# pandashield12-lga.net
KiCad netlist of a schematic drawn in EAGLE
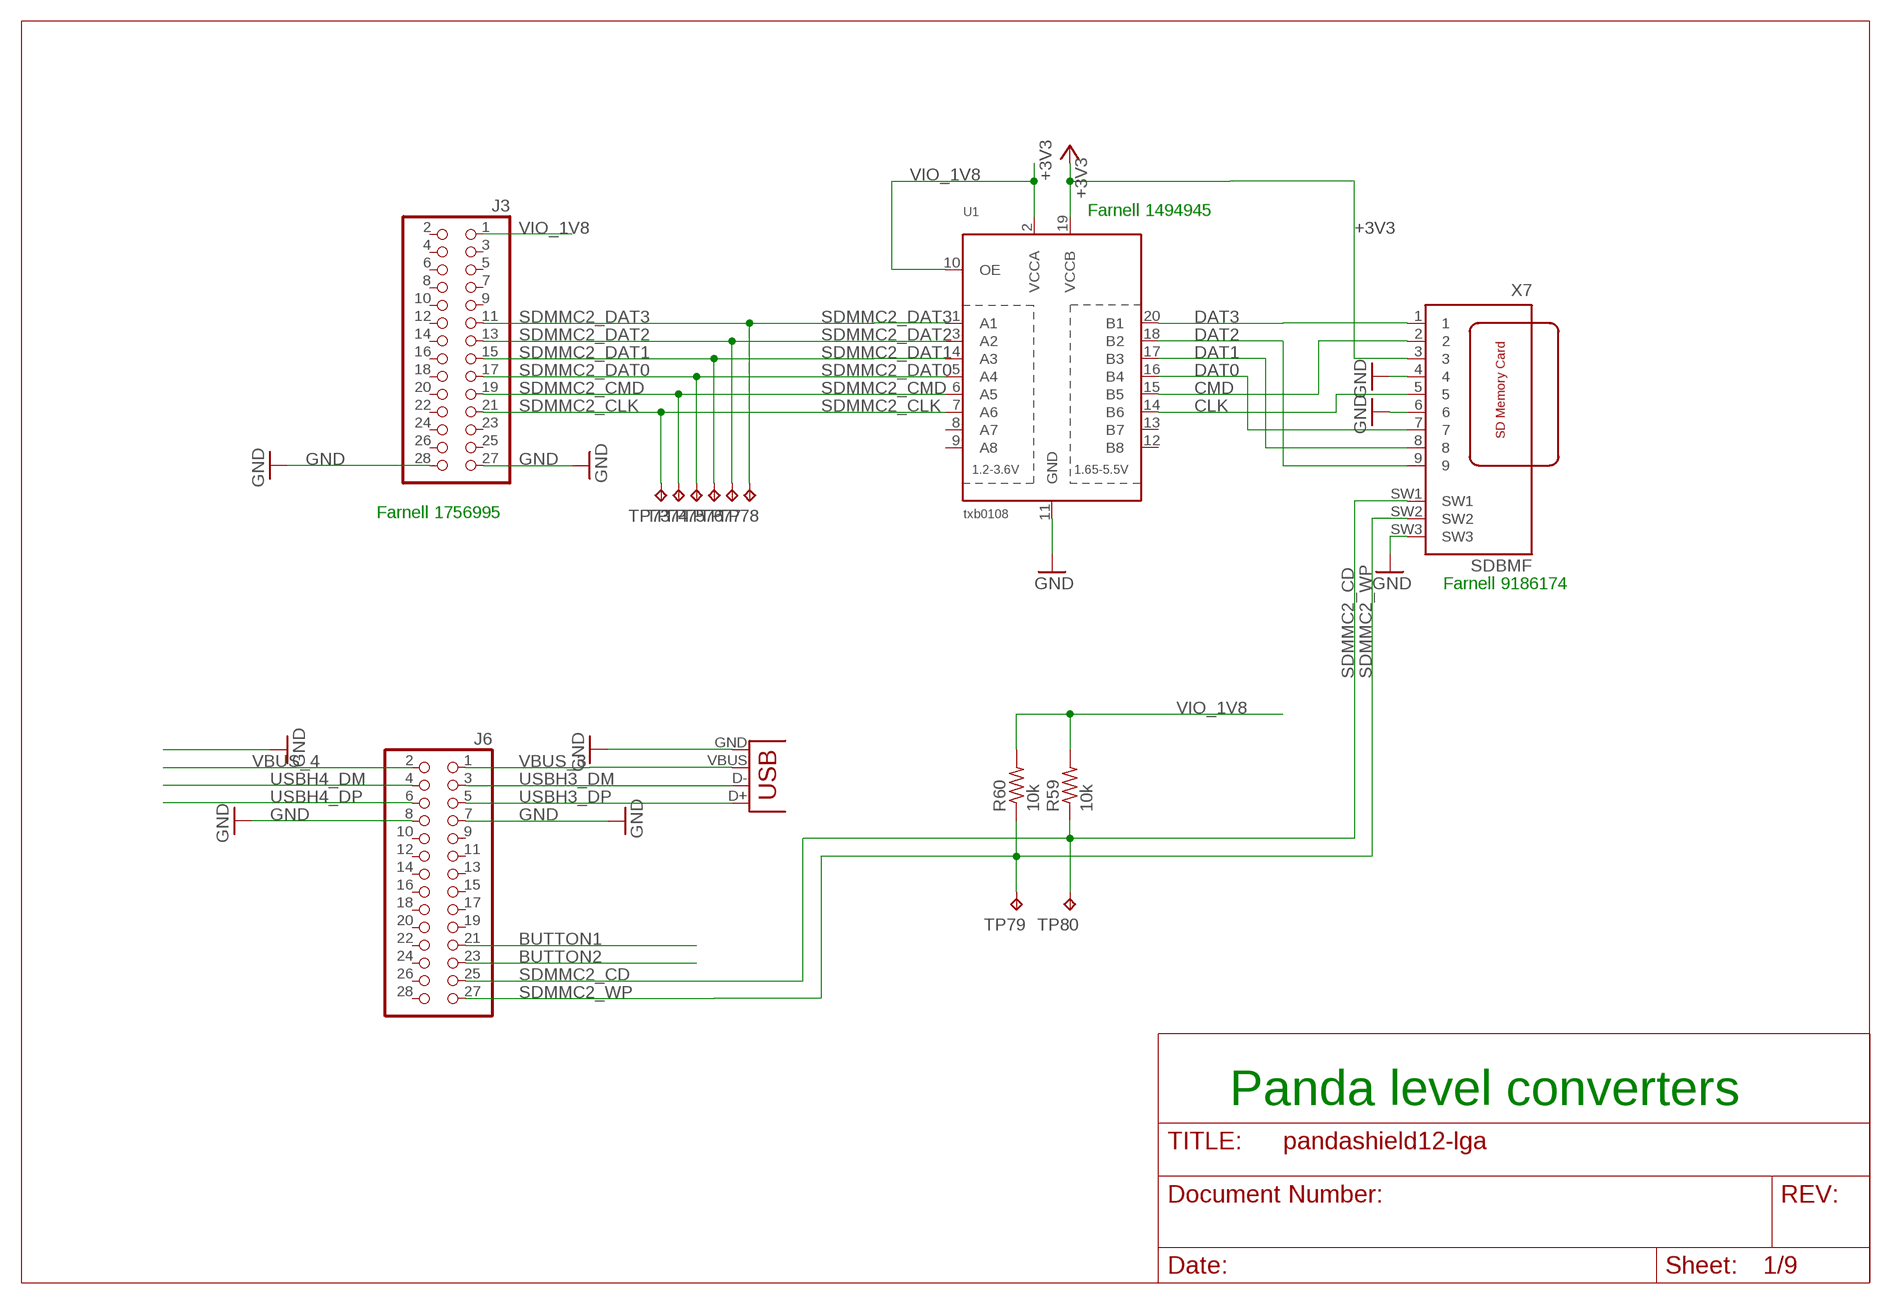
[diagram p0: schematic, sheet 1]
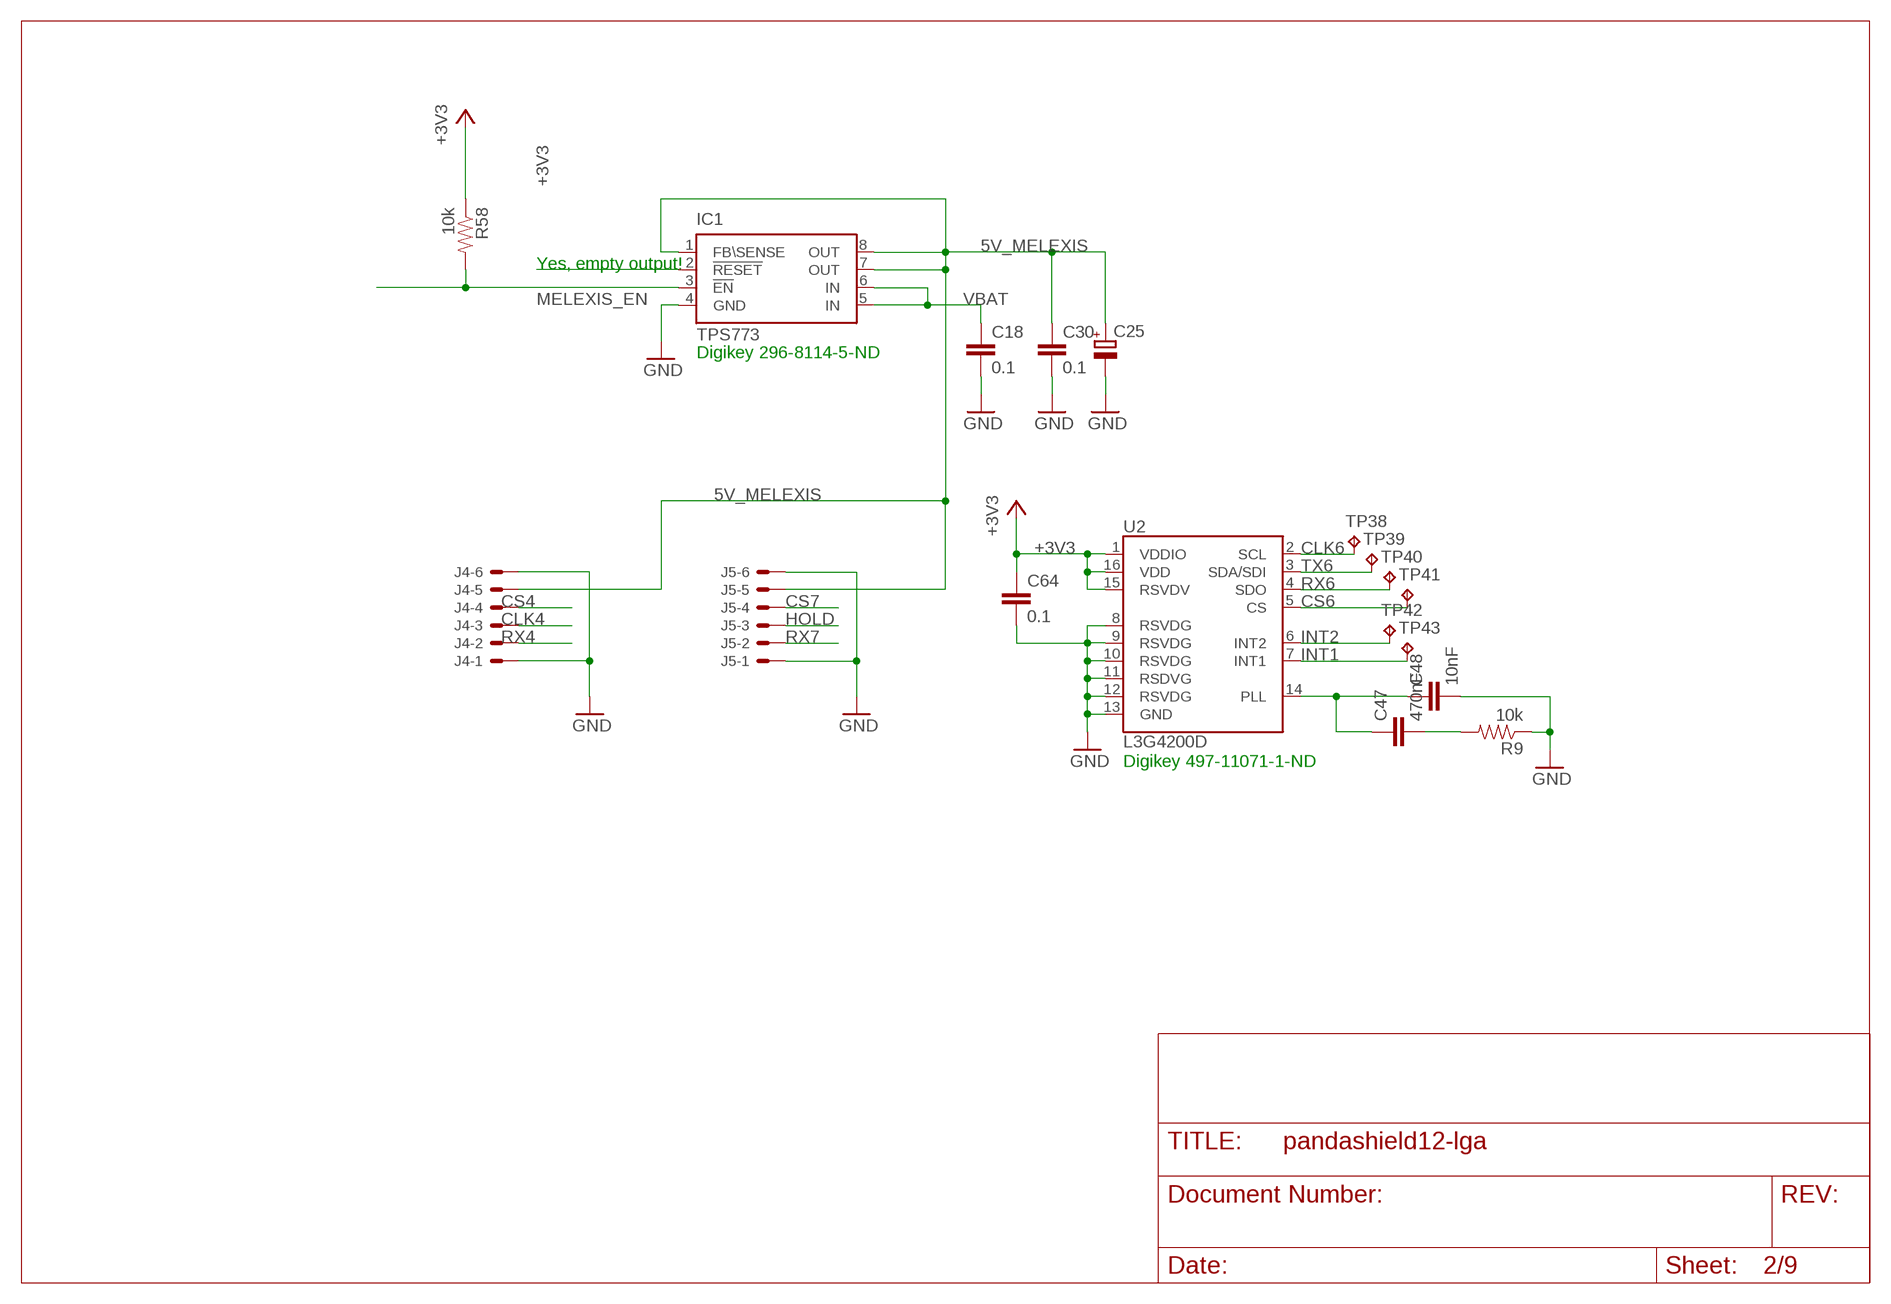
[diagram p1: schematic, sheet 2]
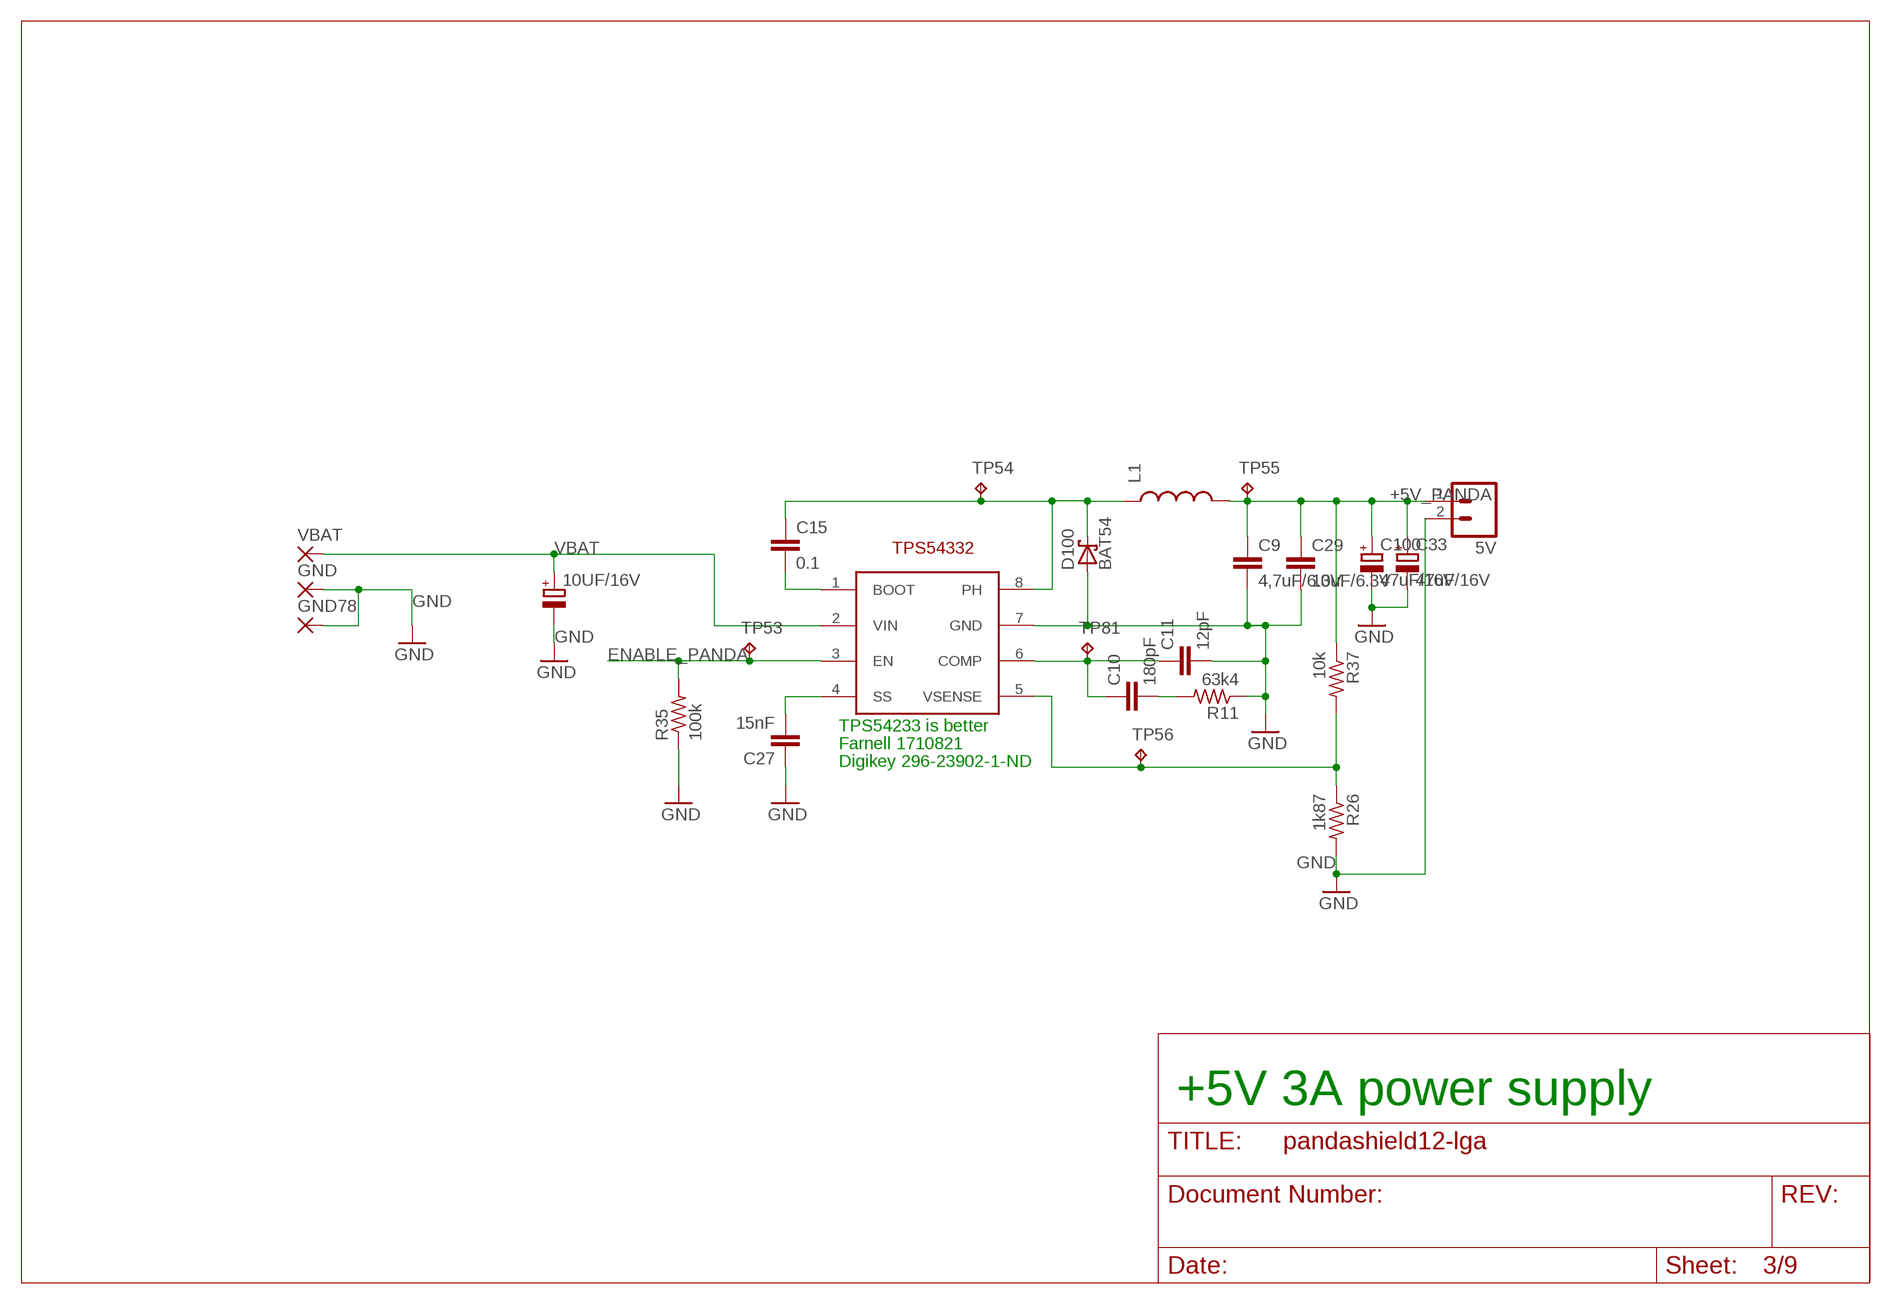
[diagram p2: schematic, sheet 3]
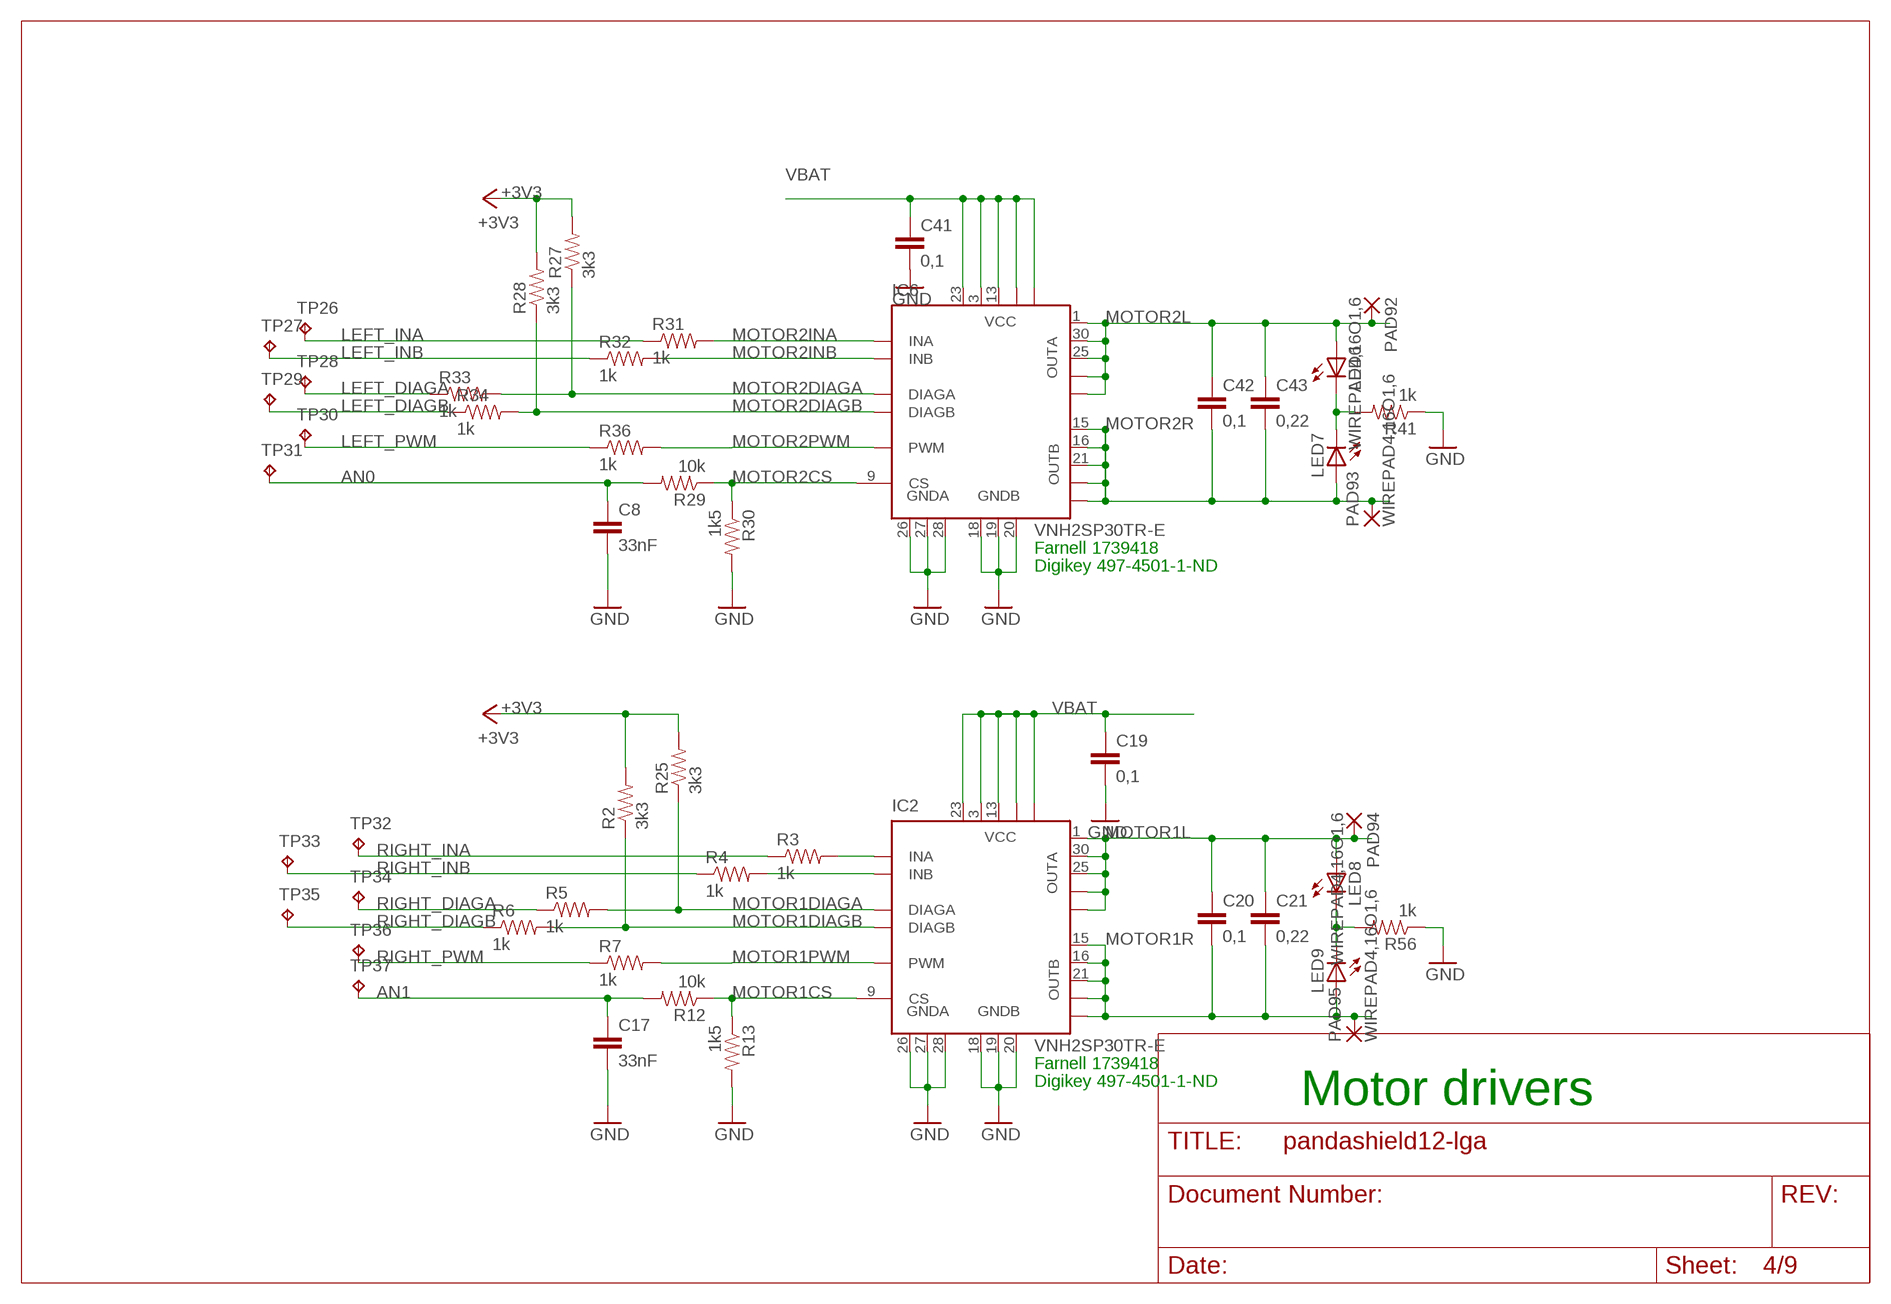
[diagram p3: schematic, sheet 4]
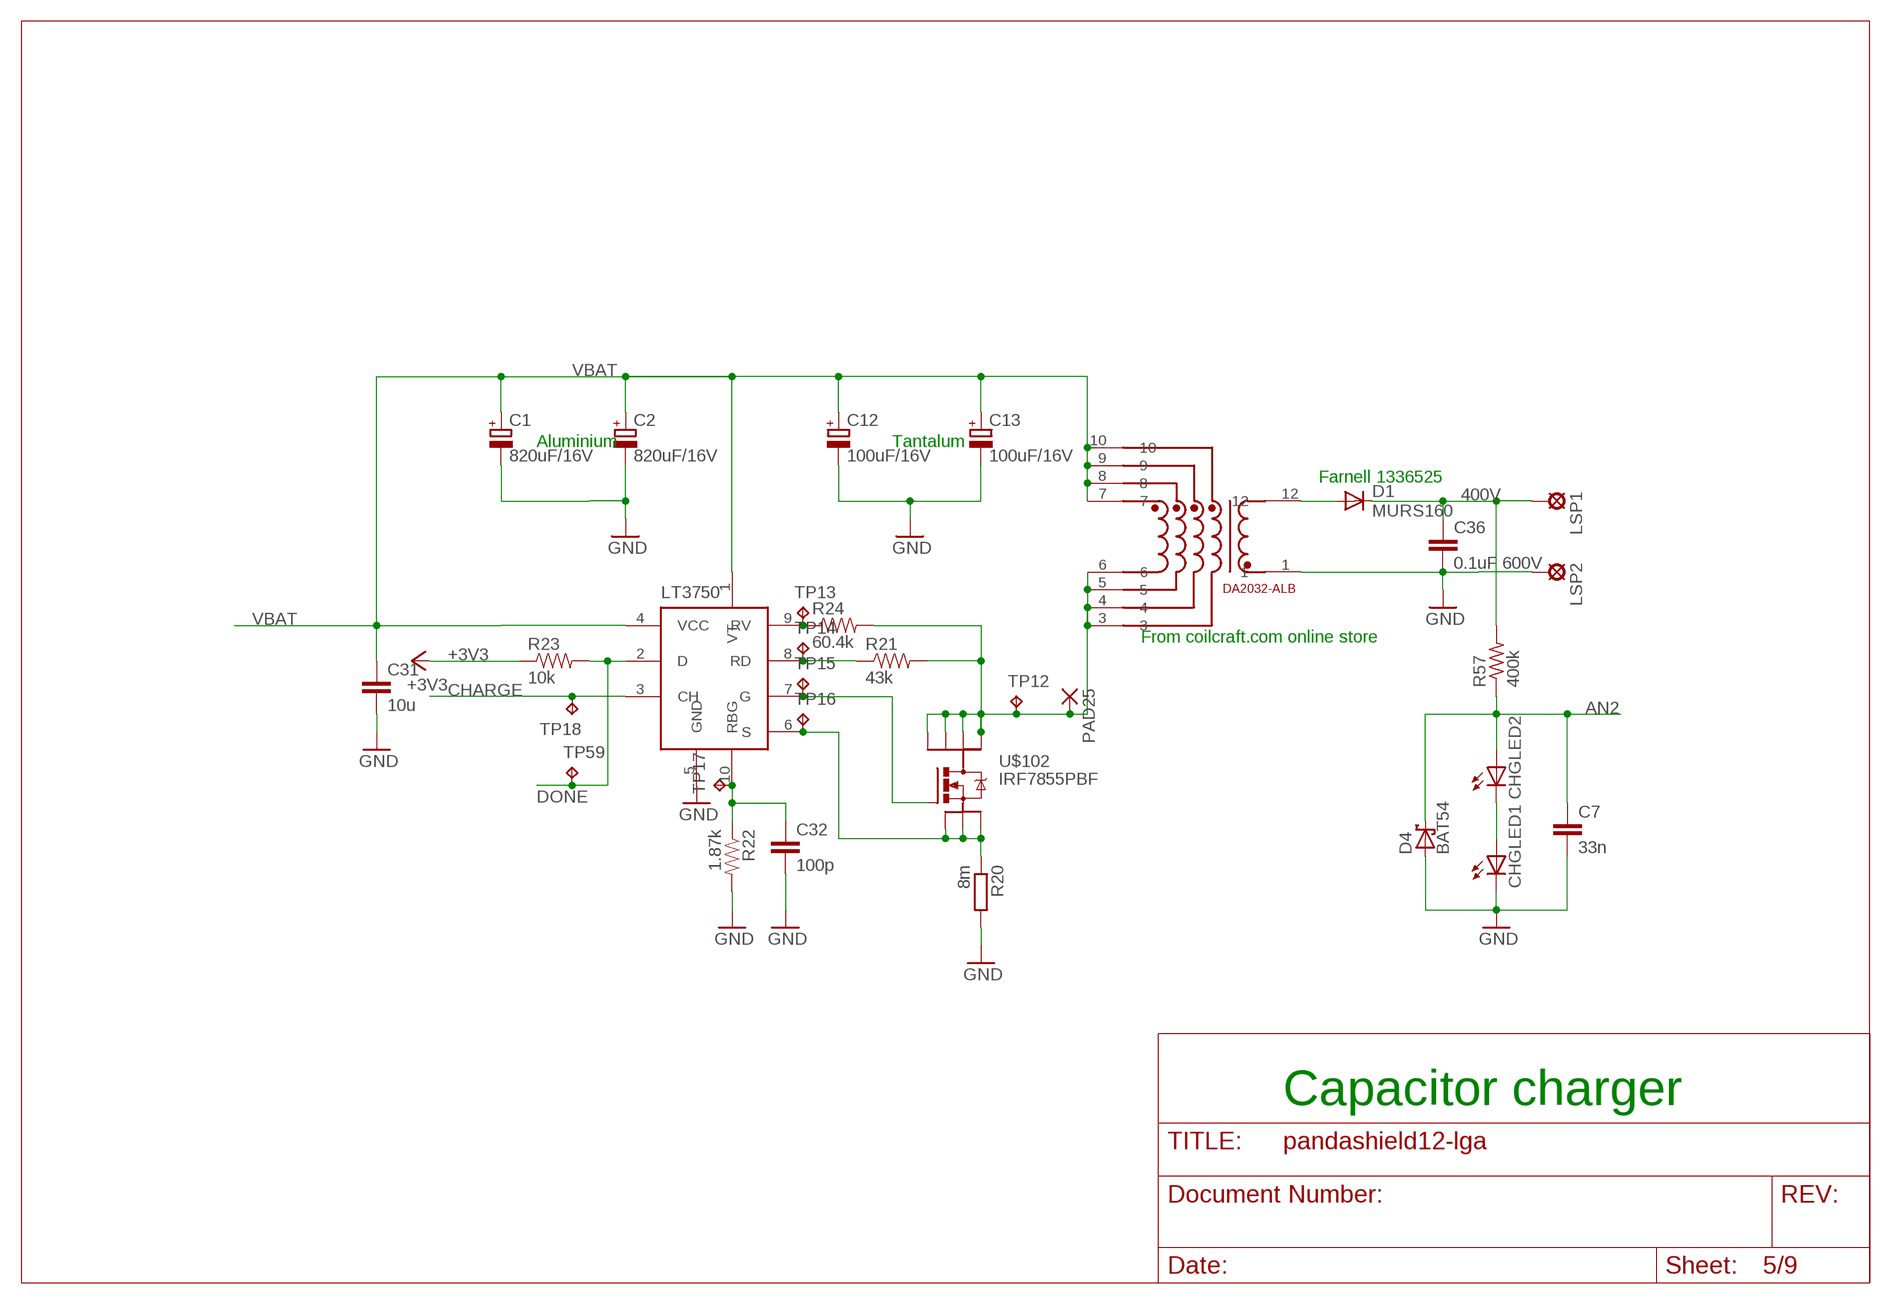
[diagram p4: schematic, sheet 5]
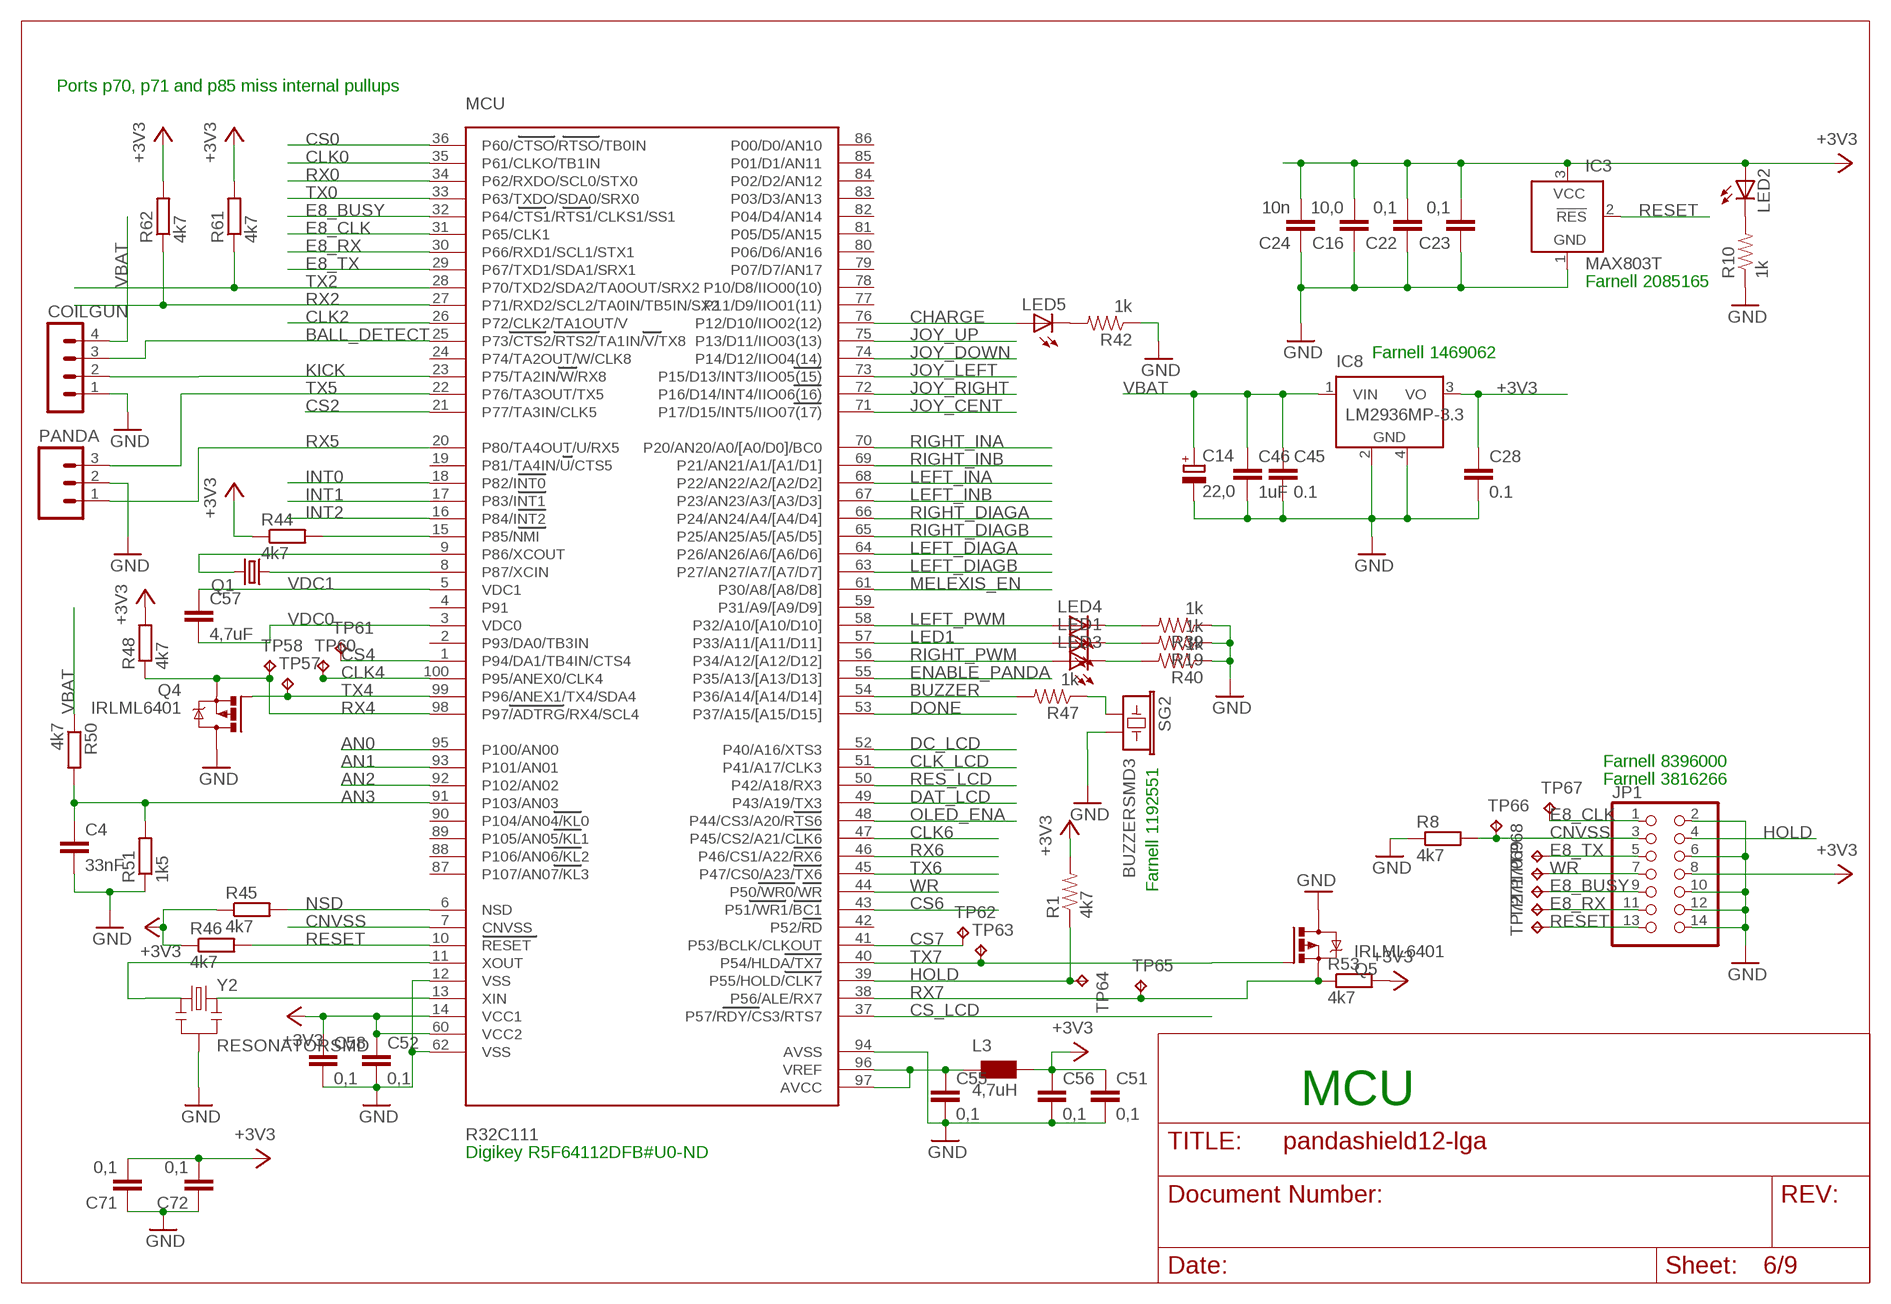
[diagram p5: schematic, sheet 6]
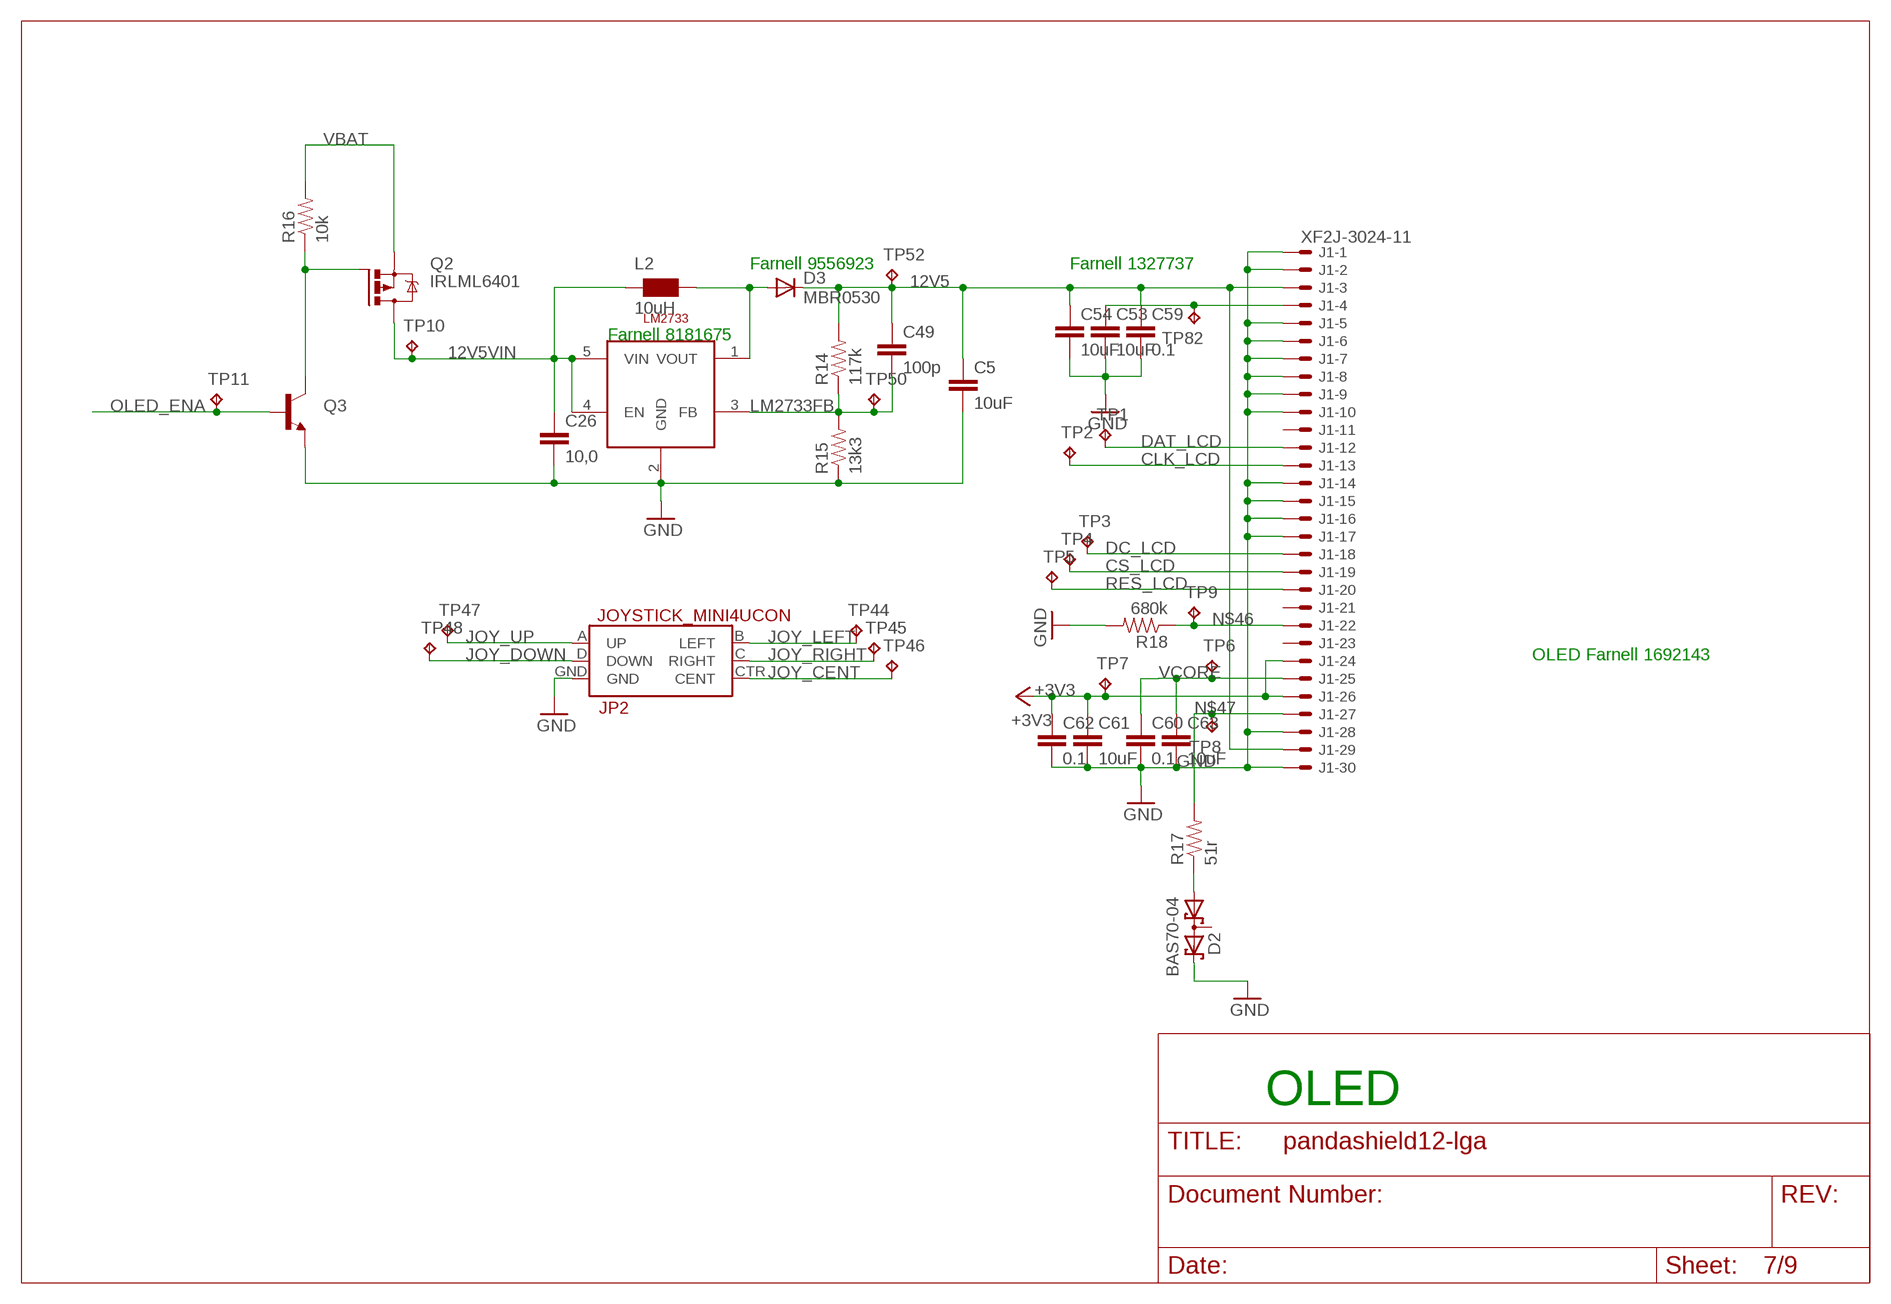
[diagram p6: schematic, sheet 7]
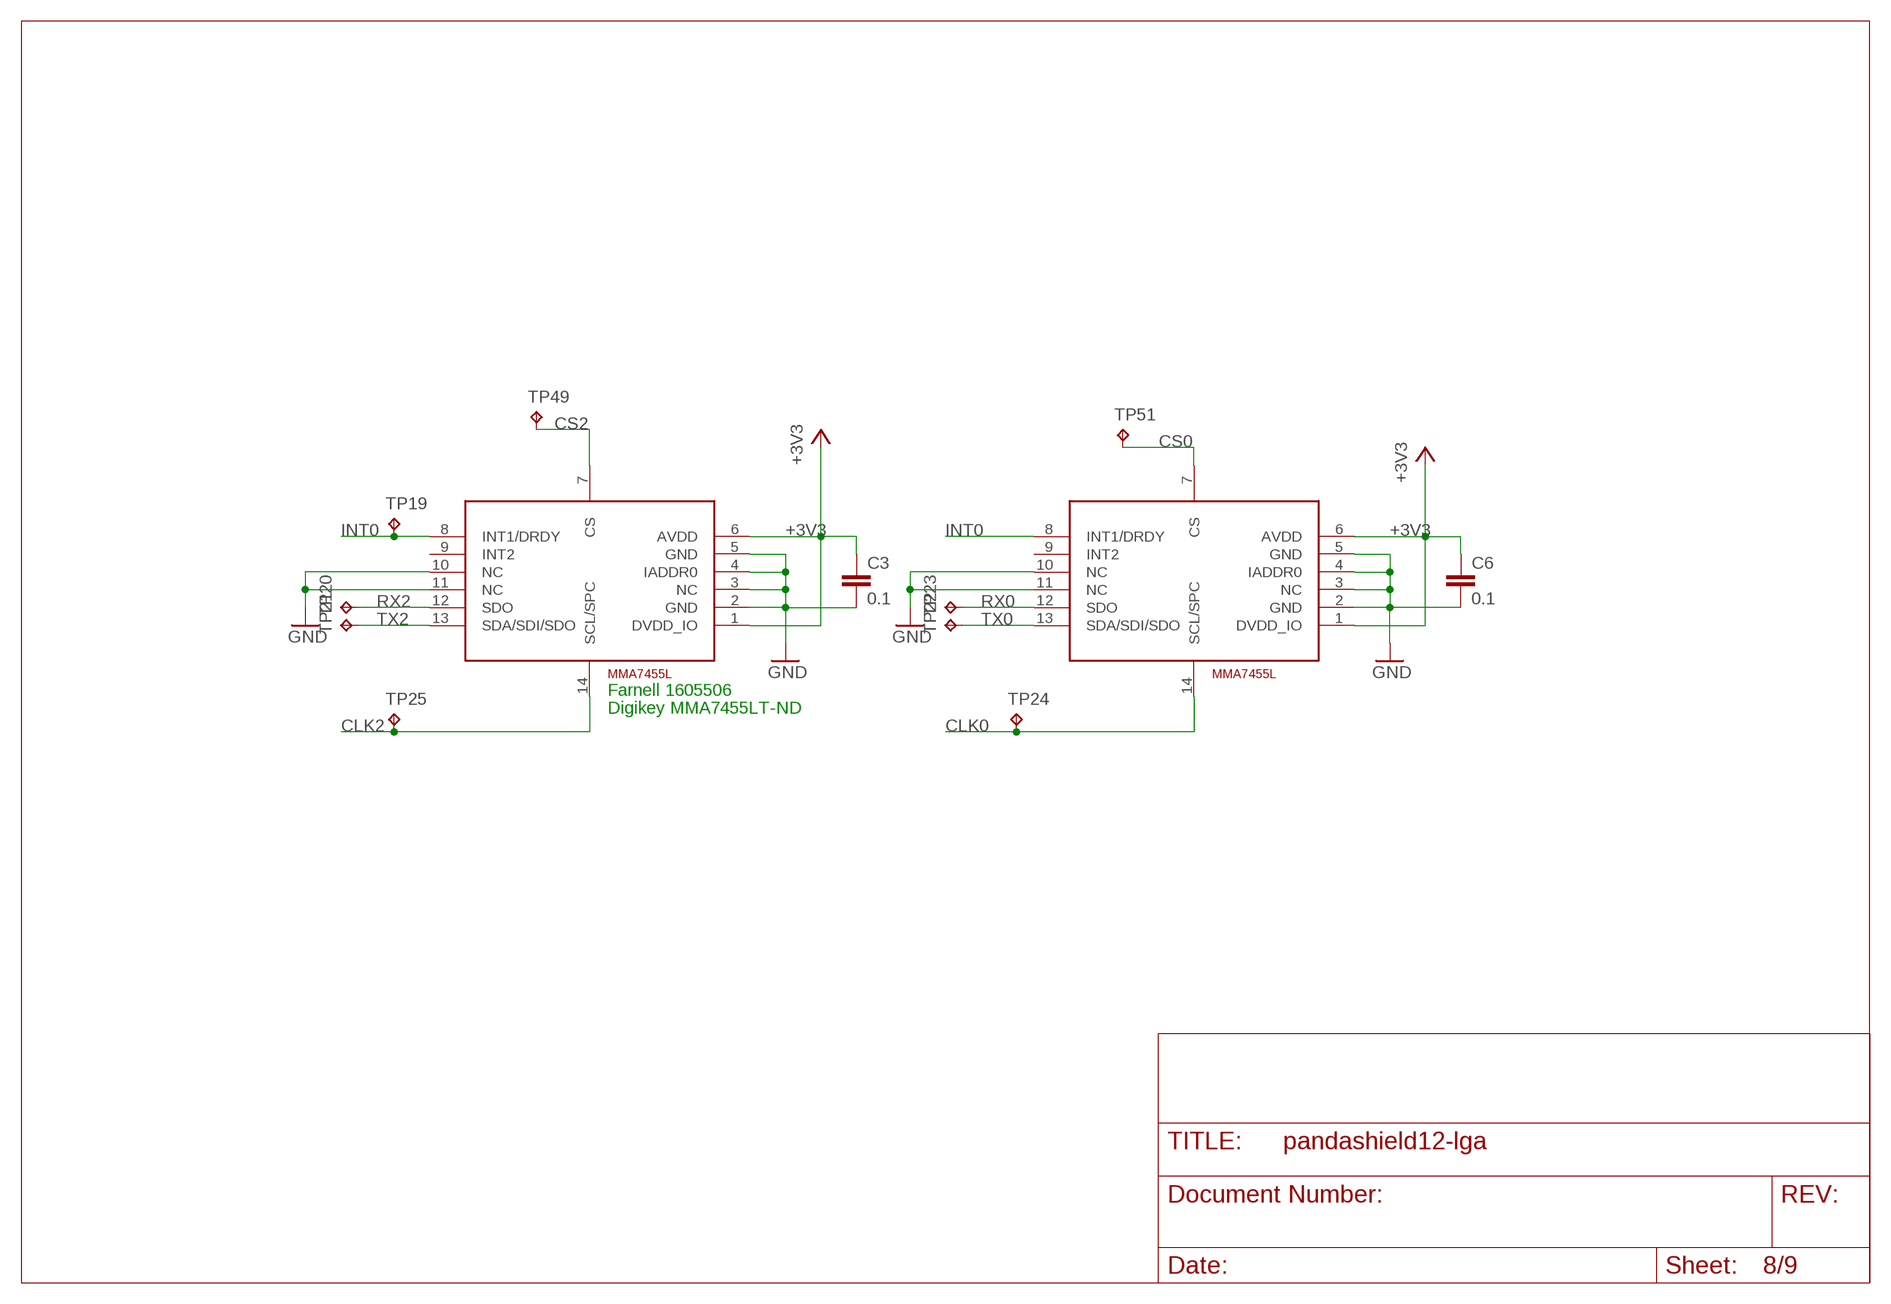
[diagram p7: schematic, sheet 8]
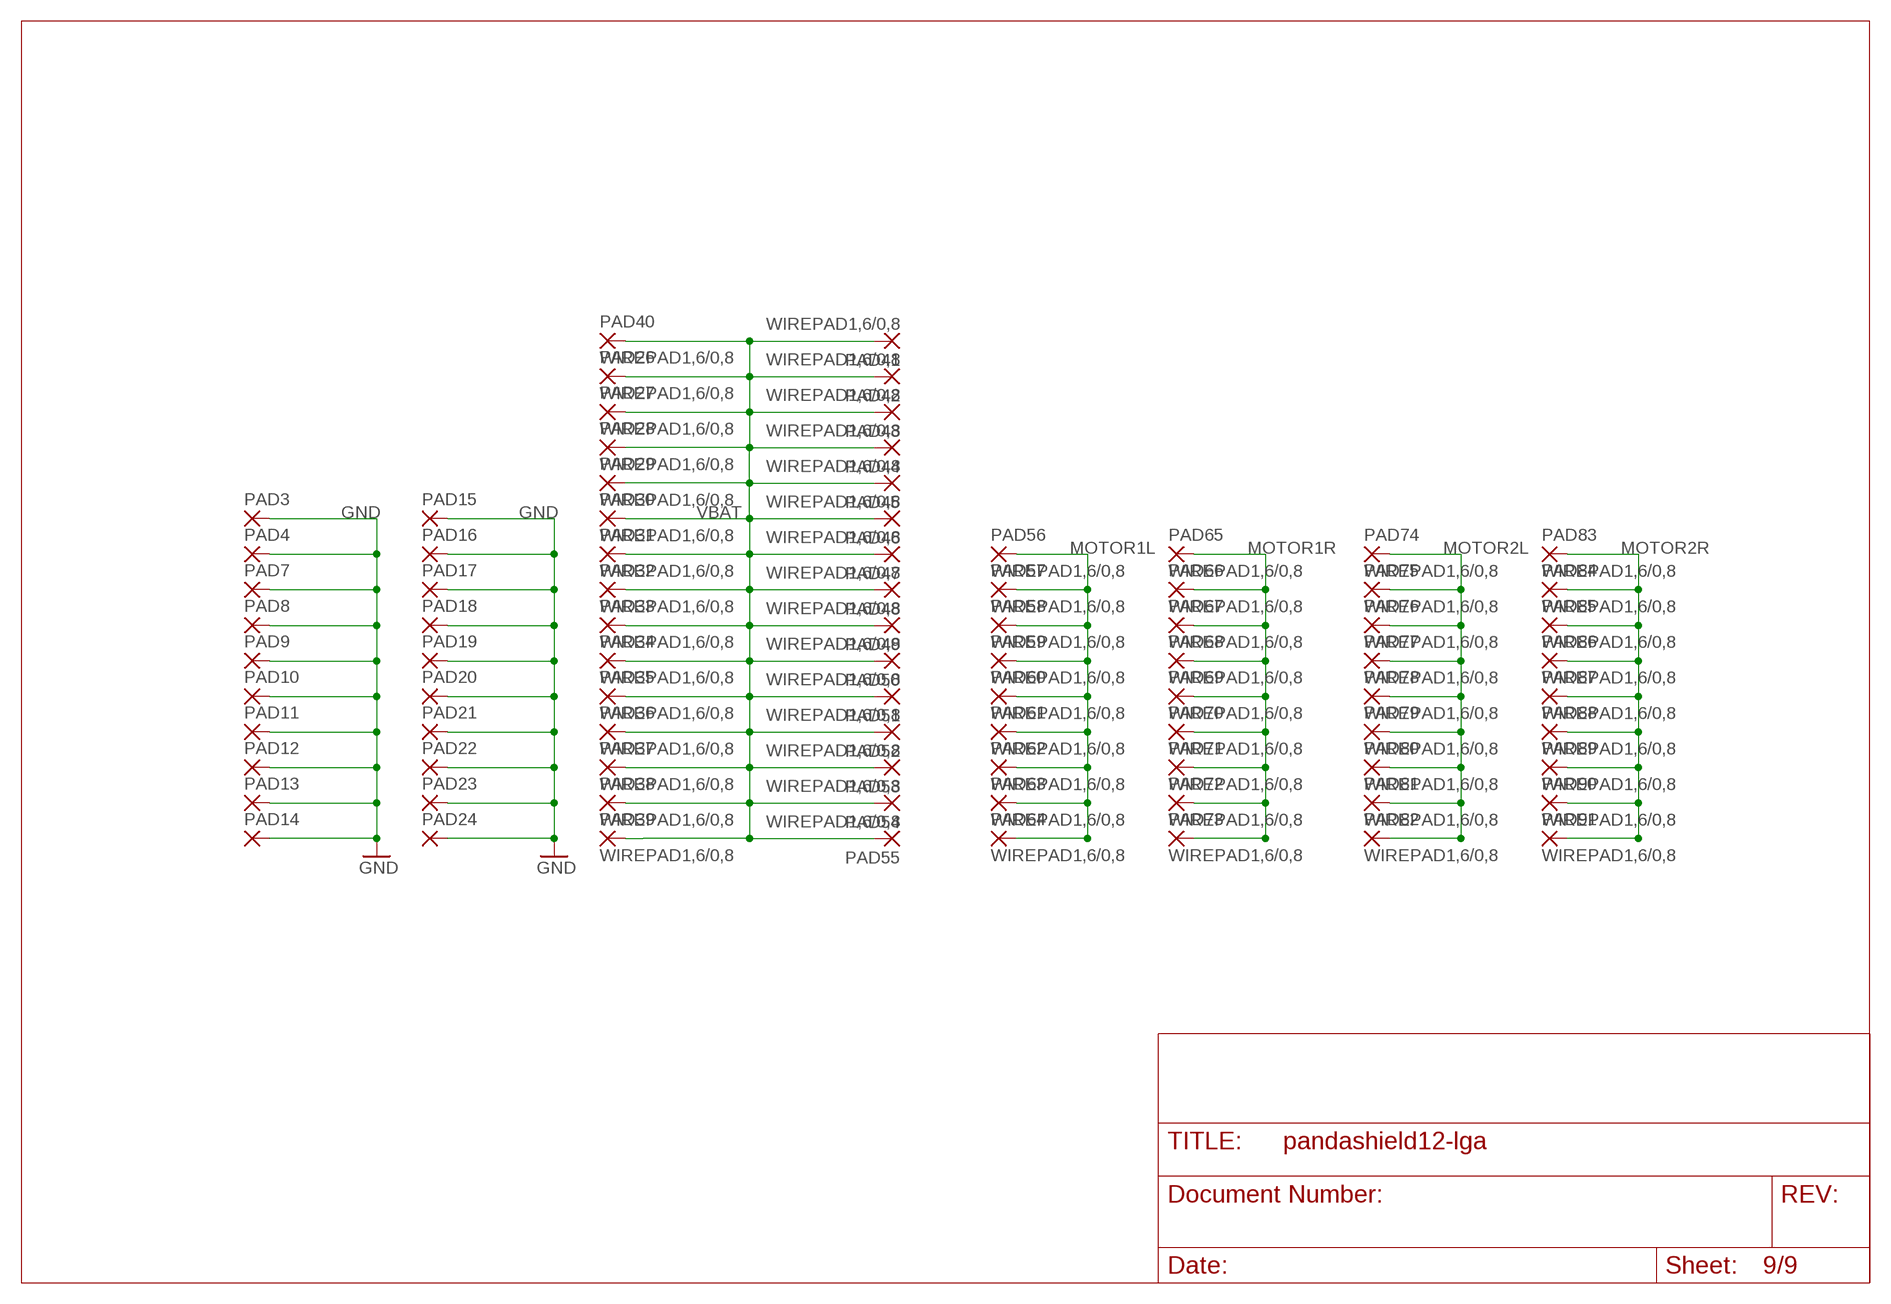
[diagram p8: schematic, sheet 9]

(export (version "E")
  (design (tool "Eeschema 10.0.6"))
  (components
    (comp (ref "C4")
      (value "33nF")
      (footprint "eagle-import:C0603")
      (libsource (lib "eagle-import") (part "C-EUC0603"))
    )
    (comp (ref "C14")
      (value "22,0")
      (footprint "eagle-import:CT3528")
      (libsource (lib "eagle-import") (part "CPOL-EUCT3528"))
    )
    (comp (ref "C16")
      (value "10,0")
      (footprint "eagle-import:C1210")
      (libsource (lib "eagle-import") (part "C-EUC1210"))
    )
    (comp (ref "C22")
      (value "0,1")
      (footprint "eagle-import:C0603")
      (libsource (lib "eagle-import") (part "C-EUC0603"))
    )
    (comp (ref "C23")
      (value "0,1")
      (footprint "eagle-import:C0603")
      (libsource (lib "eagle-import") (part "C-EUC0603"))
    )
    (comp (ref "C24")
      (value "10n")
      (footprint "eagle-import:C0603")
      (libsource (lib "eagle-import") (part "C-EUC0603"))
    )
    (comp (ref "C28")
      (value "0.1")
      (footprint "eagle-import:0603-CAP")
      (libsource (lib "eagle-import") (part "CAP0603-CAP"))
    )
    (comp (ref "C45")
      (value "0.1")
      (footprint "eagle-import:0603-CAP")
      (libsource (lib "eagle-import") (part "CAP0603-CAP"))
    )
    (comp (ref "C46")
      (value "1uF")
      (footprint "eagle-import:0603-CAP")
      (libsource (lib "eagle-import") (part "CAP0603-CAP"))
    )
    (comp (ref "C51")
      (value "0,1")
      (footprint "eagle-import:C0603")
      (libsource (lib "eagle-import") (part "C-EUC0603"))
    )
    (comp (ref "C52")
      (value "0,1")
      (footprint "eagle-import:C0603")
      (libsource (lib "eagle-import") (part "C-EUC0603"))
    )
    (comp (ref "C55")
      (value "0,1")
      (footprint "eagle-import:C0603")
      (libsource (lib "eagle-import") (part "C-EUC0603"))
    )
    (comp (ref "C56")
      (value "0,1")
      (footprint "eagle-import:C0603")
      (libsource (lib "eagle-import") (part "C-EUC0603"))
    )
    (comp (ref "C57")
      (value "4,7uF")
      (footprint "eagle-import:C0805K")
      (libsource (lib "eagle-import") (part "C-EUC0805K"))
    )
    (comp (ref "C58")
      (value "0,1")
      (footprint "eagle-import:C0603")
      (libsource (lib "eagle-import") (part "C-EUC0603"))
    )
    (comp (ref "C71")
      (value "0,1")
      (footprint "eagle-import:C0603")
      (libsource (lib "eagle-import") (part "C-EUC0603"))
    )
    (comp (ref "C72")
      (value "0,1")
      (footprint "eagle-import:C0603")
      (libsource (lib "eagle-import") (part "C-EUC0603"))
    )
    (comp (ref "COILGUN")
      (value "MA04-1")
      (footprint "eagle-import:MA04-1")
      (libsource (lib "eagle-import") (part "MA04-1"))
    )
    (comp (ref "IC3")
      (value "MAX803T")
      (footprint "eagle-import:SOT23B-3")
      (fields (field (name "MF") "MICROCHIP") (field (name "MPN") "TCM809MENB713"))
      (libsource (lib "eagle-import") (part "TCM809"))
    )
    (comp (ref "IC8")
      (value "LM2936MP-3.3")
      (footprint "eagle-import:SOT223")
      (fields (field (name "MF") "NATIONAL SEMICONDUCTOR") (field (name "MPN") "LM2936MP-3.0/NOPB"))
      (libsource (lib "eagle-import") (part "LM2936MP?-3.0"))
    )
    (comp (ref "JP1")
      (value "PINHD-2X7")
      (footprint "eagle-import:2X07")
      (libsource (lib "eagle-import") (part "PINHD-2X7"))
    )
    (comp (ref "L3")
      (value "4,7uH")
      (footprint "eagle-import:WE-KI_0805_B")
      (libsource (lib "eagle-import") (part "WE-KIHQ_0805"))
    )
    (comp (ref "LED1")
      (value "LEDCHIP-LED0603")
      (footprint "eagle-import:CHIP-LED0603")
      (libsource (lib "eagle-import") (part "LEDCHIP-LED0603"))
    )
    (comp (ref "LED2")
      (value "LEDCHIP-LED0603")
      (footprint "eagle-import:CHIP-LED0603")
      (libsource (lib "eagle-import") (part "LEDCHIP-LED0603"))
    )
    (comp (ref "LED3")
      (value "LEDCHIP-LED0603")
      (footprint "eagle-import:CHIP-LED0603")
      (libsource (lib "eagle-import") (part "LEDCHIP-LED0603"))
    )
    (comp (ref "LED4")
      (value "LEDCHIP-LED0603")
      (footprint "eagle-import:CHIP-LED0603")
      (libsource (lib "eagle-import") (part "LEDCHIP-LED0603"))
    )
    (comp (ref "LED5")
      (value "LEDCHIP-LED0603")
      (footprint "eagle-import:CHIP-LED0603")
      (libsource (lib "eagle-import") (part "LEDCHIP-LED0603"))
    )
    (comp (ref "MCU")
      (value "R32C111")
      (footprint "eagle-import:100P6Q-A")
      (libsource (lib "eagle-import") (part "R32C111"))
    )
    (comp (ref "PANDA")
      (value "MA03")
      (footprint "eagle-import:03P")
      (libsource (lib "eagle-import") (part "MA03"))
    )
    (comp (ref "Q1")
      (value "CRYSTALMM20SS")
      (footprint "eagle-import:MM20SS")
      (libsource (lib "eagle-import") (part "CRYSTALMM20SS"))
    )
    (comp (ref "Q4")
      (value "IRLML6401")
      (footprint "eagle-import:MICRO3")
      (libsource (lib "eagle-import") (part "IRLML5203"))
    )
    (comp (ref "Q5")
      (value "IRLML6401")
      (footprint "eagle-import:MICRO3")
      (libsource (lib "eagle-import") (part "IRLML5203"))
    )
    (comp (ref "R1")
      (value "4k7")
      (footprint "eagle-import:0603-RES")
      (libsource (lib "eagle-import") (part "RESISTOR0603-RES"))
    )
    (comp (ref "R8")
      (value "4k7")
      (footprint "eagle-import:R0603")
      (libsource (lib "eagle-import") (part "R-EU_R0603"))
    )
    (comp (ref "R10")
      (value "1k")
      (footprint "eagle-import:0603-RES")
      (libsource (lib "eagle-import") (part "RESISTOR0603-RES"))
    )
    (comp (ref "R19")
      (value "1k")
      (footprint "eagle-import:0603-RES")
      (libsource (lib "eagle-import") (part "RESISTOR0603-RES"))
    )
    (comp (ref "R39")
      (value "1k")
      (footprint "eagle-import:0603-RES")
      (libsource (lib "eagle-import") (part "RESISTOR0603-RES"))
    )
    (comp (ref "R40")
      (value "1k")
      (footprint "eagle-import:0603-RES")
      (libsource (lib "eagle-import") (part "RESISTOR0603-RES"))
    )
    (comp (ref "R42")
      (value "1k")
      (footprint "eagle-import:0603-RES")
      (libsource (lib "eagle-import") (part "RESISTOR0603-RES"))
    )
    (comp (ref "R44")
      (value "4k7")
      (footprint "eagle-import:R0603")
      (libsource (lib "eagle-import") (part "R-EU_R0603"))
    )
    (comp (ref "R45")
      (value "4k7")
      (footprint "eagle-import:R0603")
      (libsource (lib "eagle-import") (part "R-EU_R0603"))
    )
    (comp (ref "R46")
      (value "4k7")
      (footprint "eagle-import:R0603")
      (libsource (lib "eagle-import") (part "R-EU_R0603"))
    )
    (comp (ref "R47")
      (value "1k")
      (footprint "eagle-import:0603-RES")
      (libsource (lib "eagle-import") (part "RESISTOR0603-RES"))
    )
    (comp (ref "R48")
      (value "4k7")
      (footprint "eagle-import:R0603")
      (libsource (lib "eagle-import") (part "R-EU_R0603"))
    )
    (comp (ref "R50")
      (value "4k7")
      (footprint "eagle-import:R0603")
      (libsource (lib "eagle-import") (part "R-EU_R0603"))
    )
    (comp (ref "R51")
      (value "1k5")
      (footprint "eagle-import:R0603")
      (libsource (lib "eagle-import") (part "R-EU_R0603"))
    )
    (comp (ref "R53")
      (value "4k7")
      (footprint "eagle-import:R0603")
      (libsource (lib "eagle-import") (part "R-EU_R0603"))
    )
    (comp (ref "R61")
      (value "4k7")
      (footprint "eagle-import:R0603")
      (libsource (lib "eagle-import") (part "R-EU_R0603"))
    )
    (comp (ref "R62")
      (value "4k7")
      (footprint "eagle-import:R0603")
      (libsource (lib "eagle-import") (part "R-EU_R0603"))
    )
    (comp (ref "SG2")
      (value "BUZZERSMD3")
      (footprint "eagle-import:BUZZER-CMT1102")
      (libsource (lib "eagle-import") (part "BUZZERSMD3"))
    )
    (comp (ref "TP57")
      (value "TPB1,27")
      (footprint "eagle-import:B1,27")
      (libsource (lib "eagle-import") (part "TPB1,27"))
    )
    (comp (ref "TP58")
      (value "TPB1,27")
      (footprint "eagle-import:B1,27")
      (libsource (lib "eagle-import") (part "TPB1,27"))
    )
    (comp (ref "TP60")
      (value "TPB1,27")
      (footprint "eagle-import:B1,27")
      (libsource (lib "eagle-import") (part "TPB1,27"))
    )
    (comp (ref "TP61")
      (value "TPB1,27")
      (footprint "eagle-import:B1,27")
      (libsource (lib "eagle-import") (part "TPB1,27"))
    )
    (comp (ref "TP62")
      (value "TPB1,27")
      (footprint "eagle-import:B1,27")
      (libsource (lib "eagle-import") (part "TPB1,27"))
    )
    (comp (ref "TP63")
      (value "TPB1,27")
      (footprint "eagle-import:B1,27")
      (libsource (lib "eagle-import") (part "TPB1,27"))
    )
    (comp (ref "TP64")
      (value "TPB1,27")
      (footprint "eagle-import:B1,27")
      (libsource (lib "eagle-import") (part "TPB1,27"))
    )
    (comp (ref "TP65")
      (value "TPB1,27")
      (footprint "eagle-import:B1,27")
      (libsource (lib "eagle-import") (part "TPB1,27"))
    )
    (comp (ref "TP66")
      (value "TPB1,27")
      (footprint "eagle-import:B1,27")
      (libsource (lib "eagle-import") (part "TPB1,27"))
    )
    (comp (ref "TP67")
      (value "TPB1,27")
      (footprint "eagle-import:B1,27")
      (libsource (lib "eagle-import") (part "TPB1,27"))
    )
    (comp (ref "TP68")
      (value "TPB1,27")
      (footprint "eagle-import:B1,27")
      (libsource (lib "eagle-import") (part "TPB1,27"))
    )
    (comp (ref "TP69")
      (value "TPB1,27")
      (footprint "eagle-import:B1,27")
      (libsource (lib "eagle-import") (part "TPB1,27"))
    )
    (comp (ref "TP70")
      (value "TPB1,27")
      (footprint "eagle-import:B1,27")
      (libsource (lib "eagle-import") (part "TPB1,27"))
    )
    (comp (ref "TP71")
      (value "TPB1,27")
      (footprint "eagle-import:B1,27")
      (libsource (lib "eagle-import") (part "TPB1,27"))
    )
    (comp (ref "TP72")
      (value "TPB1,27")
      (footprint "eagle-import:B1,27")
      (libsource (lib "eagle-import") (part "TPB1,27"))
    )
    (comp (ref "Y2")
      (value "RESONATORSMD")
      (footprint "eagle-import:RESONATOR-SMD")
      (libsource (lib "eagle-import") (part "RESONATORSMD"))
    )
    (comp (ref "C5")
      (value "10uF")
      (footprint "eagle-import:1210")
      (libsource (lib "eagle-import") (part "CAP1210"))
    )
    (comp (ref "C26")
      (value "10,0")
      (footprint "eagle-import:1210")
      (libsource (lib "eagle-import") (part "CAP1210"))
    )
    (comp (ref "C49")
      (value "100p")
      (footprint "eagle-import:0603-CAP")
      (libsource (lib "eagle-import") (part "CAP0603-CAP"))
    )
    (comp (ref "C53")
      (value "10uF")
      (footprint "eagle-import:1210")
      (libsource (lib "eagle-import") (part "CAP1210"))
    )
    (comp (ref "C54")
      (value "10uF")
      (footprint "eagle-import:1210")
      (libsource (lib "eagle-import") (part "CAP1210"))
    )
    (comp (ref "C59")
      (value "0.1")
      (footprint "eagle-import:0603-CAP")
      (libsource (lib "eagle-import") (part "CAP0603-CAP"))
    )
    (comp (ref "C60")
      (value "0.1")
      (footprint "eagle-import:0603-CAP")
      (libsource (lib "eagle-import") (part "CAP0603-CAP"))
    )
    (comp (ref "C61")
      (value "10uF")
      (footprint "eagle-import:1210")
      (libsource (lib "eagle-import") (part "CAP1210"))
    )
    (comp (ref "C62")
      (value "0.1")
      (footprint "eagle-import:0603-CAP")
      (libsource (lib "eagle-import") (part "CAP0603-CAP"))
    )
    (comp (ref "C63")
      (value "10uF")
      (footprint "eagle-import:1210")
      (libsource (lib "eagle-import") (part "CAP1210"))
    )
    (comp (ref "D2")
      (value "BAS70-04")
      (footprint "eagle-import:SOT23")
      (libsource (lib "eagle-import") (part "BAS70-04"))
    )
    (comp (ref "D3")
      (value "MBR0530")
      (footprint "eagle-import:SOD123")
      (libsource (lib "eagle-import") (part "MBR0520LT"))
    )
    (comp (ref "J1")
      (value "XF2J-3024-11")
      (footprint "eagle-import:XF2J-3024-11")
      (libsource (lib "eagle-import") (part "XF2-30?24-11J"))
    )
    (comp (ref "JP2")
      (value "JOYSTICK_MINI4UCON")
      (footprint "eagle-import:JOYSTICK_MINI")
      (libsource (lib "eagle-import") (part "JOYSTICK_MINI4UCON"))
    )
    (comp (ref "L2")
      (value "10uH")
      (footprint "eagle-import:WE-KI_0805_B")
      (libsource (lib "eagle-import") (part "WE-KIHQ_0805"))
    )
    (comp (ref "Q2")
      (value "IRLML6401")
      (footprint "eagle-import:MICRO3")
      (libsource (lib "eagle-import") (part "IRLML5203"))
    )
    (comp (ref "Q3")
      (value "TRANSISTOR_NPNSOT23-3")
      (footprint "eagle-import:SOT23-3")
      (libsource (lib "eagle-import") (part "TRANSISTOR_NPNSOT23-3"))
    )
    (comp (ref "R14")
      (value "117k")
      (footprint "eagle-import:0603-RES")
      (libsource (lib "eagle-import") (part "RESISTOR0603-RES"))
    )
    (comp (ref "R15")
      (value "13k3")
      (footprint "eagle-import:0603-RES")
      (libsource (lib "eagle-import") (part "RESISTOR0603-RES"))
    )
    (comp (ref "R16")
      (value "10k")
      (footprint "eagle-import:0603-RES")
      (libsource (lib "eagle-import") (part "RESISTOR0603-RES"))
    )
    (comp (ref "R17")
      (value "51r")
      (footprint "eagle-import:0603-RES")
      (libsource (lib "eagle-import") (part "RESISTOR0603-RES"))
    )
    (comp (ref "R18")
      (value "680k")
      (footprint "eagle-import:0603-RES")
      (libsource (lib "eagle-import") (part "RESISTOR0603-RES"))
    )
    (comp (ref "TP1")
      (value "TPB1,27")
      (footprint "eagle-import:B1,27")
      (libsource (lib "eagle-import") (part "TPB1,27"))
    )
    (comp (ref "TP2")
      (value "TPB1,27")
      (footprint "eagle-import:B1,27")
      (libsource (lib "eagle-import") (part "TPB1,27"))
    )
    (comp (ref "TP3")
      (value "TPB1,27")
      (footprint "eagle-import:B1,27")
      (libsource (lib "eagle-import") (part "TPB1,27"))
    )
    (comp (ref "TP4")
      (value "TPB1,27")
      (footprint "eagle-import:B1,27")
      (libsource (lib "eagle-import") (part "TPB1,27"))
    )
    (comp (ref "TP5")
      (value "TPB1,27")
      (footprint "eagle-import:B1,27")
      (libsource (lib "eagle-import") (part "TPB1,27"))
    )
    (comp (ref "TP6")
      (value "TPB1,27")
      (footprint "eagle-import:B1,27")
      (libsource (lib "eagle-import") (part "TPB1,27"))
    )
    (comp (ref "TP7")
      (value "TPB1,27")
      (footprint "eagle-import:B1,27")
      (libsource (lib "eagle-import") (part "TPB1,27"))
    )
    (comp (ref "TP8")
      (value "TPB1,27")
      (footprint "eagle-import:B1,27")
      (libsource (lib "eagle-import") (part "TPB1,27"))
    )
    (comp (ref "TP9")
      (value "TPB1,27")
      (footprint "eagle-import:B1,27")
      (libsource (lib "eagle-import") (part "TPB1,27"))
    )
    (comp (ref "TP10")
      (value "TPB1,27")
      (footprint "eagle-import:B1,27")
      (libsource (lib "eagle-import") (part "TPB1,27"))
    )
    (comp (ref "TP11")
      (value "TPB1,27")
      (footprint "eagle-import:B1,27")
      (libsource (lib "eagle-import") (part "TPB1,27"))
    )
    (comp (ref "TP44")
      (value "TPB1,27")
      (footprint "eagle-import:B1,27")
      (libsource (lib "eagle-import") (part "TPB1,27"))
    )
    (comp (ref "TP45")
      (value "TPB1,27")
      (footprint "eagle-import:B1,27")
      (libsource (lib "eagle-import") (part "TPB1,27"))
    )
    (comp (ref "TP46")
      (value "TPB1,27")
      (footprint "eagle-import:B1,27")
      (libsource (lib "eagle-import") (part "TPB1,27"))
    )
    (comp (ref "TP47")
      (value "TPB1,27")
      (footprint "eagle-import:B1,27")
      (libsource (lib "eagle-import") (part "TPB1,27"))
    )
    (comp (ref "TP48")
      (value "TPB1,27")
      (footprint "eagle-import:B1,27")
      (libsource (lib "eagle-import") (part "TPB1,27"))
    )
    (comp (ref "TP50")
      (value "TPB1,27")
      (footprint "eagle-import:B1,27")
      (libsource (lib "eagle-import") (part "TPB1,27"))
    )
    (comp (ref "TP52")
      (value "TPB1,27")
      (footprint "eagle-import:B1,27")
      (libsource (lib "eagle-import") (part "TPB1,27"))
    )
    (comp (ref "TP82")
      (value "TPB1,27")
      (footprint "eagle-import:B1,27")
      (libsource (lib "eagle-import") (part "TPB1,27"))
    )
    (comp (ref "U$2")
      (value "LM2733")
      (footprint "eagle-import:SOT23-DBV")
      (libsource (lib "eagle-import") (part "LM2733"))
    )
    (comp (ref "5V")
      (value "M02")
      (footprint "eagle-import:02P")
      (libsource (lib "eagle-import") (part "M02"))
    )
    (comp (ref "10UF/16V")
      (value "CPOL-EUC/6032-28R")
      (footprint "eagle-import:C_6032-28R")
      (libsource (lib "eagle-import") (part "CPOL-EUC/6032-28R"))
    )
    (comp (ref "C9")
      (value "4,7uF/6.3V")
      (footprint "eagle-import:C0805")
      (libsource (lib "eagle-import") (part "C-EUC0805"))
    )
    (comp (ref "C10")
      (value "180pF")
      (footprint "eagle-import:C0603")
      (libsource (lib "eagle-import") (part "C-EUC0603"))
    )
    (comp (ref "C11")
      (value "12pF")
      (footprint "eagle-import:C0603")
      (libsource (lib "eagle-import") (part "C-EUC0603"))
    )
    (comp (ref "C15")
      (value "0.1")
      (footprint "eagle-import:C0603")
      (libsource (lib "eagle-import") (part "C-EUC0603"))
    )
    (comp (ref "C27")
      (value "15nF")
      (footprint "eagle-import:C0603")
      (libsource (lib "eagle-import") (part "C-EUC0603"))
    )
    (comp (ref "C29")
      (value "10uF/6.3V")
      (footprint "eagle-import:1210")
      (libsource (lib "eagle-import") (part "CAP1210"))
    )
    (comp (ref "C33")
      (value "47uF/16V")
      (footprint "eagle-import:C_6032-28R")
      (libsource (lib "eagle-import") (part "CPOL-EUC/6032-28R"))
    )
    (comp (ref "C100")
      (value "47uF/16V")
      (footprint "eagle-import:C_6032-28R")
      (libsource (lib "eagle-import") (part "CPOL-EUC/6032-28R"))
    )
    (comp (ref "D100")
      (value "BAT54")
      (footprint "eagle-import:SOT23")
      (libsource (lib "eagle-import") (part "BAT54"))
    )
    (comp (ref "GND")
      (value "3,81/1,4")
      (footprint "eagle-import:3,81_1,4")
      (libsource (lib "eagle-import") (part "3,81/1,4"))
    )
    (comp (ref "GND78")
      (value "3,81/1,4")
      (footprint "eagle-import:3,81_1,4")
      (libsource (lib "eagle-import") (part "3,81/1,4"))
    )
    (comp (ref "L1")
      (value "INDUCTORCR75")
      (footprint "eagle-import:CR75")
      (libsource (lib "eagle-import") (part "INDUCTORCR75"))
    )
    (comp (ref "R11")
      (value "63k4")
      (footprint "eagle-import:R0603")
      (libsource (lib "eagle-import") (part "R-US_R0603"))
    )
    (comp (ref "R26")
      (value "1k87")
      (footprint "eagle-import:R0603")
      (libsource (lib "eagle-import") (part "R-US_R0603"))
    )
    (comp (ref "R35")
      (value "100k")
      (footprint "eagle-import:R0603")
      (libsource (lib "eagle-import") (part "R-US_R0603"))
    )
    (comp (ref "R37")
      (value "10k")
      (footprint "eagle-import:R0603")
      (libsource (lib "eagle-import") (part "R-US_R0603"))
    )
    (comp (ref "TP53")
      (value "TPB1,27")
      (footprint "eagle-import:B1,27")
      (libsource (lib "eagle-import") (part "TPB1,27"))
    )
    (comp (ref "TP54")
      (value "TPB1,27")
      (footprint "eagle-import:B1,27")
      (libsource (lib "eagle-import") (part "TPB1,27"))
    )
    (comp (ref "TP55")
      (value "TPB1,27")
      (footprint "eagle-import:B1,27")
      (libsource (lib "eagle-import") (part "TPB1,27"))
    )
    (comp (ref "TP56")
      (value "TPB1,27")
      (footprint "eagle-import:B1,27")
      (libsource (lib "eagle-import") (part "TPB1,27"))
    )
    (comp (ref "TP81")
      (value "TPB1,27")
      (footprint "eagle-import:B1,27")
      (libsource (lib "eagle-import") (part "TPB1,27"))
    )
    (comp (ref "U$3")
      (value "TPS54233")
      (footprint "eagle-import:SO8")
      (libsource (lib "eagle-import") (part "TPS54332"))
    )
    (comp (ref "VBAT")
      (value "3,81/1,4")
      (footprint "eagle-import:3,81_1,4")
      (libsource (lib "eagle-import") (part "3,81/1,4"))
    )
    (comp (ref "C8")
      (value "33nF")
      (footprint "eagle-import:0603-CAP")
      (libsource (lib "eagle-import") (part "CAP0603-CAP"))
    )
    (comp (ref "C17")
      (value "33nF")
      (footprint "eagle-import:0603-CAP")
      (libsource (lib "eagle-import") (part "CAP0603-CAP"))
    )
    (comp (ref "C19")
      (value "0,1")
      (footprint "eagle-import:0603-CAP")
      (libsource (lib "eagle-import") (part "CAP0603-CAP"))
    )
    (comp (ref "C20")
      (value "0,1")
      (footprint "eagle-import:0603-CAP")
      (libsource (lib "eagle-import") (part "CAP0603-CAP"))
    )
    (comp (ref "C21")
      (value "0,22")
      (footprint "eagle-import:0603-CAP")
      (libsource (lib "eagle-import") (part "CAP0603-CAP"))
    )
    (comp (ref "C41")
      (value "0,1")
      (footprint "eagle-import:0603-CAP")
      (libsource (lib "eagle-import") (part "CAP0603-CAP"))
    )
    (comp (ref "C42")
      (value "0,1")
      (footprint "eagle-import:0603-CAP")
      (libsource (lib "eagle-import") (part "CAP0603-CAP"))
    )
    (comp (ref "C43")
      (value "0,22")
      (footprint "eagle-import:0603-CAP")
      (libsource (lib "eagle-import") (part "CAP0603-CAP"))
    )
    (comp (ref "IC2")
      (value "VNH2SP30TR-E")
      (footprint "eagle-import:MULTIPOWERSO-30")
      (libsource (lib "eagle-import") (part "VNH3ASP30-E"))
    )
    (comp (ref "IC6")
      (value "VNH2SP30TR-E")
      (footprint "eagle-import:MULTIPOWERSO-30")
      (libsource (lib "eagle-import") (part "VNH3ASP30-E"))
    )
    (comp (ref "LED6")
      (value "LEDCHIP-LED0603")
      (footprint "eagle-import:CHIP-LED0603")
      (libsource (lib "eagle-import") (part "LEDCHIP-LED0603"))
    )
    (comp (ref "LED7")
      (value "LEDCHIP-LED0603")
      (footprint "eagle-import:CHIP-LED0603")
      (libsource (lib "eagle-import") (part "LEDCHIP-LED0603"))
    )
    (comp (ref "LED8")
      (value "LEDCHIP-LED0603")
      (footprint "eagle-import:CHIP-LED0603")
      (libsource (lib "eagle-import") (part "LEDCHIP-LED0603"))
    )
    (comp (ref "LED9")
      (value "LEDCHIP-LED0603")
      (footprint "eagle-import:CHIP-LED0603")
      (libsource (lib "eagle-import") (part "LEDCHIP-LED0603"))
    )
    (comp (ref "PAD92")
      (value "WIREPAD4,16O1,6")
      (footprint "eagle-import:4,16O1,6")
      (libsource (lib "eagle-import") (part "WIREPAD4,16O1,6"))
    )
    (comp (ref "PAD93")
      (value "WIREPAD4,16O1,6")
      (footprint "eagle-import:4,16O1,6")
      (libsource (lib "eagle-import") (part "WIREPAD4,16O1,6"))
    )
    (comp (ref "PAD94")
      (value "WIREPAD4,16O1,6")
      (footprint "eagle-import:4,16O1,6")
      (libsource (lib "eagle-import") (part "WIREPAD4,16O1,6"))
    )
    (comp (ref "PAD95")
      (value "WIREPAD4,16O1,6")
      (footprint "eagle-import:4,16O1,6")
      (libsource (lib "eagle-import") (part "WIREPAD4,16O1,6"))
    )
    (comp (ref "R2")
      (value "3k3")
      (footprint "eagle-import:0603-RES")
      (libsource (lib "eagle-import") (part "RESISTOR0603-RES"))
    )
    (comp (ref "R3")
      (value "1k")
      (footprint "eagle-import:0603-RES")
      (libsource (lib "eagle-import") (part "RESISTOR0603-RES"))
    )
    (comp (ref "R4")
      (value "1k")
      (footprint "eagle-import:0603-RES")
      (libsource (lib "eagle-import") (part "RESISTOR0603-RES"))
    )
    (comp (ref "R5")
      (value "1k")
      (footprint "eagle-import:0603-RES")
      (libsource (lib "eagle-import") (part "RESISTOR0603-RES"))
    )
    (comp (ref "R6")
      (value "1k")
      (footprint "eagle-import:0603-RES")
      (libsource (lib "eagle-import") (part "RESISTOR0603-RES"))
    )
    (comp (ref "R7")
      (value "1k")
      (footprint "eagle-import:0603-RES")
      (libsource (lib "eagle-import") (part "RESISTOR0603-RES"))
    )
    (comp (ref "R12")
      (value "10k")
      (footprint "eagle-import:0603-RES")
      (libsource (lib "eagle-import") (part "RESISTOR0603-RES"))
    )
    (comp (ref "R13")
      (value "1k5")
      (footprint "eagle-import:0603-RES")
      (libsource (lib "eagle-import") (part "RESISTOR0603-RES"))
    )
    (comp (ref "R25")
      (value "3k3")
      (footprint "eagle-import:0603-RES")
      (libsource (lib "eagle-import") (part "RESISTOR0603-RES"))
    )
    (comp (ref "R27")
      (value "3k3")
      (footprint "eagle-import:0603-RES")
      (libsource (lib "eagle-import") (part "RESISTOR0603-RES"))
    )
    (comp (ref "R28")
      (value "3k3")
      (footprint "eagle-import:0603-RES")
      (libsource (lib "eagle-import") (part "RESISTOR0603-RES"))
    )
    (comp (ref "R29")
      (value "10k")
      (footprint "eagle-import:0603-RES")
      (libsource (lib "eagle-import") (part "RESISTOR0603-RES"))
    )
    (comp (ref "R30")
      (value "1k5")
      (footprint "eagle-import:0603-RES")
      (libsource (lib "eagle-import") (part "RESISTOR0603-RES"))
    )
    (comp (ref "R31")
      (value "1k")
      (footprint "eagle-import:0603-RES")
      (libsource (lib "eagle-import") (part "RESISTOR0603-RES"))
    )
    (comp (ref "R32")
      (value "1k")
      (footprint "eagle-import:0603-RES")
      (libsource (lib "eagle-import") (part "RESISTOR0603-RES"))
    )
    (comp (ref "R33")
      (value "1k")
      (footprint "eagle-import:0603-RES")
      (libsource (lib "eagle-import") (part "RESISTOR0603-RES"))
    )
    (comp (ref "R34")
      (value "1k")
      (footprint "eagle-import:0603-RES")
      (libsource (lib "eagle-import") (part "RESISTOR0603-RES"))
    )
    (comp (ref "R36")
      (value "1k")
      (footprint "eagle-import:0603-RES")
      (libsource (lib "eagle-import") (part "RESISTOR0603-RES"))
    )
    (comp (ref "R41")
      (value "1k")
      (footprint "eagle-import:0603-RES")
      (libsource (lib "eagle-import") (part "RESISTOR0603-RES"))
    )
    (comp (ref "R56")
      (value "1k")
      (footprint "eagle-import:0603-RES")
      (libsource (lib "eagle-import") (part "RESISTOR0603-RES"))
    )
    (comp (ref "TP26")
      (value "TPB1,27")
      (footprint "eagle-import:B1,27")
      (libsource (lib "eagle-import") (part "TPB1,27"))
    )
    (comp (ref "TP27")
      (value "TPB1,27")
      (footprint "eagle-import:B1,27")
      (libsource (lib "eagle-import") (part "TPB1,27"))
    )
    (comp (ref "TP28")
      (value "TPB1,27")
      (footprint "eagle-import:B1,27")
      (libsource (lib "eagle-import") (part "TPB1,27"))
    )
    (comp (ref "TP29")
      (value "TPB1,27")
      (footprint "eagle-import:B1,27")
      (libsource (lib "eagle-import") (part "TPB1,27"))
    )
    (comp (ref "TP30")
      (value "TPB1,27")
      (footprint "eagle-import:B1,27")
      (libsource (lib "eagle-import") (part "TPB1,27"))
    )
    (comp (ref "TP31")
      (value "TPB1,27")
      (footprint "eagle-import:B1,27")
      (libsource (lib "eagle-import") (part "TPB1,27"))
    )
    (comp (ref "TP32")
      (value "TPB1,27")
      (footprint "eagle-import:B1,27")
      (libsource (lib "eagle-import") (part "TPB1,27"))
    )
    (comp (ref "TP33")
      (value "TPB1,27")
      (footprint "eagle-import:B1,27")
      (libsource (lib "eagle-import") (part "TPB1,27"))
    )
    (comp (ref "TP34")
      (value "TPB1,27")
      (footprint "eagle-import:B1,27")
      (libsource (lib "eagle-import") (part "TPB1,27"))
    )
    (comp (ref "TP35")
      (value "TPB1,27")
      (footprint "eagle-import:B1,27")
      (libsource (lib "eagle-import") (part "TPB1,27"))
    )
    (comp (ref "TP36")
      (value "TPB1,27")
      (footprint "eagle-import:B1,27")
      (libsource (lib "eagle-import") (part "TPB1,27"))
    )
    (comp (ref "TP37")
      (value "TPB1,27")
      (footprint "eagle-import:B1,27")
      (libsource (lib "eagle-import") (part "TPB1,27"))
    )
    (comp (ref "C3")
      (value "0.1")
      (footprint "eagle-import:0603-CAP")
      (libsource (lib "eagle-import") (part "CAP0603-CAP"))
    )
    (comp (ref "C6")
      (value "0.1")
      (footprint "eagle-import:0603-CAP")
      (libsource (lib "eagle-import") (part "CAP0603-CAP"))
    )
    (comp (ref "TP19")
      (value "TPB1,27")
      (footprint "eagle-import:B1,27")
      (libsource (lib "eagle-import") (part "TPB1,27"))
    )
    (comp (ref "TP20")
      (value "TPB1,27")
      (footprint "eagle-import:B1,27")
      (libsource (lib "eagle-import") (part "TPB1,27"))
    )
    (comp (ref "TP21")
      (value "TPB1,27")
      (footprint "eagle-import:B1,27")
      (libsource (lib "eagle-import") (part "TPB1,27"))
    )
    (comp (ref "TP22")
      (value "TPB1,27")
      (footprint "eagle-import:B1,27")
      (libsource (lib "eagle-import") (part "TPB1,27"))
    )
    (comp (ref "TP23")
      (value "TPB1,27")
      (footprint "eagle-import:B1,27")
      (libsource (lib "eagle-import") (part "TPB1,27"))
    )
    (comp (ref "TP24")
      (value "TPB1,27")
      (footprint "eagle-import:B1,27")
      (libsource (lib "eagle-import") (part "TPB1,27"))
    )
    (comp (ref "TP25")
      (value "TPB1,27")
      (footprint "eagle-import:B1,27")
      (libsource (lib "eagle-import") (part "TPB1,27"))
    )
    (comp (ref "TP49")
      (value "TPB1,27")
      (footprint "eagle-import:B1,27")
      (libsource (lib "eagle-import") (part "TPB1,27"))
    )
    (comp (ref "TP51")
      (value "TPB1,27")
      (footprint "eagle-import:B1,27")
      (libsource (lib "eagle-import") (part "TPB1,27"))
    )
    (comp (ref "U$5")
      (value "MMA7455L")
      (footprint "eagle-import:LGA14")
      (libsource (lib "eagle-import") (part "MMA7455L"))
    )
    (comp (ref "U$6")
      (value "MMA7455L")
      (footprint "eagle-import:LGA14")
      (libsource (lib "eagle-import") (part "MMA7455L"))
    )
    (comp (ref "C1")
      (value "820uF/16V")
      (footprint "eagle-import:153CLV-1014")
      (libsource (lib "eagle-import") (part "CPOL-EU153CLV-1014"))
    )
    (comp (ref "C2")
      (value "820uF/16V")
      (footprint "eagle-import:153CLV-1014")
      (libsource (lib "eagle-import") (part "CPOL-EU153CLV-1014"))
    )
    (comp (ref "C7")
      (value "33n")
      (footprint "eagle-import:0603-CAP")
      (libsource (lib "eagle-import") (part "CAP0603-CAP"))
    )
    (comp (ref "C12")
      (value "100uF/16V")
      (footprint "eagle-import:C_6032-28R")
      (libsource (lib "eagle-import") (part "CPOL-EUC/6032-28R"))
    )
    (comp (ref "C13")
      (value "100uF/16V")
      (footprint "eagle-import:C_6032-28R")
      (libsource (lib "eagle-import") (part "CPOL-EUC/6032-28R"))
    )
    (comp (ref "C31")
      (value "10u")
      (footprint "eagle-import:C1210")
      (libsource (lib "eagle-import") (part "C-EUC1210"))
    )
    (comp (ref "C32")
      (value "100p")
      (footprint "eagle-import:0603-CAP")
      (libsource (lib "eagle-import") (part "CAP0603-CAP"))
    )
    (comp (ref "C36")
      (value "0.1uF 600V")
      (footprint "eagle-import:C1812")
      (libsource (lib "eagle-import") (part "C-EUC1812"))
    )
    (comp (ref "CHGLED1")
      (value "LEDCHIPLED_0603")
      (footprint "eagle-import:CHIPLED_0603")
      (libsource (lib "eagle-import") (part "LEDCHIPLED_0603"))
    )
    (comp (ref "CHGLED2")
      (value "LEDCHIPLED_0603")
      (footprint "eagle-import:CHIPLED_0603")
      (libsource (lib "eagle-import") (part "LEDCHIPLED_0603"))
    )
    (comp (ref "D1")
      (value "MURS160")
      (footprint "eagle-import:SMB")
      (libsource (lib "eagle-import") (part "ES2D"))
    )
    (comp (ref "D4")
      (value "BAT54")
      (footprint "eagle-import:SOT23")
      (libsource (lib "eagle-import") (part "BAT54"))
    )
    (comp (ref "LSP1")
      (value "LSP11")
      (footprint "eagle-import:LSP11")
      (libsource (lib "eagle-import") (part "LSP11"))
    )
    (comp (ref "LSP2")
      (value "LSP11")
      (footprint "eagle-import:LSP11")
      (libsource (lib "eagle-import") (part "LSP11"))
    )
    (comp (ref "LT3750")
      (value "LT3750")
      (footprint "eagle-import:MSOP")
      (libsource (lib "eagle-import") (part "LT3750"))
    )
    (comp (ref "PAD25")
      (value "1,6/0,9")
      (footprint "eagle-import:1,6_0,9")
      (libsource (lib "eagle-import") (part "1,6/0,9"))
    )
    (comp (ref "R20")
      (value "8m")
      (footprint "eagle-import:R1210")
      (libsource (lib "eagle-import") (part "R-EU_R1210"))
    )
    (comp (ref "R21")
      (value "43k")
      (footprint "eagle-import:0603-RES")
      (libsource (lib "eagle-import") (part "RESISTOR0603-RES"))
    )
    (comp (ref "R22")
      (value "1.87k")
      (footprint "eagle-import:0603-RES")
      (libsource (lib "eagle-import") (part "RESISTOR0603-RES"))
    )
    (comp (ref "R23")
      (value "10k")
      (footprint "eagle-import:0603-RES")
      (libsource (lib "eagle-import") (part "RESISTOR0603-RES"))
    )
    (comp (ref "R24")
      (value "60.4k")
      (footprint "eagle-import:0603-RES")
      (libsource (lib "eagle-import") (part "RESISTOR0603-RES"))
    )
    (comp (ref "R57")
      (value "400k")
      (footprint "eagle-import:R1210")
      (libsource (lib "eagle-import") (part "R-US_R1210"))
    )
    (comp (ref "TP12")
      (value "TPB1,27")
      (footprint "eagle-import:B1,27")
      (libsource (lib "eagle-import") (part "TPB1,27"))
    )
    (comp (ref "TP13")
      (value "TPB1,27")
      (footprint "eagle-import:B1,27")
      (libsource (lib "eagle-import") (part "TPB1,27"))
    )
    (comp (ref "TP14")
      (value "TPB1,27")
      (footprint "eagle-import:B1,27")
      (libsource (lib "eagle-import") (part "TPB1,27"))
    )
    (comp (ref "TP15")
      (value "TPB1,27")
      (footprint "eagle-import:B1,27")
      (libsource (lib "eagle-import") (part "TPB1,27"))
    )
    (comp (ref "TP16")
      (value "TPB1,27")
      (footprint "eagle-import:B1,27")
      (libsource (lib "eagle-import") (part "TPB1,27"))
    )
    (comp (ref "TP17")
      (value "TPB1,27")
      (footprint "eagle-import:B1,27")
      (libsource (lib "eagle-import") (part "TPB1,27"))
    )
    (comp (ref "TP18")
      (value "TPB1,27")
      (footprint "eagle-import:B1,27")
      (libsource (lib "eagle-import") (part "TPB1,27"))
    )
    (comp (ref "TP59")
      (value "TPB1,27")
      (footprint "eagle-import:B1,27")
      (libsource (lib "eagle-import") (part "TPB1,27"))
    )
    (comp (ref "U$1")
      (value "DA2032-ALBDA2032-ALB")
      (footprint "eagle-import:DA2032-ALB")
      (libsource (lib "eagle-import") (part "DA2032-ALBDA2032-ALB"))
    )
    (comp (ref "U$102")
      (value "IRF7855PBF")
      (footprint "eagle-import:SO8")
      (libsource (lib "eagle-import") (part "IRF8252"))
    )
    (comp (ref "C18")
      (value "0.1")
      (footprint "eagle-import:C0603")
      (libsource (lib "eagle-import") (part "C-EUC0603"))
    )
    (comp (ref "C25")
      (value "CPOL-EUD/7343-31R")
      (footprint "eagle-import:D_7343-31R")
      (libsource (lib "eagle-import") (part "CPOL-EUD/7343-31R"))
    )
    (comp (ref "C30")
      (value "0.1")
      (footprint "eagle-import:C0603")
      (libsource (lib "eagle-import") (part "C-EUC0603"))
    )
    (comp (ref "C47")
      (value "470nF")
      (footprint "eagle-import:0603-CAP")
      (libsource (lib "eagle-import") (part "CAP0603-CAP"))
    )
    (comp (ref "C48")
      (value "10nF")
      (footprint "eagle-import:0603-CAP")
      (libsource (lib "eagle-import") (part "CAP0603-CAP"))
    )
    (comp (ref "C64")
      (value "0.1")
      (footprint "eagle-import:0603-CAP")
      (libsource (lib "eagle-import") (part "CAP0603-CAP"))
    )
    (comp (ref "IC1")
      (value "TPS773")
      (footprint "eagle-import:MSOP8")
      (libsource (lib "eagle-import") (part "TPS773"))
    )
    (comp (ref "J4")
      (value "XF2L-0625-1")
      (footprint "eagle-import:XF2L-0625-1")
      (fields (field (name "MF") "OMRON COMPONENTS USA"))
      (libsource (lib "eagle-import") (part "XF2-06?25-1L"))
    )
    (comp (ref "J5")
      (value "XF2L-0625-1")
      (footprint "eagle-import:XF2L-0625-1")
      (fields (field (name "MF") "OMRON COMPONENTS USA"))
      (libsource (lib "eagle-import") (part "XF2-06?25-1L"))
    )
    (comp (ref "R9")
      (value "10k")
      (footprint "eagle-import:0603-RES")
      (libsource (lib "eagle-import") (part "RESISTOR0603-RES"))
    )
    (comp (ref "R58")
      (value "10k")
      (footprint "eagle-import:0603-RES")
      (libsource (lib "eagle-import") (part "RESISTOR0603-RES"))
    )
    (comp (ref "TP38")
      (value "TPB1,27")
      (footprint "eagle-import:B1,27")
      (libsource (lib "eagle-import") (part "TPB1,27"))
    )
    (comp (ref "TP39")
      (value "TPB1,27")
      (footprint "eagle-import:B1,27")
      (libsource (lib "eagle-import") (part "TPB1,27"))
    )
    (comp (ref "TP40")
      (value "TPB1,27")
      (footprint "eagle-import:B1,27")
      (libsource (lib "eagle-import") (part "TPB1,27"))
    )
    (comp (ref "TP41")
      (value "TPB1,27")
      (footprint "eagle-import:B1,27")
      (libsource (lib "eagle-import") (part "TPB1,27"))
    )
    (comp (ref "TP42")
      (value "TPB1,27")
      (footprint "eagle-import:B1,27")
      (libsource (lib "eagle-import") (part "TPB1,27"))
    )
    (comp (ref "TP43")
      (value "TPB1,27")
      (footprint "eagle-import:B1,27")
      (libsource (lib "eagle-import") (part "TPB1,27"))
    )
    (comp (ref "U2")
      (value "L3G4200D")
      (footprint "eagle-import:LGA16-4X4")
      (libsource (lib "eagle-import") (part "L3G4200D"))
    )
    (comp (ref "PAD3")
      (value "1,6/0,9")
      (footprint "eagle-import:1,6_0,9")
      (libsource (lib "eagle-import") (part "1,6/0,9"))
    )
    (comp (ref "PAD4")
      (value "1,6/0,9")
      (footprint "eagle-import:1,6_0,9")
      (libsource (lib "eagle-import") (part "1,6/0,9"))
    )
    (comp (ref "PAD7")
      (value "1,6/0,9")
      (footprint "eagle-import:1,6_0,9")
      (libsource (lib "eagle-import") (part "1,6/0,9"))
    )
    (comp (ref "PAD8")
      (value "1,6/0,9")
      (footprint "eagle-import:1,6_0,9")
      (libsource (lib "eagle-import") (part "1,6/0,9"))
    )
    (comp (ref "PAD9")
      (value "1,6/0,9")
      (footprint "eagle-import:1,6_0,9")
      (libsource (lib "eagle-import") (part "1,6/0,9"))
    )
    (comp (ref "PAD10")
      (value "1,6/0,9")
      (footprint "eagle-import:1,6_0,9")
      (libsource (lib "eagle-import") (part "1,6/0,9"))
    )
    (comp (ref "PAD11")
      (value "1,6/0,9")
      (footprint "eagle-import:1,6_0,9")
      (libsource (lib "eagle-import") (part "1,6/0,9"))
    )
    (comp (ref "PAD12")
      (value "1,6/0,9")
      (footprint "eagle-import:1,6_0,9")
      (libsource (lib "eagle-import") (part "1,6/0,9"))
    )
    (comp (ref "PAD13")
      (value "1,6/0,9")
      (footprint "eagle-import:1,6_0,9")
      (libsource (lib "eagle-import") (part "1,6/0,9"))
    )
    (comp (ref "PAD14")
      (value "1,6/0,9")
      (footprint "eagle-import:1,6_0,9")
      (libsource (lib "eagle-import") (part "1,6/0,9"))
    )
    (comp (ref "PAD15")
      (value "1,6/0,9")
      (footprint "eagle-import:1,6_0,9")
      (libsource (lib "eagle-import") (part "1,6/0,9"))
    )
    (comp (ref "PAD16")
      (value "1,6/0,9")
      (footprint "eagle-import:1,6_0,9")
      (libsource (lib "eagle-import") (part "1,6/0,9"))
    )
    (comp (ref "PAD17")
      (value "1,6/0,9")
      (footprint "eagle-import:1,6_0,9")
      (libsource (lib "eagle-import") (part "1,6/0,9"))
    )
    (comp (ref "PAD18")
      (value "1,6/0,9")
      (footprint "eagle-import:1,6_0,9")
      (libsource (lib "eagle-import") (part "1,6/0,9"))
    )
    (comp (ref "PAD19")
      (value "1,6/0,9")
      (footprint "eagle-import:1,6_0,9")
      (libsource (lib "eagle-import") (part "1,6/0,9"))
    )
    (comp (ref "PAD20")
      (value "1,6/0,9")
      (footprint "eagle-import:1,6_0,9")
      (libsource (lib "eagle-import") (part "1,6/0,9"))
    )
    (comp (ref "PAD21")
      (value "1,6/0,9")
      (footprint "eagle-import:1,6_0,9")
      (libsource (lib "eagle-import") (part "1,6/0,9"))
    )
    (comp (ref "PAD22")
      (value "1,6/0,9")
      (footprint "eagle-import:1,6_0,9")
      (libsource (lib "eagle-import") (part "1,6/0,9"))
    )
    (comp (ref "PAD23")
      (value "1,6/0,9")
      (footprint "eagle-import:1,6_0,9")
      (libsource (lib "eagle-import") (part "1,6/0,9"))
    )
    (comp (ref "PAD24")
      (value "1,6/0,9")
      (footprint "eagle-import:1,6_0,9")
      (libsource (lib "eagle-import") (part "1,6/0,9"))
    )
    (comp (ref "PAD26")
      (value "WIREPAD1,6/0,8")
      (footprint "eagle-import:1,6_0,8")
      (libsource (lib "eagle-import") (part "WIREPAD1,6/0,8"))
    )
    (comp (ref "PAD27")
      (value "WIREPAD1,6/0,8")
      (footprint "eagle-import:1,6_0,8")
      (libsource (lib "eagle-import") (part "WIREPAD1,6/0,8"))
    )
    (comp (ref "PAD28")
      (value "WIREPAD1,6/0,8")
      (footprint "eagle-import:1,6_0,8")
      (libsource (lib "eagle-import") (part "WIREPAD1,6/0,8"))
    )
    (comp (ref "PAD29")
      (value "WIREPAD1,6/0,8")
      (footprint "eagle-import:1,6_0,8")
      (libsource (lib "eagle-import") (part "WIREPAD1,6/0,8"))
    )
    (comp (ref "PAD30")
      (value "WIREPAD1,6/0,8")
      (footprint "eagle-import:1,6_0,8")
      (libsource (lib "eagle-import") (part "WIREPAD1,6/0,8"))
    )
    (comp (ref "PAD31")
      (value "WIREPAD1,6/0,8")
      (footprint "eagle-import:1,6_0,8")
      (libsource (lib "eagle-import") (part "WIREPAD1,6/0,8"))
    )
    (comp (ref "PAD32")
      (value "WIREPAD1,6/0,8")
      (footprint "eagle-import:1,6_0,8")
      (libsource (lib "eagle-import") (part "WIREPAD1,6/0,8"))
    )
    (comp (ref "PAD33")
      (value "WIREPAD1,6/0,8")
      (footprint "eagle-import:1,6_0,8")
      (libsource (lib "eagle-import") (part "WIREPAD1,6/0,8"))
    )
    (comp (ref "PAD34")
      (value "WIREPAD1,6/0,8")
      (footprint "eagle-import:1,6_0,8")
      (libsource (lib "eagle-import") (part "WIREPAD1,6/0,8"))
    )
    (comp (ref "PAD35")
      (value "WIREPAD1,6/0,8")
      (footprint "eagle-import:1,6_0,8")
      (libsource (lib "eagle-import") (part "WIREPAD1,6/0,8"))
    )
    (comp (ref "PAD36")
      (value "WIREPAD1,6/0,8")
      (footprint "eagle-import:1,6_0,8")
      (libsource (lib "eagle-import") (part "WIREPAD1,6/0,8"))
    )
    (comp (ref "PAD37")
      (value "WIREPAD1,6/0,8")
      (footprint "eagle-import:1,6_0,8")
      (libsource (lib "eagle-import") (part "WIREPAD1,6/0,8"))
    )
    (comp (ref "PAD38")
      (value "WIREPAD1,6/0,8")
      (footprint "eagle-import:1,6_0,8")
      (libsource (lib "eagle-import") (part "WIREPAD1,6/0,8"))
    )
    (comp (ref "PAD39")
      (value "WIREPAD1,6/0,8")
      (footprint "eagle-import:1,6_0,8")
      (libsource (lib "eagle-import") (part "WIREPAD1,6/0,8"))
    )
    (comp (ref "PAD40")
      (value "WIREPAD1,6/0,8")
      (footprint "eagle-import:1,6_0,8")
      (libsource (lib "eagle-import") (part "WIREPAD1,6/0,8"))
    )
    (comp (ref "PAD41")
      (value "WIREPAD1,6/0,8")
      (footprint "eagle-import:1,6_0,8")
      (libsource (lib "eagle-import") (part "WIREPAD1,6/0,8"))
    )
    (comp (ref "PAD42")
      (value "WIREPAD1,6/0,8")
      (footprint "eagle-import:1,6_0,8")
      (libsource (lib "eagle-import") (part "WIREPAD1,6/0,8"))
    )
    (comp (ref "PAD43")
      (value "WIREPAD1,6/0,8")
      (footprint "eagle-import:1,6_0,8")
      (libsource (lib "eagle-import") (part "WIREPAD1,6/0,8"))
    )
    (comp (ref "PAD44")
      (value "WIREPAD1,6/0,8")
      (footprint "eagle-import:1,6_0,8")
      (libsource (lib "eagle-import") (part "WIREPAD1,6/0,8"))
    )
    (comp (ref "PAD45")
      (value "WIREPAD1,6/0,8")
      (footprint "eagle-import:1,6_0,8")
      (libsource (lib "eagle-import") (part "WIREPAD1,6/0,8"))
    )
    (comp (ref "PAD46")
      (value "WIREPAD1,6/0,8")
      (footprint "eagle-import:1,6_0,8")
      (libsource (lib "eagle-import") (part "WIREPAD1,6/0,8"))
    )
    (comp (ref "PAD47")
      (value "WIREPAD1,6/0,8")
      (footprint "eagle-import:1,6_0,8")
      (libsource (lib "eagle-import") (part "WIREPAD1,6/0,8"))
    )
    (comp (ref "PAD48")
      (value "WIREPAD1,6/0,8")
      (footprint "eagle-import:1,6_0,8")
      (libsource (lib "eagle-import") (part "WIREPAD1,6/0,8"))
    )
    (comp (ref "PAD49")
      (value "WIREPAD1,6/0,8")
      (footprint "eagle-import:1,6_0,8")
      (libsource (lib "eagle-import") (part "WIREPAD1,6/0,8"))
    )
    (comp (ref "PAD50")
      (value "WIREPAD1,6/0,8")
      (footprint "eagle-import:1,6_0,8")
      (libsource (lib "eagle-import") (part "WIREPAD1,6/0,8"))
    )
    (comp (ref "PAD51")
      (value "WIREPAD1,6/0,8")
      (footprint "eagle-import:1,6_0,8")
      (libsource (lib "eagle-import") (part "WIREPAD1,6/0,8"))
    )
    (comp (ref "PAD52")
      (value "WIREPAD1,6/0,8")
      (footprint "eagle-import:1,6_0,8")
      (libsource (lib "eagle-import") (part "WIREPAD1,6/0,8"))
    )
    (comp (ref "PAD53")
      (value "WIREPAD1,6/0,8")
      (footprint "eagle-import:1,6_0,8")
      (libsource (lib "eagle-import") (part "WIREPAD1,6/0,8"))
    )
    (comp (ref "PAD54")
      (value "WIREPAD1,6/0,8")
      (footprint "eagle-import:1,6_0,8")
      (libsource (lib "eagle-import") (part "WIREPAD1,6/0,8"))
    )
    (comp (ref "PAD55")
      (value "WIREPAD1,6/0,8")
      (footprint "eagle-import:1,6_0,8")
      (libsource (lib "eagle-import") (part "WIREPAD1,6/0,8"))
    )
    (comp (ref "PAD56")
      (value "WIREPAD1,6/0,8")
      (footprint "eagle-import:1,6_0,8")
      (libsource (lib "eagle-import") (part "WIREPAD1,6/0,8"))
    )
    (comp (ref "PAD57")
      (value "WIREPAD1,6/0,8")
      (footprint "eagle-import:1,6_0,8")
      (libsource (lib "eagle-import") (part "WIREPAD1,6/0,8"))
    )
    (comp (ref "PAD58")
      (value "WIREPAD1,6/0,8")
      (footprint "eagle-import:1,6_0,8")
      (libsource (lib "eagle-import") (part "WIREPAD1,6/0,8"))
    )
    (comp (ref "PAD59")
      (value "WIREPAD1,6/0,8")
      (footprint "eagle-import:1,6_0,8")
      (libsource (lib "eagle-import") (part "WIREPAD1,6/0,8"))
    )
    (comp (ref "PAD60")
      (value "WIREPAD1,6/0,8")
      (footprint "eagle-import:1,6_0,8")
      (libsource (lib "eagle-import") (part "WIREPAD1,6/0,8"))
    )
    (comp (ref "PAD61")
      (value "WIREPAD1,6/0,8")
      (footprint "eagle-import:1,6_0,8")
      (libsource (lib "eagle-import") (part "WIREPAD1,6/0,8"))
    )
    (comp (ref "PAD62")
      (value "WIREPAD1,6/0,8")
      (footprint "eagle-import:1,6_0,8")
      (libsource (lib "eagle-import") (part "WIREPAD1,6/0,8"))
    )
    (comp (ref "PAD63")
      (value "WIREPAD1,6/0,8")
      (footprint "eagle-import:1,6_0,8")
      (libsource (lib "eagle-import") (part "WIREPAD1,6/0,8"))
    )
    (comp (ref "PAD64")
      (value "WIREPAD1,6/0,8")
      (footprint "eagle-import:1,6_0,8")
      (libsource (lib "eagle-import") (part "WIREPAD1,6/0,8"))
    )
    (comp (ref "PAD65")
      (value "WIREPAD1,6/0,8")
      (footprint "eagle-import:1,6_0,8")
      (libsource (lib "eagle-import") (part "WIREPAD1,6/0,8"))
    )
    (comp (ref "PAD66")
      (value "WIREPAD1,6/0,8")
      (footprint "eagle-import:1,6_0,8")
      (libsource (lib "eagle-import") (part "WIREPAD1,6/0,8"))
    )
    (comp (ref "PAD67")
      (value "WIREPAD1,6/0,8")
      (footprint "eagle-import:1,6_0,8")
      (libsource (lib "eagle-import") (part "WIREPAD1,6/0,8"))
    )
    (comp (ref "PAD68")
      (value "WIREPAD1,6/0,8")
      (footprint "eagle-import:1,6_0,8")
      (libsource (lib "eagle-import") (part "WIREPAD1,6/0,8"))
    )
    (comp (ref "PAD69")
      (value "WIREPAD1,6/0,8")
      (footprint "eagle-import:1,6_0,8")
      (libsource (lib "eagle-import") (part "WIREPAD1,6/0,8"))
    )
    (comp (ref "PAD70")
      (value "WIREPAD1,6/0,8")
      (footprint "eagle-import:1,6_0,8")
      (libsource (lib "eagle-import") (part "WIREPAD1,6/0,8"))
    )
    (comp (ref "PAD71")
      (value "WIREPAD1,6/0,8")
      (footprint "eagle-import:1,6_0,8")
      (libsource (lib "eagle-import") (part "WIREPAD1,6/0,8"))
    )
    (comp (ref "PAD72")
      (value "WIREPAD1,6/0,8")
      (footprint "eagle-import:1,6_0,8")
      (libsource (lib "eagle-import") (part "WIREPAD1,6/0,8"))
    )
    (comp (ref "PAD73")
      (value "WIREPAD1,6/0,8")
      (footprint "eagle-import:1,6_0,8")
      (libsource (lib "eagle-import") (part "WIREPAD1,6/0,8"))
    )
    (comp (ref "PAD74")
      (value "WIREPAD1,6/0,8")
      (footprint "eagle-import:1,6_0,8")
      (libsource (lib "eagle-import") (part "WIREPAD1,6/0,8"))
    )
    (comp (ref "PAD75")
      (value "WIREPAD1,6/0,8")
      (footprint "eagle-import:1,6_0,8")
      (libsource (lib "eagle-import") (part "WIREPAD1,6/0,8"))
    )
    (comp (ref "PAD76")
      (value "WIREPAD1,6/0,8")
      (footprint "eagle-import:1,6_0,8")
      (libsource (lib "eagle-import") (part "WIREPAD1,6/0,8"))
    )
    (comp (ref "PAD77")
      (value "WIREPAD1,6/0,8")
      (footprint "eagle-import:1,6_0,8")
      (libsource (lib "eagle-import") (part "WIREPAD1,6/0,8"))
    )
    (comp (ref "PAD78")
      (value "WIREPAD1,6/0,8")
      (footprint "eagle-import:1,6_0,8")
      (libsource (lib "eagle-import") (part "WIREPAD1,6/0,8"))
    )
    (comp (ref "PAD79")
      (value "WIREPAD1,6/0,8")
      (footprint "eagle-import:1,6_0,8")
      (libsource (lib "eagle-import") (part "WIREPAD1,6/0,8"))
    )
    (comp (ref "PAD80")
      (value "WIREPAD1,6/0,8")
      (footprint "eagle-import:1,6_0,8")
      (libsource (lib "eagle-import") (part "WIREPAD1,6/0,8"))
    )
    (comp (ref "PAD81")
      (value "WIREPAD1,6/0,8")
      (footprint "eagle-import:1,6_0,8")
      (libsource (lib "eagle-import") (part "WIREPAD1,6/0,8"))
    )
    (comp (ref "PAD82")
      (value "WIREPAD1,6/0,8")
      (footprint "eagle-import:1,6_0,8")
      (libsource (lib "eagle-import") (part "WIREPAD1,6/0,8"))
    )
    (comp (ref "PAD83")
      (value "WIREPAD1,6/0,8")
      (footprint "eagle-import:1,6_0,8")
      (libsource (lib "eagle-import") (part "WIREPAD1,6/0,8"))
    )
    (comp (ref "PAD84")
      (value "WIREPAD1,6/0,8")
      (footprint "eagle-import:1,6_0,8")
      (libsource (lib "eagle-import") (part "WIREPAD1,6/0,8"))
    )
    (comp (ref "PAD85")
      (value "WIREPAD1,6/0,8")
      (footprint "eagle-import:1,6_0,8")
      (libsource (lib "eagle-import") (part "WIREPAD1,6/0,8"))
    )
    (comp (ref "PAD86")
      (value "WIREPAD1,6/0,8")
      (footprint "eagle-import:1,6_0,8")
      (libsource (lib "eagle-import") (part "WIREPAD1,6/0,8"))
    )
    (comp (ref "PAD87")
      (value "WIREPAD1,6/0,8")
      (footprint "eagle-import:1,6_0,8")
      (libsource (lib "eagle-import") (part "WIREPAD1,6/0,8"))
    )
    (comp (ref "PAD88")
      (value "WIREPAD1,6/0,8")
      (footprint "eagle-import:1,6_0,8")
      (libsource (lib "eagle-import") (part "WIREPAD1,6/0,8"))
    )
    (comp (ref "PAD89")
      (value "WIREPAD1,6/0,8")
      (footprint "eagle-import:1,6_0,8")
      (libsource (lib "eagle-import") (part "WIREPAD1,6/0,8"))
    )
    (comp (ref "PAD90")
      (value "WIREPAD1,6/0,8")
      (footprint "eagle-import:1,6_0,8")
      (libsource (lib "eagle-import") (part "WIREPAD1,6/0,8"))
    )
    (comp (ref "PAD91")
      (value "WIREPAD1,6/0,8")
      (footprint "eagle-import:1,6_0,8")
      (libsource (lib "eagle-import") (part "WIREPAD1,6/0,8"))
    )
    (comp (ref "J3")
      (value "PINHD-2X14")
      (footprint "eagle-import:2X14")
      (libsource (lib "eagle-import") (part "PINHD-2X14"))
    )
    (comp (ref "J6")
      (value "PINHD-2X14")
      (footprint "eagle-import:2X14")
      (libsource (lib "eagle-import") (part "PINHD-2X14"))
    )
    (comp (ref "R59")
      (value "10k")
      (footprint "eagle-import:R0603")
      (libsource (lib "eagle-import") (part "R-US_R0603"))
    )
    (comp (ref "R60")
      (value "10k")
      (footprint "eagle-import:R0603")
      (libsource (lib "eagle-import") (part "R-US_R0603"))
    )
    (comp (ref "TP73")
      (value "TPB1,27")
      (footprint "eagle-import:B1,27")
      (libsource (lib "eagle-import") (part "TPB1,27"))
    )
    (comp (ref "TP74")
      (value "TPB1,27")
      (footprint "eagle-import:B1,27")
      (libsource (lib "eagle-import") (part "TPB1,27"))
    )
    (comp (ref "TP75")
      (value "TPB1,27")
      (footprint "eagle-import:B1,27")
      (libsource (lib "eagle-import") (part "TPB1,27"))
    )
    (comp (ref "TP76")
      (value "TPB1,27")
      (footprint "eagle-import:B1,27")
      (libsource (lib "eagle-import") (part "TPB1,27"))
    )
    (comp (ref "TP77")
      (value "TPB1,27")
      (footprint "eagle-import:B1,27")
      (libsource (lib "eagle-import") (part "TPB1,27"))
    )
    (comp (ref "TP78")
      (value "TPB1,27")
      (footprint "eagle-import:B1,27")
      (libsource (lib "eagle-import") (part "TPB1,27"))
    )
    (comp (ref "TP79")
      (value "TPB1,27")
      (footprint "eagle-import:B1,27")
      (libsource (lib "eagle-import") (part "TPB1,27"))
    )
    (comp (ref "TP80")
      (value "TPB1,27")
      (footprint "eagle-import:B1,27")
      (libsource (lib "eagle-import") (part "TPB1,27"))
    )
    (comp (ref "U1")
      (value "txb0108")
      (footprint "eagle-import:TSSOP20")
      (libsource (lib "eagle-import") (part "TXB0108PWR"))
    )
    (comp (ref "X4")
      (value "USB-A-S")
      (footprint "eagle-import:USB-A-S")
      (libsource (lib "eagle-import") (part "USB-A-S"))
    )
    (comp (ref "X7")
      (value "SDBMF")
      (footprint "eagle-import:SDBMF-009XXBXX2")
      (libsource (lib "eagle-import") (part "SDBMF"))
    )
  )
  (nets
    (net (code "1") (name "+3V3") (class "Default")
      (node (ref "C16") (pin "2") (pinfunction "2_2") (pintype "passive"))
      (node (ref "C22") (pin "2") (pinfunction "2_2") (pintype "passive"))
      (node (ref "C23") (pin "2") (pinfunction "2_2") (pintype "passive"))
      (node (ref "C24") (pin "2") (pinfunction "2_2") (pintype "passive"))
      (node (ref "C28") (pin "1") (pinfunction "1_1") (pintype "passive"))
      (node (ref "C3") (pin "1") (pinfunction "1_1") (pintype "passive"))
      (node (ref "C51") (pin "1") (pinfunction "1_1") (pintype "passive"))
      (node (ref "C52") (pin "1") (pinfunction "1_1") (pintype "passive"))
      (node (ref "C56") (pin "1") (pinfunction "1_1") (pintype "passive"))
      (node (ref "C58") (pin "1") (pinfunction "1_1") (pintype "passive"))
      (node (ref "C6") (pin "1") (pinfunction "1_1") (pintype "passive"))
      (node (ref "C61") (pin "1") (pinfunction "1_1") (pintype "passive"))
      (node (ref "C62") (pin "1") (pinfunction "1_1") (pintype "passive"))
      (node (ref "C64") (pin "1") (pinfunction "1_1") (pintype "passive"))
      (node (ref "C71") (pin "2") (pinfunction "2_2") (pintype "passive"))
      (node (ref "C72") (pin "2") (pinfunction "2_2") (pintype "passive"))
      (node (ref "IC3") (pin "3") (pinfunction "VCC_3") (pintype "power_in"))
      (node (ref "IC8") (pin "3") (pinfunction "VO_3") (pintype "passive"))
      (node (ref "J1") (pin "24") (pinfunction "MS_24") (pintype "passive"))
      (node (ref "J1") (pin "26") (pinfunction "MS_26") (pintype "passive"))
      (node (ref "JP1") (pin "8") (pinfunction "8_8") (pintype "passive"))
      (node (ref "L3") (pin "1") (pinfunction "2_1") (pintype "passive"))
      (node (ref "LED2") (pin "A") (pinfunction "A_A") (pintype "passive"))
      (node (ref "MCU") (pin "14") (pinfunction "VCC1_14") (pintype "power_in"))
      (node (ref "MCU") (pin "60") (pinfunction "VCC2_60") (pintype "power_in"))
      (node (ref "R1") (pin "2") (pinfunction "2_2") (pintype "passive"))
      (node (ref "R2") (pin "2") (pinfunction "2_2") (pintype "passive"))
      (node (ref "R23") (pin "1") (pinfunction "1_1") (pintype "passive"))
      (node (ref "R25") (pin "2") (pinfunction "2_2") (pintype "passive"))
      (node (ref "R27") (pin "2") (pinfunction "2_2") (pintype "passive"))
      (node (ref "R28") (pin "2") (pinfunction "2_2") (pintype "passive"))
      (node (ref "R44") (pin "1") (pinfunction "1_1") (pintype "passive"))
      (node (ref "R45") (pin "1") (pinfunction "1_1") (pintype "passive"))
      (node (ref "R46") (pin "1") (pinfunction "1_1") (pintype "passive"))
      (node (ref "R48") (pin "2") (pinfunction "2_2") (pintype "passive"))
      (node (ref "R53") (pin "2") (pinfunction "2_2") (pintype "passive"))
      (node (ref "R58") (pin "1") (pinfunction "1_1") (pintype "passive"))
      (node (ref "R61") (pin "2") (pinfunction "2_2") (pintype "passive"))
      (node (ref "R62") (pin "2") (pinfunction "2_2") (pintype "passive"))
      (node (ref "TP7") (pin "TP") (pinfunction "TP_TP") (pintype "input"))
      (node (ref "U$5") (pin "1") (pinfunction "DVDD_IO_1") (pintype "bidirectional"))
      (node (ref "U$5") (pin "6") (pinfunction "AVDD_6") (pintype "bidirectional"))
      (node (ref "U$6") (pin "1") (pinfunction "DVDD_IO_1") (pintype "bidirectional"))
      (node (ref "U$6") (pin "6") (pinfunction "AVDD_6") (pintype "bidirectional"))
      (node (ref "U1") (pin "19") (pinfunction "VCCB_19") (pintype "bidirectional"))
      (node (ref "U2") (pin "1") (pinfunction "VDDIO_1") (pintype "bidirectional"))
      (node (ref "U2") (pin "15") (pinfunction "RSVDV_15") (pintype "bidirectional"))
      (node (ref "U2") (pin "16") (pinfunction "VDD_16") (pintype "bidirectional"))
      (node (ref "X7") (pin "3") (pinfunction "3_3") (pintype "passive"))
    )
    (net (code "2") (name "+5V_PANDA") (class "Default")
      (node (ref "5V") (pin "1") (pinfunction "1_1") (pintype "passive"))
      (node (ref "C100") (pin "+") (pinfunction "+_+") (pintype "passive"))
      (node (ref "C29") (pin "1") (pinfunction "1_1") (pintype "passive"))
      (node (ref "C33") (pin "+") (pinfunction "+_+") (pintype "passive"))
      (node (ref "C9") (pin "1") (pinfunction "1_1") (pintype "passive"))
      (node (ref "L1") (pin "P$2") (pinfunction "2_P$2") (pintype "passive"))
      (node (ref "R37") (pin "1") (pinfunction "1_1") (pintype "passive"))
      (node (ref "TP55") (pin "TP") (pinfunction "TP_TP") (pintype "input"))
    )
    (net (code "3") (name "5V_MELEXIS") (class "Default")
      (node (ref "C25") (pin "+") (pinfunction "+_+") (pintype "passive"))
      (node (ref "C30") (pin "1") (pinfunction "1_1") (pintype "passive"))
      (node (ref "IC1") (pin "1") (pinfunction "FB\\SENSE_1") (pintype "input"))
      (node (ref "IC1") (pin "7") (pinfunction "OUT_7") (pintype "output"))
      (node (ref "IC1") (pin "8") (pinfunction "OUT_8") (pintype "passive"))
      (node (ref "J4") (pin "5") (pinfunction "MS_5") (pintype "passive"))
      (node (ref "J5") (pin "5") (pinfunction "MS_5") (pintype "passive"))
    )
    (net (code "4") (name "12V5") (class "Default")
      (node (ref "C49") (pin "1") (pinfunction "1_1") (pintype "passive"))
      (node (ref "C5") (pin "1") (pinfunction "1_1") (pintype "passive"))
      (node (ref "C54") (pin "1") (pinfunction "1_1") (pintype "passive"))
      (node (ref "C59") (pin "1") (pinfunction "1_1") (pintype "passive"))
      (node (ref "D3") (pin "C") (pinfunction "C_C") (pintype "passive"))
      (node (ref "J1") (pin "29") (pinfunction "MS_29") (pintype "passive"))
      (node (ref "J1") (pin "3") (pinfunction "MS_3") (pintype "passive"))
      (node (ref "R14") (pin "2") (pinfunction "2_2") (pintype "passive"))
      (node (ref "TP52") (pin "TP") (pinfunction "TP_TP") (pintype "input"))
    )
    (net (code "5") (name "12V5VIN") (class "Default")
      (node (ref "C26") (pin "1") (pinfunction "1_1") (pintype "passive"))
      (node (ref "L2") (pin "2") (pinfunction "1_2") (pintype "passive"))
      (node (ref "Q2") (pin "3") (pinfunction "D_3") (pintype "passive"))
      (node (ref "TP10") (pin "TP") (pinfunction "TP_TP") (pintype "input"))
      (node (ref "U$2") (pin "4") (pinfunction "EN_4") (pintype "input"))
      (node (ref "U$2") (pin "5") (pinfunction "VIN_5") (pintype "power_in"))
    )
    (net (code "6") (name "400V") (class "Default")
      (node (ref "C36") (pin "1") (pinfunction "1_1") (pintype "passive"))
      (node (ref "D1") (pin "C") (pinfunction "C_C") (pintype "passive"))
      (node (ref "LSP1") (pin "MP") (pinfunction "MP_MP") (pintype "passive"))
      (node (ref "R57") (pin "2") (pinfunction "2_2") (pintype "passive"))
    )
    (net (code "7") (name "AN0") (class "Default")
      (node (ref "C8") (pin "1") (pinfunction "1_1") (pintype "passive"))
      (node (ref "MCU") (pin "95") (pinfunction "P100/AN00_95") (pintype "bidirectional"))
      (node (ref "R29") (pin "2") (pinfunction "2_2") (pintype "passive"))
      (node (ref "TP31") (pin "TP") (pinfunction "TP_TP") (pintype "input"))
    )
    (net (code "8") (name "AN1") (class "Default")
      (node (ref "C17") (pin "1") (pinfunction "1_1") (pintype "passive"))
      (node (ref "MCU") (pin "93") (pinfunction "P101/AN01_93") (pintype "bidirectional"))
      (node (ref "R12") (pin "2") (pinfunction "2_2") (pintype "passive"))
      (node (ref "TP37") (pin "TP") (pinfunction "TP_TP") (pintype "input"))
    )
    (net (code "9") (name "AN2") (class "Default")
      (node (ref "C7") (pin "1") (pinfunction "1_1") (pintype "passive"))
      (node (ref "CHGLED2") (pin "A") (pinfunction "A_A") (pintype "passive"))
      (node (ref "D4") (pin "3") (pinfunction "C_3") (pintype "passive"))
      (node (ref "MCU") (pin "92") (pinfunction "P102/AN02_92") (pintype "bidirectional"))
      (node (ref "R57") (pin "1") (pinfunction "1_1") (pintype "passive"))
    )
    (net (code "10") (name "AN3") (class "Default")
      (node (ref "C4") (pin "1") (pinfunction "1_1") (pintype "passive"))
      (node (ref "MCU") (pin "91") (pinfunction "P103/AN03_91") (pintype "bidirectional"))
      (node (ref "R50") (pin "2") (pinfunction "2_2") (pintype "passive"))
      (node (ref "R51") (pin "2") (pinfunction "2_2") (pintype "passive"))
    )
    (net (code "11") (name "BALL_DETECT") (class "Default")
      (node (ref "COILGUN") (pin "3") (pinfunction "3_3") (pintype "passive"))
      (node (ref "MCU") (pin "25") (pinfunction "P73/CTS2/RTS2/TA1IN/V/TX8_25") (pintype "bidirectional"))
    )
    (net (code "12") (name "BUTTON1") (class "Default")
      (node (ref "J6") (pin "21") (pinfunction "21_21") (pintype "passive"))
    )
    (net (code "13") (name "BUTTON2") (class "Default")
      (node (ref "J6") (pin "23") (pinfunction "23_23") (pintype "passive"))
    )
    (net (code "14") (name "BUZZER") (class "Default")
      (node (ref "MCU") (pin "54") (pinfunction "P36/A14/[A14/D14]_54") (pintype "bidirectional"))
      (node (ref "R47") (pin "2") (pinfunction "2_2") (pintype "passive"))
    )
    (net (code "15") (name "CHARGE") (class "Default")
      (node (ref "LED5") (pin "A") (pinfunction "A_A") (pintype "passive"))
      (node (ref "LT3750") (pin "3") (pinfunction "CH_3") (pintype "bidirectional"))
      (node (ref "MCU") (pin "76") (pinfunction "P12/D10/IIO02(12)_76") (pintype "bidirectional"))
      (node (ref "TP18") (pin "TP") (pinfunction "TP_TP") (pintype "input"))
    )
    (net (code "16") (name "CLK") (class "Default")
      (node (ref "U1") (pin "14") (pinfunction "B6_14") (pintype "bidirectional"))
      (node (ref "X7") (pin "5") (pinfunction "5_5") (pintype "passive"))
    )
    (net (code "17") (name "CLK0") (class "Default")
      (node (ref "MCU") (pin "35") (pinfunction "P61/CLKO/TB1IN_35") (pintype "bidirectional"))
      (node (ref "TP24") (pin "TP") (pinfunction "TP_TP") (pintype "input"))
      (node (ref "U$6") (pin "14") (pinfunction "SCL/SPC_14") (pintype "bidirectional"))
    )
    (net (code "18") (name "CLK2") (class "Default")
      (node (ref "MCU") (pin "26") (pinfunction "P72/CLK2/TA1OUT/V_26") (pintype "bidirectional"))
      (node (ref "TP25") (pin "TP") (pinfunction "TP_TP") (pintype "input"))
      (node (ref "U$5") (pin "14") (pinfunction "SCL/SPC_14") (pintype "bidirectional"))
    )
    (net (code "19") (name "CLK4") (class "Default")
      (node (ref "J4") (pin "3") (pinfunction "MS_3") (pintype "passive"))
      (node (ref "MCU") (pin "100") (pinfunction "P95/ANEX0/CLK4_100") (pintype "bidirectional"))
      (node (ref "TP60") (pin "TP") (pinfunction "TP_TP") (pintype "input"))
    )
    (net (code "20") (name "CLK6") (class "Default")
      (node (ref "MCU") (pin "47") (pinfunction "P45/CS2/A21/CLK6_47") (pintype "bidirectional"))
      (node (ref "TP38") (pin "TP") (pinfunction "TP_TP") (pintype "input"))
      (node (ref "U2") (pin "2") (pinfunction "SCL_2") (pintype "bidirectional"))
    )
    (net (code "21") (name "CLK_LCD") (class "Default")
      (node (ref "J1") (pin "13") (pinfunction "MS_13") (pintype "passive"))
      (node (ref "MCU") (pin "51") (pinfunction "P41/A17/CLK3_51") (pintype "bidirectional"))
      (node (ref "TP2") (pin "TP") (pinfunction "TP_TP") (pintype "input"))
    )
    (net (code "22") (name "CMD") (class "Default")
      (node (ref "U1") (pin "15") (pinfunction "B5_15") (pintype "bidirectional"))
      (node (ref "X7") (pin "2") (pinfunction "2_2") (pintype "passive"))
    )
    (net (code "23") (name "CNVSS") (class "Default")
      (node (ref "JP1") (pin "3") (pinfunction "3_3") (pintype "passive"))
      (node (ref "MCU") (pin "7") (pinfunction "CNVSS_7") (pintype "input"))
      (node (ref "R8") (pin "2") (pinfunction "2_2") (pintype "passive"))
      (node (ref "TP66") (pin "TP") (pinfunction "TP_TP") (pintype "input"))
    )
    (net (code "24") (name "CS0") (class "Default")
      (node (ref "MCU") (pin "36") (pinfunction "P60/CTSO/RTSO/TB0IN_36") (pintype "bidirectional"))
      (node (ref "TP51") (pin "TP") (pinfunction "TP_TP") (pintype "input"))
      (node (ref "U$6") (pin "7") (pinfunction "CS_7") (pintype "bidirectional"))
    )
    (net (code "25") (name "CS2") (class "Default")
      (node (ref "MCU") (pin "21") (pinfunction "P77/TA3IN/CLK5_21") (pintype "bidirectional"))
      (node (ref "TP49") (pin "TP") (pinfunction "TP_TP") (pintype "input"))
      (node (ref "U$5") (pin "7") (pinfunction "CS_7") (pintype "bidirectional"))
    )
    (net (code "26") (name "CS4") (class "Default")
      (node (ref "J4") (pin "4") (pinfunction "MS_4") (pintype "passive"))
      (node (ref "MCU") (pin "1") (pinfunction "P94/DA1/TB4IN/CTS4_1") (pintype "bidirectional"))
      (node (ref "TP61") (pin "TP") (pinfunction "TP_TP") (pintype "input"))
    )
    (net (code "27") (name "CS6") (class "Default")
      (node (ref "MCU") (pin "43") (pinfunction "P51/WR1/BC1_43") (pintype "bidirectional"))
      (node (ref "TP41") (pin "TP") (pinfunction "TP_TP") (pintype "input"))
      (node (ref "U2") (pin "5") (pinfunction "CS_5") (pintype "bidirectional"))
    )
    (net (code "28") (name "CS7") (class "Default")
      (node (ref "J5") (pin "4") (pinfunction "MS_4") (pintype "passive"))
      (node (ref "MCU") (pin "41") (pinfunction "P53/BCLK/CLKOUT_41") (pintype "bidirectional"))
      (node (ref "TP62") (pin "TP") (pinfunction "TP_TP") (pintype "input"))
    )
    (net (code "29") (name "CS_LCD") (class "Default")
      (node (ref "J1") (pin "19") (pinfunction "MS_19") (pintype "passive"))
      (node (ref "MCU") (pin "37") (pinfunction "P57/RDY/CS3/RTS7_37") (pintype "bidirectional"))
      (node (ref "TP4") (pin "TP") (pinfunction "TP_TP") (pintype "input"))
    )
    (net (code "30") (name "DAT0") (class "Default")
      (node (ref "U1") (pin "16") (pinfunction "B4_16") (pintype "bidirectional"))
      (node (ref "X7") (pin "7") (pinfunction "7_7") (pintype "passive"))
    )
    (net (code "31") (name "DAT1") (class "Default")
      (node (ref "U1") (pin "17") (pinfunction "B3_17") (pintype "bidirectional"))
      (node (ref "X7") (pin "8") (pinfunction "8_8") (pintype "passive"))
    )
    (net (code "32") (name "DAT2") (class "Default")
      (node (ref "U1") (pin "18") (pinfunction "B2_18") (pintype "bidirectional"))
      (node (ref "X7") (pin "9") (pinfunction "9_9") (pintype "passive"))
    )
    (net (code "33") (name "DAT3") (class "Default")
      (node (ref "U1") (pin "20") (pinfunction "B1_20") (pintype "bidirectional"))
      (node (ref "X7") (pin "1") (pinfunction "1_1") (pintype "passive"))
    )
    (net (code "34") (name "DAT_LCD") (class "Default")
      (node (ref "J1") (pin "12") (pinfunction "MS_12") (pintype "passive"))
      (node (ref "MCU") (pin "49") (pinfunction "P43/A19/TX3_49") (pintype "bidirectional"))
      (node (ref "TP1") (pin "TP") (pinfunction "TP_TP") (pintype "input"))
    )
    (net (code "35") (name "DC_LCD") (class "Default")
      (node (ref "J1") (pin "18") (pinfunction "MS_18") (pintype "passive"))
      (node (ref "MCU") (pin "52") (pinfunction "P40/A16/XTS3_52") (pintype "bidirectional"))
      (node (ref "TP3") (pin "TP") (pinfunction "TP_TP") (pintype "input"))
    )
    (net (code "36") (name "DONE") (class "Default")
      (node (ref "LT3750") (pin "2") (pinfunction "D_2") (pintype "bidirectional"))
      (node (ref "MCU") (pin "53") (pinfunction "P37/A15/[A15/D15]_53") (pintype "bidirectional"))
      (node (ref "R23") (pin "2") (pinfunction "2_2") (pintype "passive"))
      (node (ref "TP59") (pin "TP") (pinfunction "TP_TP") (pintype "input"))
    )
    (net (code "37") (name "E8_BUSY") (class "Default")
      (node (ref "JP1") (pin "9") (pinfunction "9_9") (pintype "passive"))
      (node (ref "MCU") (pin "32") (pinfunction "P64/CTS1/RTS1/CLKS1/SS1_32") (pintype "bidirectional"))
      (node (ref "TP70") (pin "TP") (pinfunction "TP_TP") (pintype "input"))
    )
    (net (code "38") (name "E8_CLK") (class "Default")
      (node (ref "JP1") (pin "1") (pinfunction "1_1") (pintype "passive"))
      (node (ref "MCU") (pin "31") (pinfunction "P65/CLK1_31") (pintype "bidirectional"))
      (node (ref "TP67") (pin "TP") (pinfunction "TP_TP") (pintype "input"))
    )
    (net (code "39") (name "E8_RX") (class "Default")
      (node (ref "JP1") (pin "11") (pinfunction "11_11") (pintype "passive"))
      (node (ref "MCU") (pin "30") (pinfunction "P66/RXD1/SCL1/STX1_30") (pintype "bidirectional"))
      (node (ref "TP71") (pin "TP") (pinfunction "TP_TP") (pintype "input"))
    )
    (net (code "40") (name "E8_TX") (class "Default")
      (node (ref "JP1") (pin "5") (pinfunction "5_5") (pintype "passive"))
      (node (ref "MCU") (pin "29") (pinfunction "P67/TXD1/SDA1/SRX1_29") (pintype "bidirectional"))
      (node (ref "TP68") (pin "TP") (pinfunction "TP_TP") (pintype "input"))
    )
    (net (code "41") (name "ENABLE_PANDA") (class "Default")
      (node (ref "MCU") (pin "55") (pinfunction "P35/A13/[A13/D13]_55") (pintype "bidirectional"))
      (node (ref "R35") (pin "2") (pinfunction "2_2") (pintype "passive"))
      (node (ref "TP53") (pin "TP") (pinfunction "TP_TP") (pintype "input"))
      (node (ref "U$3") (pin "3") (pinfunction "EN_3") (pintype "bidirectional"))
    )
    (net (code "42") (name "GND") (class "Default")
      (node (ref "10UF/16V") (pin "-") (pinfunction "-_-") (pintype "passive"))
      (node (ref "5V") (pin "2") (pinfunction "2_2") (pintype "passive"))
      (node (ref "C1") (pin "-") (pinfunction "-_-") (pintype "passive"))
      (node (ref "C100") (pin "-") (pinfunction "-_-") (pintype "passive"))
      (node (ref "C11") (pin "2") (pinfunction "2_2") (pintype "passive"))
      (node (ref "C12") (pin "-") (pinfunction "-_-") (pintype "passive"))
      (node (ref "C13") (pin "-") (pinfunction "-_-") (pintype "passive"))
      (node (ref "C14") (pin "-") (pinfunction "-_-") (pintype "passive"))
      (node (ref "C16") (pin "1") (pinfunction "1_1") (pintype "passive"))
      (node (ref "C17") (pin "2") (pinfunction "2_2") (pintype "passive"))
      (node (ref "C18") (pin "2") (pinfunction "2_2") (pintype "passive"))
      (node (ref "C19") (pin "2") (pinfunction "2_2") (pintype "passive"))
      (node (ref "C2") (pin "-") (pinfunction "-_-") (pintype "passive"))
      (node (ref "C22") (pin "1") (pinfunction "1_1") (pintype "passive"))
      (node (ref "C23") (pin "1") (pinfunction "1_1") (pintype "passive"))
      (node (ref "C24") (pin "1") (pinfunction "1_1") (pintype "passive"))
      (node (ref "C25") (pin "-") (pinfunction "-_-") (pintype "passive"))
      (node (ref "C26") (pin "2") (pinfunction "2_2") (pintype "passive"))
      (node (ref "C27") (pin "1") (pinfunction "1_1") (pintype "passive"))
      (node (ref "C28") (pin "2") (pinfunction "2_2") (pintype "passive"))
      (node (ref "C29") (pin "2") (pinfunction "2_2") (pintype "passive"))
      (node (ref "C3") (pin "2") (pinfunction "2_2") (pintype "passive"))
      (node (ref "C30") (pin "2") (pinfunction "2_2") (pintype "passive"))
      (node (ref "C31") (pin "2") (pinfunction "2_2") (pintype "passive"))
      (node (ref "C32") (pin "2") (pinfunction "2_2") (pintype "passive"))
      (node (ref "C33") (pin "-") (pinfunction "-_-") (pintype "passive"))
      (node (ref "C36") (pin "2") (pinfunction "2_2") (pintype "passive"))
      (node (ref "C4") (pin "2") (pinfunction "2_2") (pintype "passive"))
      (node (ref "C41") (pin "2") (pinfunction "2_2") (pintype "passive"))
      (node (ref "C45") (pin "2") (pinfunction "2_2") (pintype "passive"))
      (node (ref "C46") (pin "2") (pinfunction "2_2") (pintype "passive"))
      (node (ref "C48") (pin "2") (pinfunction "2_2") (pintype "passive"))
      (node (ref "C5") (pin "2") (pinfunction "2_2") (pintype "passive"))
      (node (ref "C51") (pin "2") (pinfunction "2_2") (pintype "passive"))
      (node (ref "C52") (pin "2") (pinfunction "2_2") (pintype "passive"))
      (node (ref "C53") (pin "2") (pinfunction "2_2") (pintype "passive"))
      (node (ref "C54") (pin "2") (pinfunction "2_2") (pintype "passive"))
      (node (ref "C55") (pin "2") (pinfunction "2_2") (pintype "passive"))
      (node (ref "C56") (pin "2") (pinfunction "2_2") (pintype "passive"))
      (node (ref "C58") (pin "2") (pinfunction "2_2") (pintype "passive"))
      (node (ref "C59") (pin "2") (pinfunction "2_2") (pintype "passive"))
      (node (ref "C6") (pin "2") (pinfunction "2_2") (pintype "passive"))
      (node (ref "C60") (pin "2") (pinfunction "2_2") (pintype "passive"))
      (node (ref "C61") (pin "2") (pinfunction "2_2") (pintype "passive"))
      (node (ref "C62") (pin "2") (pinfunction "2_2") (pintype "passive"))
      (node (ref "C63") (pin "2") (pinfunction "2_2") (pintype "passive"))
      (node (ref "C64") (pin "2") (pinfunction "2_2") (pintype "passive"))
      (node (ref "C7") (pin "2") (pinfunction "2_2") (pintype "passive"))
      (node (ref "C71") (pin "1") (pinfunction "1_1") (pintype "passive"))
      (node (ref "C72") (pin "1") (pinfunction "1_1") (pintype "passive"))
      (node (ref "C8") (pin "2") (pinfunction "2_2") (pintype "passive"))
      (node (ref "C9") (pin "2") (pinfunction "2_2") (pintype "passive"))
      (node (ref "CHGLED1") (pin "C") (pinfunction "C_C") (pintype "passive"))
      (node (ref "COILGUN") (pin "1") (pinfunction "1_1") (pintype "passive"))
      (node (ref "D100") (pin "1") (pinfunction "A_1") (pintype "passive"))
      (node (ref "D2") (pin "2") (pinfunction "C2_2") (pintype "passive"))
      (node (ref "D4") (pin "1") (pinfunction "A_1") (pintype "passive"))
      (node (ref "GND") (pin "1") (pinfunction "P_1") (pintype "passive"))
      (node (ref "GND78") (pin "1") (pinfunction "P_1") (pintype "passive"))
      (node (ref "IC1") (pin "4") (pinfunction "GND_4") (pintype "power_in"))
      (node (ref "IC2") (pin "18") (pinfunction "GNDB_18") (pintype "power_in"))
      (node (ref "IC2") (pin "19") (pinfunction "GNDB_19") (pintype "power_in"))
      (node (ref "IC2") (pin "20") (pinfunction "GNDB_20") (pintype "power_in"))
      (node (ref "IC2") (pin "26") (pinfunction "GNDA_26") (pintype "power_in"))
      (node (ref "IC2") (pin "27") (pinfunction "GNDA_27") (pintype "power_in"))
      (node (ref "IC2") (pin "28") (pinfunction "GNDA_28") (pintype "power_in"))
      (node (ref "IC3") (pin "1") (pinfunction "GND_1") (pintype "power_in"))
      (node (ref "IC6") (pin "18") (pinfunction "GNDB_18") (pintype "power_in"))
      (node (ref "IC6") (pin "19") (pinfunction "GNDB_19") (pintype "power_in"))
      (node (ref "IC6") (pin "20") (pinfunction "GNDB_20") (pintype "power_in"))
      (node (ref "IC6") (pin "26") (pinfunction "GNDA_26") (pintype "power_in"))
      (node (ref "IC6") (pin "27") (pinfunction "GNDA_27") (pintype "power_in"))
      (node (ref "IC6") (pin "28") (pinfunction "GNDA_28") (pintype "power_in"))
      (node (ref "IC8") (pin "2") (pinfunction "GND_2") (pintype "passive"))
      (node (ref "IC8") (pin "4") (pinfunction "GND_4") (pintype "passive"))
      (node (ref "J1") (pin "1") (pinfunction "MSV_1") (pintype "passive"))
      (node (ref "J1") (pin "10") (pinfunction "MS_10") (pintype "passive"))
      (node (ref "J1") (pin "14") (pinfunction "MS_14") (pintype "passive"))
      (node (ref "J1") (pin "15") (pinfunction "MS_15") (pintype "passive"))
      (node (ref "J1") (pin "16") (pinfunction "MS_16") (pintype "passive"))
      (node (ref "J1") (pin "17") (pinfunction "MS_17") (pintype "passive"))
      (node (ref "J1") (pin "2") (pinfunction "MS_2") (pintype "passive"))
      (node (ref "J1") (pin "28") (pinfunction "MS_28") (pintype "passive"))
      (node (ref "J1") (pin "30") (pinfunction "MS_30") (pintype "passive"))
      (node (ref "J1") (pin "5") (pinfunction "MS_5") (pintype "passive"))
      (node (ref "J1") (pin "6") (pinfunction "MS_6") (pintype "passive"))
      (node (ref "J1") (pin "7") (pinfunction "MS_7") (pintype "passive"))
      (node (ref "J1") (pin "8") (pinfunction "MS_8") (pintype "passive"))
      (node (ref "J1") (pin "9") (pinfunction "MS_9") (pintype "passive"))
      (node (ref "J3") (pin "27") (pinfunction "27_27") (pintype "passive"))
      (node (ref "J3") (pin "28") (pinfunction "28_28") (pintype "passive"))
      (node (ref "J4") (pin "1") (pinfunction "MS_1") (pintype "passive"))
      (node (ref "J4") (pin "6") (pinfunction "MS_6") (pintype "passive"))
      (node (ref "J5") (pin "1") (pinfunction "MS_1") (pintype "passive"))
      (node (ref "J5") (pin "6") (pinfunction "MS_6") (pintype "passive"))
      (node (ref "J6") (pin "7") (pinfunction "7_7") (pintype "passive"))
      (node (ref "J6") (pin "8") (pinfunction "8_8") (pintype "passive"))
      (node (ref "JP1") (pin "10") (pinfunction "10_10") (pintype "passive"))
      (node (ref "JP1") (pin "12") (pinfunction "12_12") (pintype "passive"))
      (node (ref "JP1") (pin "14") (pinfunction "14_14") (pintype "passive"))
      (node (ref "JP1") (pin "2") (pinfunction "2_2") (pintype "passive"))
      (node (ref "JP1") (pin "6") (pinfunction "6_6") (pintype "passive"))
      (node (ref "JP2") (pin "GND") (pinfunction "GND_GND") (pintype "bidirectional"))
      (node (ref "LSP2") (pin "MP") (pinfunction "MP_MP") (pintype "passive"))
      (node (ref "LT3750") (pin "5") (pinfunction "GND_5") (pintype "bidirectional"))
      (node (ref "MCU") (pin "12") (pinfunction "VSS_12") (pintype "power_in"))
      (node (ref "MCU") (pin "62") (pinfunction "VSS_62") (pintype "power_in"))
      (node (ref "MCU") (pin "94") (pinfunction "AVSS_94") (pintype "input"))
      (node (ref "PAD10") (pin "1") (pinfunction "P_1") (pintype "passive"))
      (node (ref "PAD11") (pin "1") (pinfunction "P_1") (pintype "passive"))
      (node (ref "PAD12") (pin "1") (pinfunction "P_1") (pintype "passive"))
      (node (ref "PAD13") (pin "1") (pinfunction "P_1") (pintype "passive"))
      (node (ref "PAD14") (pin "1") (pinfunction "P_1") (pintype "passive"))
      (node (ref "PAD15") (pin "1") (pinfunction "P_1") (pintype "passive"))
      (node (ref "PAD16") (pin "1") (pinfunction "P_1") (pintype "passive"))
      (node (ref "PAD17") (pin "1") (pinfunction "P_1") (pintype "passive"))
      (node (ref "PAD18") (pin "1") (pinfunction "P_1") (pintype "passive"))
      (node (ref "PAD19") (pin "1") (pinfunction "P_1") (pintype "passive"))
      (node (ref "PAD20") (pin "1") (pinfunction "P_1") (pintype "passive"))
      (node (ref "PAD21") (pin "1") (pinfunction "P_1") (pintype "passive"))
      (node (ref "PAD22") (pin "1") (pinfunction "P_1") (pintype "passive"))
      (node (ref "PAD23") (pin "1") (pinfunction "P_1") (pintype "passive"))
      (node (ref "PAD24") (pin "1") (pinfunction "P_1") (pintype "passive"))
      (node (ref "PAD3") (pin "1") (pinfunction "P_1") (pintype "passive"))
      (node (ref "PAD4") (pin "1") (pinfunction "P_1") (pintype "passive"))
      (node (ref "PAD7") (pin "1") (pinfunction "P_1") (pintype "passive"))
      (node (ref "PAD8") (pin "1") (pinfunction "P_1") (pintype "passive"))
      (node (ref "PAD9") (pin "1") (pinfunction "P_1") (pintype "passive"))
      (node (ref "PANDA") (pin "2") (pinfunction "2_2") (pintype "passive"))
      (node (ref "Q3") (pin "2") (pinfunction "E_2") (pintype "passive"))
      (node (ref "Q4") (pin "3") (pinfunction "D_3") (pintype "passive"))
      (node (ref "Q5") (pin "3") (pinfunction "D_3") (pintype "passive"))
      (node (ref "R10") (pin "1") (pinfunction "1_1") (pintype "passive"))
      (node (ref "R11") (pin "1") (pinfunction "1_1") (pintype "passive"))
      (node (ref "R13") (pin "2") (pinfunction "2_2") (pintype "passive"))
      (node (ref "R15") (pin "1") (pinfunction "1_1") (pintype "passive"))
      (node (ref "R18") (pin "2") (pinfunction "2_2") (pintype "passive"))
      (node (ref "R19") (pin "1") (pinfunction "1_1") (pintype "passive"))
      (node (ref "R20") (pin "2") (pinfunction "2_2") (pintype "passive"))
      (node (ref "R22") (pin "2") (pinfunction "2_2") (pintype "passive"))
      (node (ref "R26") (pin "2") (pinfunction "2_2") (pintype "passive"))
      (node (ref "R30") (pin "2") (pinfunction "2_2") (pintype "passive"))
      (node (ref "R35") (pin "1") (pinfunction "1_1") (pintype "passive"))
      (node (ref "R39") (pin "1") (pinfunction "1_1") (pintype "passive"))
      (node (ref "R40") (pin "1") (pinfunction "1_1") (pintype "passive"))
      (node (ref "R41") (pin "1") (pinfunction "1_1") (pintype "passive"))
      (node (ref "R42") (pin "1") (pinfunction "1_1") (pintype "passive"))
      (node (ref "R51") (pin "1") (pinfunction "1_1") (pintype "passive"))
      (node (ref "R56") (pin "1") (pinfunction "1_1") (pintype "passive"))
      (node (ref "R8") (pin "1") (pinfunction "1_1") (pintype "passive"))
      (node (ref "R9") (pin "1") (pinfunction "1_1") (pintype "passive"))
      (node (ref "SG2") (pin "2") (pinfunction "2_2") (pintype "passive"))
      (node (ref "U$1") (pin "1") (pinfunction "1_1") (pintype "bidirectional"))
      (node (ref "U$2") (pin "2") (pinfunction "GND_2") (pintype "power_in"))
      (node (ref "U$3") (pin "7") (pinfunction "GND_7") (pintype "bidirectional"))
      (node (ref "U$5") (pin "10") (pinfunction "NC_10") (pintype "bidirectional"))
      (node (ref "U$5") (pin "11") (pinfunction "NC_11") (pintype "bidirectional"))
      (node (ref "U$5") (pin "2") (pinfunction "GND_2") (pintype "bidirectional"))
      (node (ref "U$5") (pin "3") (pinfunction "NC_3") (pintype "bidirectional"))
      (node (ref "U$5") (pin "4") (pinfunction "IADDR0_4") (pintype "bidirectional"))
      (node (ref "U$5") (pin "5") (pinfunction "GND_5") (pintype "bidirectional"))
      (node (ref "U$6") (pin "10") (pinfunction "NC_10") (pintype "bidirectional"))
      (node (ref "U$6") (pin "11") (pinfunction "NC_11") (pintype "bidirectional"))
      (node (ref "U$6") (pin "2") (pinfunction "GND_2") (pintype "bidirectional"))
      (node (ref "U$6") (pin "3") (pinfunction "NC_3") (pintype "bidirectional"))
      (node (ref "U$6") (pin "4") (pinfunction "IADDR0_4") (pintype "bidirectional"))
      (node (ref "U$6") (pin "5") (pinfunction "GND_5") (pintype "bidirectional"))
      (node (ref "U1") (pin "11") (pinfunction "GND_11") (pintype "bidirectional"))
      (node (ref "U2") (pin "10") (pinfunction "RSVDG_10") (pintype "bidirectional"))
      (node (ref "U2") (pin "11") (pinfunction "RSDVG_11") (pintype "bidirectional"))
      (node (ref "U2") (pin "12") (pinfunction "RSVDG_12") (pintype "bidirectional"))
      (node (ref "U2") (pin "13") (pinfunction "GND_13") (pintype "bidirectional"))
      (node (ref "U2") (pin "8") (pinfunction "RSVDG_8") (pintype "bidirectional"))
      (node (ref "U2") (pin "9") (pinfunction "RSVDG_9") (pintype "bidirectional"))
      (node (ref "X4") (pin "GND") (pinfunction "GND_GND") (pintype "bidirectional"))
      (node (ref "X7") (pin "4") (pinfunction "4_4") (pintype "passive"))
      (node (ref "X7") (pin "6") (pinfunction "6_6") (pintype "passive"))
      (node (ref "X7") (pin "SW3") (pinfunction "SW3_SW3") (pintype "passive"))
      (node (ref "Y2") (pin "2") (pinfunction "2_2") (pintype "passive"))
    )
    (net (code "43") (name "HOLD") (class "Default")
      (node (ref "J5") (pin "3") (pinfunction "MS_3") (pintype "passive"))
      (node (ref "JP1") (pin "4") (pinfunction "4_4") (pintype "passive"))
      (node (ref "MCU") (pin "39") (pinfunction "P55/HOLD/CLK7_39") (pintype "bidirectional"))
      (node (ref "R1") (pin "1") (pinfunction "1_1") (pintype "passive"))
      (node (ref "TP64") (pin "TP") (pinfunction "TP_TP") (pintype "input"))
    )
    (net (code "44") (name "INT0") (class "Default")
      (node (ref "MCU") (pin "18") (pinfunction "P82/INT0_18") (pintype "bidirectional"))
      (node (ref "TP19") (pin "TP") (pinfunction "TP_TP") (pintype "input"))
      (node (ref "U$5") (pin "8") (pinfunction "INT1/DRDY_8") (pintype "bidirectional"))
      (node (ref "U$6") (pin "8") (pinfunction "INT1/DRDY_8") (pintype "bidirectional"))
    )
    (net (code "45") (name "INT1") (class "Default")
      (node (ref "MCU") (pin "17") (pinfunction "P83/INT1_17") (pintype "bidirectional"))
      (node (ref "TP43") (pin "TP") (pinfunction "TP_TP") (pintype "input"))
      (node (ref "U2") (pin "7") (pinfunction "INT1_7") (pintype "bidirectional"))
    )
    (net (code "46") (name "INT2") (class "Default")
      (node (ref "MCU") (pin "16") (pinfunction "P84/INT2_16") (pintype "bidirectional"))
      (node (ref "TP42") (pin "TP") (pinfunction "TP_TP") (pintype "input"))
      (node (ref "U2") (pin "6") (pinfunction "INT2_6") (pintype "bidirectional"))
    )
    (net (code "47") (name "JOY_CENT") (class "Default")
      (node (ref "JP2") (pin "CTR") (pinfunction "CENT_CTR") (pintype "bidirectional"))
      (node (ref "MCU") (pin "71") (pinfunction "P17/D15/INT5/IIO07(17)_71") (pintype "bidirectional"))
      (node (ref "TP46") (pin "TP") (pinfunction "TP_TP") (pintype "input"))
    )
    (net (code "48") (name "JOY_DOWN") (class "Default")
      (node (ref "JP2") (pin "D") (pinfunction "DOWN_D") (pintype "bidirectional"))
      (node (ref "MCU") (pin "74") (pinfunction "P14/D12/IIO04(14)_74") (pintype "bidirectional"))
      (node (ref "TP48") (pin "TP") (pinfunction "TP_TP") (pintype "input"))
    )
    (net (code "49") (name "JOY_LEFT") (class "Default")
      (node (ref "JP2") (pin "B") (pinfunction "LEFT_B") (pintype "bidirectional"))
      (node (ref "MCU") (pin "73") (pinfunction "P15/D13/INT3/IIO05(15)_73") (pintype "bidirectional"))
      (node (ref "TP44") (pin "TP") (pinfunction "TP_TP") (pintype "input"))
    )
    (net (code "50") (name "JOY_RIGHT") (class "Default")
      (node (ref "JP2") (pin "C") (pinfunction "RIGHT_C") (pintype "bidirectional"))
      (node (ref "MCU") (pin "72") (pinfunction "P16/D14/INT4/IIO06(16)_72") (pintype "bidirectional"))
      (node (ref "TP45") (pin "TP") (pinfunction "TP_TP") (pintype "input"))
    )
    (net (code "51") (name "JOY_UP") (class "Default")
      (node (ref "JP2") (pin "A") (pinfunction "UP_A") (pintype "bidirectional"))
      (node (ref "MCU") (pin "75") (pinfunction "P13/D11/IIO03(13)_75") (pintype "bidirectional"))
      (node (ref "TP47") (pin "TP") (pinfunction "TP_TP") (pintype "input"))
    )
    (net (code "52") (name "KICK") (class "Default")
      (node (ref "COILGUN") (pin "2") (pinfunction "2_2") (pintype "passive"))
      (node (ref "MCU") (pin "23") (pinfunction "P75/TA2IN/W/RX8_23") (pintype "bidirectional"))
    )
    (net (code "53") (name "LED1") (class "Default")
      (node (ref "LED1") (pin "A") (pinfunction "A_A") (pintype "passive"))
      (node (ref "MCU") (pin "57") (pinfunction "P33/A11/[A11/D11]_57") (pintype "bidirectional"))
    )
    (net (code "54") (name "LEFT_DIAGA") (class "Default")
      (node (ref "MCU") (pin "64") (pinfunction "P26/AN26/A6/[A6/D6]_64") (pintype "bidirectional"))
      (node (ref "R33") (pin "1") (pinfunction "1_1") (pintype "passive"))
      (node (ref "TP28") (pin "TP") (pinfunction "TP_TP") (pintype "input"))
    )
    (net (code "55") (name "LEFT_DIAGB") (class "Default")
      (node (ref "MCU") (pin "63") (pinfunction "P27/AN27/A7/[A7/D7]_63") (pintype "bidirectional"))
      (node (ref "R34") (pin "1") (pinfunction "1_1") (pintype "passive"))
      (node (ref "TP29") (pin "TP") (pinfunction "TP_TP") (pintype "input"))
    )
    (net (code "56") (name "LEFT_INA") (class "Default")
      (node (ref "MCU") (pin "68") (pinfunction "P22/AN22/A2/[A2/D2]_68") (pintype "bidirectional"))
      (node (ref "R31") (pin "1") (pinfunction "1_1") (pintype "passive"))
      (node (ref "TP26") (pin "TP") (pinfunction "TP_TP") (pintype "input"))
    )
    (net (code "57") (name "LEFT_INB") (class "Default")
      (node (ref "MCU") (pin "67") (pinfunction "P23/AN23/A3/[A3/D3]_67") (pintype "bidirectional"))
      (node (ref "R32") (pin "1") (pinfunction "1_1") (pintype "passive"))
      (node (ref "TP27") (pin "TP") (pinfunction "TP_TP") (pintype "input"))
    )
    (net (code "58") (name "LEFT_PWM") (class "Default")
      (node (ref "LED4") (pin "A") (pinfunction "A_A") (pintype "passive"))
      (node (ref "MCU") (pin "58") (pinfunction "P32/A10/[A10/D10]_58") (pintype "bidirectional"))
      (node (ref "R36") (pin "1") (pinfunction "1_1") (pintype "passive"))
      (node (ref "TP30") (pin "TP") (pinfunction "TP_TP") (pintype "input"))
    )
    (net (code "59") (name "LM2733FB") (class "Default")
      (node (ref "C49") (pin "2") (pinfunction "2_2") (pintype "passive"))
      (node (ref "R14") (pin "1") (pinfunction "1_1") (pintype "passive"))
      (node (ref "R15") (pin "2") (pinfunction "2_2") (pintype "passive"))
      (node (ref "TP50") (pin "TP") (pinfunction "TP_TP") (pintype "input"))
      (node (ref "U$2") (pin "3") (pinfunction "FB_3") (pintype "input"))
    )
    (net (code "60") (name "MELEXIS_EN") (class "Default")
      (node (ref "IC1") (pin "3") (pinfunction "~{EN}_3") (pintype "input"))
      (node (ref "MCU") (pin "61") (pinfunction "P30/A8/[A8/D8]_61") (pintype "bidirectional"))
      (node (ref "R58") (pin "2") (pinfunction "2_2") (pintype "passive"))
    )
    (net (code "61") (name "MOTOR1CS") (class "Default")
      (node (ref "IC2") (pin "9") (pinfunction "CS_9") (pintype "bidirectional"))
      (node (ref "R12") (pin "1") (pinfunction "1_1") (pintype "passive"))
      (node (ref "R13") (pin "1") (pinfunction "1_1") (pintype "passive"))
    )
    (net (code "62") (name "MOTOR1DIAGA") (class "Default")
      (node (ref "IC2") (pin "6") (pinfunction "DIAGA_6") (pintype "open_collector"))
      (node (ref "R25") (pin "1") (pinfunction "1_1") (pintype "passive"))
      (node (ref "R5") (pin "2") (pinfunction "2_2") (pintype "passive"))
    )
    (net (code "63") (name "MOTOR1DIAGB") (class "Default")
      (node (ref "IC2") (pin "10") (pinfunction "DIAGB_10") (pintype "open_collector"))
      (node (ref "R2") (pin "1") (pinfunction "1_1") (pintype "passive"))
      (node (ref "R6") (pin "2") (pinfunction "2_2") (pintype "passive"))
    )
    (net (code "64") (name "MOTOR1L") (class "Default")
      (node (ref "C20") (pin "1") (pinfunction "1_1") (pintype "passive"))
      (node (ref "C21") (pin "1") (pinfunction "1_1") (pintype "passive"))
      (node (ref "IC2") (pin "1") (pinfunction "OUTA_1") (pintype "output"))
      (node (ref "IC2") (pin "25") (pinfunction "OUTA_25") (pintype "passive"))
      (node (ref "IC2") (pin "30") (pinfunction "OUTA_30") (pintype "passive"))
      (node (ref "IC2") (pin "OUTA") (pinfunction "OUTA_OUTA") (pintype "passive"))
      (node (ref "IC2") (pin "OUTA@1") (pinfunction "OUTA_OUTA@1") (pintype "passive"))
      (node (ref "LED8") (pin "A") (pinfunction "A_A") (pintype "passive"))
      (node (ref "PAD56") (pin "1") (pinfunction "P_1") (pintype "passive"))
      (node (ref "PAD57") (pin "1") (pinfunction "P_1") (pintype "passive"))
      (node (ref "PAD58") (pin "1") (pinfunction "P_1") (pintype "passive"))
      (node (ref "PAD59") (pin "1") (pinfunction "P_1") (pintype "passive"))
      (node (ref "PAD60") (pin "1") (pinfunction "P_1") (pintype "passive"))
      (node (ref "PAD61") (pin "1") (pinfunction "P_1") (pintype "passive"))
      (node (ref "PAD62") (pin "1") (pinfunction "P_1") (pintype "passive"))
      (node (ref "PAD63") (pin "1") (pinfunction "P_1") (pintype "passive"))
      (node (ref "PAD64") (pin "1") (pinfunction "P_1") (pintype "passive"))
      (node (ref "PAD94") (pin "1") (pinfunction "P_1") (pintype "passive"))
    )
    (net (code "65") (name "MOTOR1PWM") (class "Default")
      (node (ref "IC2") (pin "8") (pinfunction "PWM_8") (pintype "input"))
      (node (ref "R7") (pin "2") (pinfunction "2_2") (pintype "passive"))
    )
    (net (code "66") (name "MOTOR1R") (class "Default")
      (node (ref "C20") (pin "2") (pinfunction "2_2") (pintype "passive"))
      (node (ref "C21") (pin "2") (pinfunction "2_2") (pintype "passive"))
      (node (ref "IC2") (pin "15") (pinfunction "OUTB_15") (pintype "output"))
      (node (ref "IC2") (pin "16") (pinfunction "OUTB_16") (pintype "passive"))
      (node (ref "IC2") (pin "21") (pinfunction "OUTB_21") (pintype "passive"))
      (node (ref "IC2") (pin "OUTB") (pinfunction "OUTB_OUTB") (pintype "passive"))
      (node (ref "IC2") (pin "OUTB@1") (pinfunction "OUTB_OUTB@1") (pintype "passive"))
      (node (ref "LED9") (pin "A") (pinfunction "A_A") (pintype "passive"))
      (node (ref "PAD65") (pin "1") (pinfunction "P_1") (pintype "passive"))
      (node (ref "PAD66") (pin "1") (pinfunction "P_1") (pintype "passive"))
      (node (ref "PAD67") (pin "1") (pinfunction "P_1") (pintype "passive"))
      (node (ref "PAD68") (pin "1") (pinfunction "P_1") (pintype "passive"))
      (node (ref "PAD69") (pin "1") (pinfunction "P_1") (pintype "passive"))
      (node (ref "PAD70") (pin "1") (pinfunction "P_1") (pintype "passive"))
      (node (ref "PAD71") (pin "1") (pinfunction "P_1") (pintype "passive"))
      (node (ref "PAD72") (pin "1") (pinfunction "P_1") (pintype "passive"))
      (node (ref "PAD73") (pin "1") (pinfunction "P_1") (pintype "passive"))
      (node (ref "PAD95") (pin "1") (pinfunction "P_1") (pintype "passive"))
    )
    (net (code "67") (name "MOTOR2CS") (class "Default")
      (node (ref "IC6") (pin "9") (pinfunction "CS_9") (pintype "bidirectional"))
      (node (ref "R29") (pin "1") (pinfunction "1_1") (pintype "passive"))
      (node (ref "R30") (pin "1") (pinfunction "1_1") (pintype "passive"))
    )
    (net (code "68") (name "MOTOR2DIAGA") (class "Default")
      (node (ref "IC6") (pin "6") (pinfunction "DIAGA_6") (pintype "open_collector"))
      (node (ref "R27") (pin "1") (pinfunction "1_1") (pintype "passive"))
      (node (ref "R33") (pin "2") (pinfunction "2_2") (pintype "passive"))
    )
    (net (code "69") (name "MOTOR2DIAGB") (class "Default")
      (node (ref "IC6") (pin "10") (pinfunction "DIAGB_10") (pintype "open_collector"))
      (node (ref "R28") (pin "1") (pinfunction "1_1") (pintype "passive"))
      (node (ref "R34") (pin "2") (pinfunction "2_2") (pintype "passive"))
    )
    (net (code "70") (name "MOTOR2INA") (class "Default")
      (node (ref "IC6") (pin "5") (pinfunction "INA_5") (pintype "input"))
      (node (ref "R31") (pin "2") (pinfunction "2_2") (pintype "passive"))
    )
    (net (code "71") (name "MOTOR2INB") (class "Default")
      (node (ref "IC6") (pin "11") (pinfunction "INB_11") (pintype "input"))
      (node (ref "R32") (pin "2") (pinfunction "2_2") (pintype "passive"))
    )
    (net (code "72") (name "MOTOR2L") (class "Default")
      (node (ref "C42") (pin "1") (pinfunction "1_1") (pintype "passive"))
      (node (ref "C43") (pin "1") (pinfunction "1_1") (pintype "passive"))
      (node (ref "IC6") (pin "1") (pinfunction "OUTA_1") (pintype "output"))
      (node (ref "IC6") (pin "25") (pinfunction "OUTA_25") (pintype "passive"))
      (node (ref "IC6") (pin "30") (pinfunction "OUTA_30") (pintype "passive"))
      (node (ref "IC6") (pin "OUTA") (pinfunction "OUTA_OUTA") (pintype "passive"))
      (node (ref "IC6") (pin "OUTA@1") (pinfunction "OUTA_OUTA@1") (pintype "passive"))
      (node (ref "LED6") (pin "A") (pinfunction "A_A") (pintype "passive"))
      (node (ref "PAD74") (pin "1") (pinfunction "P_1") (pintype "passive"))
      (node (ref "PAD75") (pin "1") (pinfunction "P_1") (pintype "passive"))
      (node (ref "PAD76") (pin "1") (pinfunction "P_1") (pintype "passive"))
      (node (ref "PAD77") (pin "1") (pinfunction "P_1") (pintype "passive"))
      (node (ref "PAD78") (pin "1") (pinfunction "P_1") (pintype "passive"))
      (node (ref "PAD79") (pin "1") (pinfunction "P_1") (pintype "passive"))
      (node (ref "PAD80") (pin "1") (pinfunction "P_1") (pintype "passive"))
      (node (ref "PAD81") (pin "1") (pinfunction "P_1") (pintype "passive"))
      (node (ref "PAD82") (pin "1") (pinfunction "P_1") (pintype "passive"))
      (node (ref "PAD92") (pin "1") (pinfunction "P_1") (pintype "passive"))
    )
    (net (code "73") (name "MOTOR2PWM") (class "Default")
      (node (ref "IC6") (pin "8") (pinfunction "PWM_8") (pintype "input"))
      (node (ref "R36") (pin "2") (pinfunction "2_2") (pintype "passive"))
    )
    (net (code "74") (name "MOTOR2R") (class "Default")
      (node (ref "C42") (pin "2") (pinfunction "2_2") (pintype "passive"))
      (node (ref "C43") (pin "2") (pinfunction "2_2") (pintype "passive"))
      (node (ref "IC6") (pin "15") (pinfunction "OUTB_15") (pintype "output"))
      (node (ref "IC6") (pin "16") (pinfunction "OUTB_16") (pintype "passive"))
      (node (ref "IC6") (pin "21") (pinfunction "OUTB_21") (pintype "passive"))
      (node (ref "IC6") (pin "OUTB") (pinfunction "OUTB_OUTB") (pintype "passive"))
      (node (ref "IC6") (pin "OUTB@1") (pinfunction "OUTB_OUTB@1") (pintype "passive"))
      (node (ref "LED7") (pin "A") (pinfunction "A_A") (pintype "passive"))
      (node (ref "PAD83") (pin "1") (pinfunction "P_1") (pintype "passive"))
      (node (ref "PAD84") (pin "1") (pinfunction "P_1") (pintype "passive"))
      (node (ref "PAD85") (pin "1") (pinfunction "P_1") (pintype "passive"))
      (node (ref "PAD86") (pin "1") (pinfunction "P_1") (pintype "passive"))
      (node (ref "PAD87") (pin "1") (pinfunction "P_1") (pintype "passive"))
      (node (ref "PAD88") (pin "1") (pinfunction "P_1") (pintype "passive"))
      (node (ref "PAD89") (pin "1") (pinfunction "P_1") (pintype "passive"))
      (node (ref "PAD90") (pin "1") (pinfunction "P_1") (pintype "passive"))
      (node (ref "PAD91") (pin "1") (pinfunction "P_1") (pintype "passive"))
      (node (ref "PAD93") (pin "1") (pinfunction "P_1") (pintype "passive"))
    )
    (net (code "75") (name "N$46") (class "Default")
      (node (ref "J1") (pin "22") (pinfunction "MS_22") (pintype "passive"))
      (node (ref "R18") (pin "1") (pinfunction "1_1") (pintype "passive"))
      (node (ref "TP9") (pin "TP") (pinfunction "TP_TP") (pintype "input"))
    )
    (net (code "76") (name "N$47") (class "Default")
      (node (ref "J1") (pin "27") (pinfunction "MS_27") (pintype "passive"))
      (node (ref "R17") (pin "2") (pinfunction "2_2") (pintype "passive"))
      (node (ref "TP8") (pin "TP") (pinfunction "TP_TP") (pintype "input"))
    )
    (net (code "77") (name "NSD") (class "Default")
      (node (ref "MCU") (pin "6") (pinfunction "NSD_6") (pintype "input"))
      (node (ref "R45") (pin "2") (pinfunction "2_2") (pintype "passive"))
    )
    (net (code "78") (name "Net-(C10-Pad2)") (class "Default")
      (node (ref "C10") (pin "2") (pinfunction "2_2") (pintype "passive"))
      (node (ref "R11") (pin "2") (pinfunction "2_2") (pintype "passive"))
    )
    (net (code "79") (name "Net-(C47-Pad2)") (class "Default")
      (node (ref "C47") (pin "2") (pinfunction "2_2") (pintype "passive"))
      (node (ref "R9") (pin "2") (pinfunction "2_2") (pintype "passive"))
    )
    (net (code "80") (name "Net-(CHGLED1-PadA)") (class "Default")
      (node (ref "CHGLED1") (pin "A") (pinfunction "A_A") (pintype "passive"))
      (node (ref "CHGLED2") (pin "C") (pinfunction "C_C") (pintype "passive"))
    )
    (net (code "81") (name "Net-(D1-PadA)") (class "Default")
      (node (ref "D1") (pin "A") (pinfunction "A_A") (pintype "passive"))
      (node (ref "U$1") (pin "12") (pinfunction "12_12") (pintype "bidirectional"))
    )
    (net (code "82") (name "Net-(D2-A1)") (class "Default")
      (node (ref "D2") (pin "1") (pinfunction "A1_1") (pintype "passive"))
      (node (ref "R17") (pin "1") (pinfunction "1_1") (pintype "passive"))
    )
    (net (code "83") (name "Net-(D100-C)") (class "Default")
      (node (ref "C15") (pin "1") (pinfunction "1_1") (pintype "passive"))
      (node (ref "D100") (pin "3") (pinfunction "C_3") (pintype "passive"))
      (node (ref "L1") (pin "P$1") (pinfunction "1_P$1") (pintype "passive"))
      (node (ref "TP54") (pin "TP") (pinfunction "TP_TP") (pintype "input"))
      (node (ref "U$3") (pin "8") (pinfunction "PH_8") (pintype "bidirectional"))
    )
    (net (code "84") (name "Net-(IC2-INA)") (class "Default")
      (node (ref "IC2") (pin "5") (pinfunction "INA_5") (pintype "input"))
      (node (ref "R3") (pin "2") (pinfunction "2_2") (pintype "passive"))
    )
    (net (code "85") (name "Net-(IC2-INB)") (class "Default")
      (node (ref "IC2") (pin "11") (pinfunction "INB_11") (pintype "input"))
      (node (ref "R4") (pin "2") (pinfunction "2_2") (pintype "passive"))
    )
    (net (code "86") (name "Net-(J1Y-MS)") (class "Default")
      (node (ref "C53") (pin "1") (pinfunction "1_1") (pintype "passive"))
      (node (ref "J1") (pin "4") (pinfunction "MS_4") (pintype "passive"))
      (node (ref "TP82") (pin "TP") (pinfunction "TP_TP") (pintype "input"))
    )
    (net (code "87") (name "Net-(L2-2)") (class "Default")
      (node (ref "D3") (pin "A") (pinfunction "A_A") (pintype "passive"))
      (node (ref "L2") (pin "1") (pinfunction "2_1") (pintype "passive"))
      (node (ref "U$2") (pin "1") (pinfunction "VOUT_1") (pintype "output"))
    )
    (net (code "88") (name "Net-(L3-1)") (class "Default")
      (node (ref "C55") (pin "1") (pinfunction "1_1") (pintype "passive"))
      (node (ref "L3") (pin "2") (pinfunction "1_2") (pintype "passive"))
      (node (ref "MCU") (pin "96") (pinfunction "VREF_96") (pintype "input"))
      (node (ref "MCU") (pin "97") (pinfunction "AVCC_97") (pintype "input"))
    )
    (net (code "89") (name "Net-(LED1-PadC)") (class "Default")
      (node (ref "LED1") (pin "C") (pinfunction "C_C") (pintype "passive"))
      (node (ref "R19") (pin "2") (pinfunction "2_2") (pintype "passive"))
    )
    (net (code "90") (name "Net-(LED2-PadC)") (class "Default")
      (node (ref "LED2") (pin "C") (pinfunction "C_C") (pintype "passive"))
      (node (ref "R10") (pin "2") (pinfunction "2_2") (pintype "passive"))
    )
    (net (code "91") (name "Net-(LED3-PadC)") (class "Default")
      (node (ref "LED3") (pin "C") (pinfunction "C_C") (pintype "passive"))
      (node (ref "R40") (pin "2") (pinfunction "2_2") (pintype "passive"))
    )
    (net (code "92") (name "Net-(LED4-PadC)") (class "Default")
      (node (ref "LED4") (pin "C") (pinfunction "C_C") (pintype "passive"))
      (node (ref "R39") (pin "2") (pinfunction "2_2") (pintype "passive"))
    )
    (net (code "93") (name "Net-(LED5-PadC)") (class "Default")
      (node (ref "LED5") (pin "C") (pinfunction "C_C") (pintype "passive"))
      (node (ref "R42") (pin "2") (pinfunction "2_2") (pintype "passive"))
    )
    (net (code "94") (name "Net-(LED6-PadC)") (class "Default")
      (node (ref "LED6") (pin "C") (pinfunction "C_C") (pintype "passive"))
      (node (ref "LED7") (pin "C") (pinfunction "C_C") (pintype "passive"))
      (node (ref "R41") (pin "2") (pinfunction "2_2") (pintype "passive"))
    )
    (net (code "95") (name "Net-(LED8-PadC)") (class "Default")
      (node (ref "LED8") (pin "C") (pinfunction "C_C") (pintype "passive"))
      (node (ref "LED9") (pin "C") (pinfunction "C_C") (pintype "passive"))
      (node (ref "R56") (pin "2") (pinfunction "2_2") (pintype "passive"))
    )
    (net (code "96") (name "Net-(LT3750-G)") (class "Default")
      (node (ref "LT3750") (pin "7") (pinfunction "G_7") (pintype "bidirectional"))
      (node (ref "TP15") (pin "TP") (pinfunction "TP_TP") (pintype "input"))
      (node (ref "U$102") (pin "4") (pinfunction "G_4") (pintype "passive"))
    )
    (net (code "97") (name "Net-(LT3750-RBG)") (class "Default")
      (node (ref "C32") (pin "1") (pinfunction "1_1") (pintype "passive"))
      (node (ref "LT3750") (pin "10") (pinfunction "RBG_10") (pintype "bidirectional"))
      (node (ref "R22") (pin "1") (pinfunction "1_1") (pintype "passive"))
      (node (ref "TP17") (pin "TP") (pinfunction "TP_TP") (pintype "input"))
    )
    (net (code "98") (name "Net-(LT3750-RD)") (class "Default")
      (node (ref "LT3750") (pin "8") (pinfunction "RD_8") (pintype "bidirectional"))
      (node (ref "R21") (pin "1") (pinfunction "1_1") (pintype "passive"))
      (node (ref "TP14") (pin "TP") (pinfunction "TP_TP") (pintype "input"))
    )
    (net (code "99") (name "Net-(LT3750-RV)") (class "Default")
      (node (ref "LT3750") (pin "9") (pinfunction "RV_9") (pintype "bidirectional"))
      (node (ref "R24") (pin "1") (pinfunction "1_1") (pintype "passive"))
      (node (ref "TP13") (pin "TP") (pinfunction "TP_TP") (pintype "input"))
    )
    (net (code "100") (name "Net-(LT3750-S)") (class "Default")
      (node (ref "LT3750") (pin "6") (pinfunction "S_6") (pintype "bidirectional"))
      (node (ref "R20") (pin "1") (pinfunction "1_1") (pintype "passive"))
      (node (ref "TP16") (pin "TP") (pinfunction "TP_TP") (pintype "input"))
      (node (ref "U$102") (pin "1") (pinfunction "S_1") (pintype "passive"))
      (node (ref "U$102") (pin "2") (pinfunction "S_2") (pintype "passive"))
      (node (ref "U$102") (pin "3") (pinfunction "S_3") (pintype "passive"))
    )
    (net (code "101") (name "Net-(MCU-P85{slash}NMI)") (class "Default")
      (node (ref "MCU") (pin "15") (pinfunction "P85/NMI_15") (pintype "input"))
      (node (ref "R44") (pin "2") (pinfunction "2_2") (pintype "passive"))
    )
    (net (code "102") (name "Net-(MCU-P86{slash}XCOUT)") (class "Default")
      (node (ref "MCU") (pin "9") (pinfunction "P86/XCOUT_9") (pintype "bidirectional"))
      (node (ref "Q1") (pin "4") (pinfunction "2_4") (pintype "passive"))
    )
    (net (code "103") (name "Net-(MCU-P87{slash}XCIN)") (class "Default")
      (node (ref "MCU") (pin "8") (pinfunction "P87/XCIN_8") (pintype "bidirectional"))
      (node (ref "Q1") (pin "1") (pinfunction "1_1") (pintype "passive"))
    )
    (net (code "104") (name "Net-(MCU-XIN)") (class "Default")
      (node (ref "MCU") (pin "13") (pinfunction "XIN_13") (pintype "input"))
      (node (ref "Y2") (pin "3") (pinfunction "3_3") (pintype "passive"))
    )
    (net (code "105") (name "Net-(MCU-XOUT)") (class "Default")
      (node (ref "MCU") (pin "11") (pinfunction "XOUT_11") (pintype "output"))
      (node (ref "Y2") (pin "1") (pinfunction "1_1") (pintype "passive"))
    )
    (net (code "106") (name "Net-(PAD25-P)") (class "Default")
      (node (ref "PAD25") (pin "1") (pinfunction "P_1") (pintype "passive"))
      (node (ref "R21") (pin "2") (pinfunction "2_2") (pintype "passive"))
      (node (ref "R24") (pin "2") (pinfunction "2_2") (pintype "passive"))
      (node (ref "TP12") (pin "TP") (pinfunction "TP_TP") (pintype "input"))
      (node (ref "U$1") (pin "3") (pinfunction "3_3") (pintype "bidirectional"))
      (node (ref "U$1") (pin "4") (pinfunction "4_4") (pintype "bidirectional"))
      (node (ref "U$1") (pin "5") (pinfunction "5_5") (pintype "bidirectional"))
      (node (ref "U$1") (pin "6") (pinfunction "6_6") (pintype "bidirectional"))
      (node (ref "U$102") (pin "5") (pinfunction "D_5") (pintype "passive"))
      (node (ref "U$102") (pin "6") (pinfunction "D_6") (pintype "passive"))
      (node (ref "U$102") (pin "7") (pinfunction "D_7") (pintype "passive"))
      (node (ref "U$102") (pin "8") (pinfunction "D_8") (pintype "passive"))
    )
    (net (code "107") (name "Net-(Q2-G)") (class "Default")
      (node (ref "Q2") (pin "1") (pinfunction "G_1") (pintype "passive"))
      (node (ref "Q3") (pin "3") (pinfunction "C_3") (pintype "passive"))
      (node (ref "R16") (pin "1") (pinfunction "1_1") (pintype "passive"))
    )
    (net (code "108") (name "Net-(R47-Pad1)") (class "Default")
      (node (ref "R47") (pin "1") (pinfunction "1_1") (pintype "passive"))
      (node (ref "SG2") (pin "1") (pinfunction "1_1") (pintype "passive"))
    )
    (net (code "109") (name "Net-(U$3-BOOT)") (class "Default")
      (node (ref "C15") (pin "2") (pinfunction "2_2") (pintype "passive"))
      (node (ref "U$3") (pin "1") (pinfunction "BOOT_1") (pintype "bidirectional"))
    )
    (net (code "110") (name "Net-(U$3-COMP)") (class "Default")
      (node (ref "C10") (pin "1") (pinfunction "1_1") (pintype "passive"))
      (node (ref "C11") (pin "1") (pinfunction "1_1") (pintype "passive"))
      (node (ref "TP81") (pin "TP") (pinfunction "TP_TP") (pintype "input"))
      (node (ref "U$3") (pin "6") (pinfunction "COMP_6") (pintype "bidirectional"))
    )
    (net (code "111") (name "Net-(U$3-SS)") (class "Default")
      (node (ref "C27") (pin "2") (pinfunction "2_2") (pintype "passive"))
      (node (ref "U$3") (pin "4") (pinfunction "SS_4") (pintype "bidirectional"))
    )
    (net (code "112") (name "Net-(U$3-VSENSE)") (class "Default")
      (node (ref "R26") (pin "1") (pinfunction "1_1") (pintype "passive"))
      (node (ref "R37") (pin "2") (pinfunction "2_2") (pintype "passive"))
      (node (ref "TP56") (pin "TP") (pinfunction "TP_TP") (pintype "input"))
      (node (ref "U$3") (pin "5") (pinfunction "VSENSE_5") (pintype "bidirectional"))
    )
    (net (code "113") (name "Net-(U2-PLL)") (class "Default")
      (node (ref "C47") (pin "1") (pinfunction "1_1") (pintype "passive"))
      (node (ref "C48") (pin "1") (pinfunction "1_1") (pintype "passive"))
      (node (ref "U2") (pin "14") (pinfunction "PLL_14") (pintype "bidirectional"))
    )
    (net (code "114") (name "OLED_ENA") (class "Default")
      (node (ref "MCU") (pin "48") (pinfunction "P44/CS3/A20/RTS6_48") (pintype "bidirectional"))
      (node (ref "Q3") (pin "1") (pinfunction "B_1") (pintype "passive"))
      (node (ref "TP11") (pin "TP") (pinfunction "TP_TP") (pintype "input"))
    )
    (net (code "115") (name "RESET") (class "Default")
      (node (ref "IC3") (pin "2") (pinfunction "~{RES}_2") (pintype "output"))
      (node (ref "JP1") (pin "13") (pinfunction "13_13") (pintype "passive"))
      (node (ref "MCU") (pin "10") (pinfunction "RESET_10") (pintype "input"))
      (node (ref "R46") (pin "2") (pinfunction "2_2") (pintype "passive"))
      (node (ref "TP72") (pin "TP") (pinfunction "TP_TP") (pintype "input"))
    )
    (net (code "116") (name "RES_LCD") (class "Default")
      (node (ref "J1") (pin "20") (pinfunction "MS_20") (pintype "passive"))
      (node (ref "MCU") (pin "50") (pinfunction "P42/A18/RX3_50") (pintype "bidirectional"))
      (node (ref "TP5") (pin "TP") (pinfunction "TP_TP") (pintype "input"))
    )
    (net (code "117") (name "RIGHT_DIAGA") (class "Default")
      (node (ref "MCU") (pin "66") (pinfunction "P24/AN24/A4/[A4/D4]_66") (pintype "bidirectional"))
      (node (ref "R5") (pin "1") (pinfunction "1_1") (pintype "passive"))
      (node (ref "TP34") (pin "TP") (pinfunction "TP_TP") (pintype "input"))
    )
    (net (code "118") (name "RIGHT_DIAGB") (class "Default")
      (node (ref "MCU") (pin "65") (pinfunction "P25/AN25/A5/[A5/D5]_65") (pintype "bidirectional"))
      (node (ref "R6") (pin "1") (pinfunction "1_1") (pintype "passive"))
      (node (ref "TP35") (pin "TP") (pinfunction "TP_TP") (pintype "input"))
    )
    (net (code "119") (name "RIGHT_INA") (class "Default")
      (node (ref "MCU") (pin "70") (pinfunction "P20/AN20/A0/[A0/D0]/BC0_70") (pintype "bidirectional"))
      (node (ref "R3") (pin "1") (pinfunction "1_1") (pintype "passive"))
      (node (ref "TP32") (pin "TP") (pinfunction "TP_TP") (pintype "input"))
    )
    (net (code "120") (name "RIGHT_INB") (class "Default")
      (node (ref "MCU") (pin "69") (pinfunction "P21/AN21/A1/[A1/D1]_69") (pintype "bidirectional"))
      (node (ref "R4") (pin "1") (pinfunction "1_1") (pintype "passive"))
      (node (ref "TP33") (pin "TP") (pinfunction "TP_TP") (pintype "input"))
    )
    (net (code "121") (name "RIGHT_PWM") (class "Default")
      (node (ref "LED3") (pin "A") (pinfunction "A_A") (pintype "passive"))
      (node (ref "MCU") (pin "56") (pinfunction "P34/A12/[A12/D12]_56") (pintype "bidirectional"))
      (node (ref "R7") (pin "1") (pinfunction "1_1") (pintype "passive"))
      (node (ref "TP36") (pin "TP") (pinfunction "TP_TP") (pintype "input"))
    )
    (net (code "122") (name "RX0") (class "Default")
      (node (ref "MCU") (pin "34") (pinfunction "P62/RXDO/SCL0/STX0_34") (pintype "bidirectional"))
      (node (ref "TP23") (pin "TP") (pinfunction "TP_TP") (pintype "input"))
      (node (ref "U$6") (pin "12") (pinfunction "SDO_12") (pintype "bidirectional"))
    )
    (net (code "123") (name "RX2") (class "Default")
      (node (ref "MCU") (pin "27") (pinfunction "P71/RXD2/SCL2/TA0IN/TB5IN/SX2_27") (pintype "bidirectional"))
      (node (ref "R62") (pin "1") (pinfunction "1_1") (pintype "passive"))
      (node (ref "TP20") (pin "TP") (pinfunction "TP_TP") (pintype "input"))
      (node (ref "U$5") (pin "12") (pinfunction "SDO_12") (pintype "bidirectional"))
    )
    (net (code "124") (name "RX4") (class "Default")
      (node (ref "J4") (pin "2") (pinfunction "MS_2") (pintype "passive"))
      (node (ref "MCU") (pin "98") (pinfunction "P97/ADTRG/RX4/SCL4_98") (pintype "bidirectional"))
      (node (ref "Q4") (pin "2") (pinfunction "S_2") (pintype "passive"))
      (node (ref "R48") (pin "1") (pinfunction "1_1") (pintype "passive"))
      (node (ref "TP58") (pin "TP") (pinfunction "TP_TP") (pintype "input"))
    )
    (net (code "125") (name "RX5") (class "Default")
      (node (ref "MCU") (pin "20") (pinfunction "P80/TA4OUT/U/RX5_20") (pintype "bidirectional"))
      (node (ref "PANDA") (pin "1") (pinfunction "1_1") (pintype "passive"))
    )
    (net (code "126") (name "RX6") (class "Default")
      (node (ref "MCU") (pin "46") (pinfunction "P46/CS1/A22/RX6_46") (pintype "bidirectional"))
      (node (ref "TP40") (pin "TP") (pinfunction "TP_TP") (pintype "input"))
      (node (ref "U2") (pin "4") (pinfunction "SDO_4") (pintype "bidirectional"))
    )
    (net (code "127") (name "RX7") (class "Default")
      (node (ref "J5") (pin "2") (pinfunction "MS_2") (pintype "passive"))
      (node (ref "MCU") (pin "38") (pinfunction "P56/ALE/RX7_38") (pintype "bidirectional"))
      (node (ref "Q5") (pin "2") (pinfunction "S_2") (pintype "passive"))
      (node (ref "R53") (pin "1") (pinfunction "1_1") (pintype "passive"))
      (node (ref "TP65") (pin "TP") (pinfunction "TP_TP") (pintype "input"))
    )
    (net (code "128") (name "SDMMC2_CD") (class "Default")
      (node (ref "J6") (pin "25") (pinfunction "25_25") (pintype "passive"))
      (node (ref "R59") (pin "1") (pinfunction "1_1") (pintype "passive"))
      (node (ref "TP80") (pin "TP") (pinfunction "TP_TP") (pintype "input"))
      (node (ref "X7") (pin "SW1") (pinfunction "SW1_SW1") (pintype "passive"))
    )
    (net (code "129") (name "SDMMC2_CLK") (class "Default")
      (node (ref "J3") (pin "21") (pinfunction "21_21") (pintype "passive"))
      (node (ref "TP73") (pin "TP") (pinfunction "TP_TP") (pintype "input"))
      (node (ref "U1") (pin "7") (pinfunction "A6_7") (pintype "bidirectional"))
    )
    (net (code "130") (name "SDMMC2_CMD") (class "Default")
      (node (ref "J3") (pin "19") (pinfunction "19_19") (pintype "passive"))
      (node (ref "TP74") (pin "TP") (pinfunction "TP_TP") (pintype "input"))
      (node (ref "U1") (pin "6") (pinfunction "A5_6") (pintype "bidirectional"))
    )
    (net (code "131") (name "SDMMC2_DAT0") (class "Default")
      (node (ref "J3") (pin "17") (pinfunction "17_17") (pintype "passive"))
      (node (ref "TP75") (pin "TP") (pinfunction "TP_TP") (pintype "input"))
      (node (ref "U1") (pin "5") (pinfunction "A4_5") (pintype "bidirectional"))
    )
    (net (code "132") (name "SDMMC2_DAT1") (class "Default")
      (node (ref "J3") (pin "15") (pinfunction "15_15") (pintype "passive"))
      (node (ref "TP76") (pin "TP") (pinfunction "TP_TP") (pintype "input"))
      (node (ref "U1") (pin "4") (pinfunction "A3_4") (pintype "bidirectional"))
    )
    (net (code "133") (name "SDMMC2_DAT2") (class "Default")
      (node (ref "J3") (pin "13") (pinfunction "13_13") (pintype "passive"))
      (node (ref "TP77") (pin "TP") (pinfunction "TP_TP") (pintype "input"))
      (node (ref "U1") (pin "3") (pinfunction "A2_3") (pintype "bidirectional"))
    )
    (net (code "134") (name "SDMMC2_DAT3") (class "Default")
      (node (ref "J3") (pin "11") (pinfunction "11_11") (pintype "passive"))
      (node (ref "TP78") (pin "TP") (pinfunction "TP_TP") (pintype "input"))
      (node (ref "U1") (pin "1") (pinfunction "A1_1") (pintype "bidirectional"))
    )
    (net (code "135") (name "SDMMC2_WP") (class "Default")
      (node (ref "J6") (pin "27") (pinfunction "27_27") (pintype "passive"))
      (node (ref "R60") (pin "1") (pinfunction "1_1") (pintype "passive"))
      (node (ref "TP79") (pin "TP") (pinfunction "TP_TP") (pintype "input"))
      (node (ref "X7") (pin "SW2") (pinfunction "SW2_SW2") (pintype "passive"))
    )
    (net (code "136") (name "TX0") (class "Default")
      (node (ref "MCU") (pin "33") (pinfunction "P63/TXDO/SDA0/SRX0_33") (pintype "bidirectional"))
      (node (ref "TP22") (pin "TP") (pinfunction "TP_TP") (pintype "input"))
      (node (ref "U$6") (pin "13") (pinfunction "SDA/SDI/SDO_13") (pintype "bidirectional"))
    )
    (net (code "137") (name "TX2") (class "Default")
      (node (ref "MCU") (pin "28") (pinfunction "P70/TXD2/SDA2/TA0OUT/SRX2_28") (pintype "bidirectional"))
      (node (ref "R61") (pin "1") (pinfunction "1_1") (pintype "passive"))
      (node (ref "TP21") (pin "TP") (pinfunction "TP_TP") (pintype "input"))
      (node (ref "U$5") (pin "13") (pinfunction "SDA/SDI/SDO_13") (pintype "bidirectional"))
    )
    (net (code "138") (name "TX4") (class "Default")
      (node (ref "MCU") (pin "99") (pinfunction "P96/ANEX1/TX4/SDA4_99") (pintype "bidirectional"))
      (node (ref "Q4") (pin "1") (pinfunction "G_1") (pintype "passive"))
      (node (ref "TP57") (pin "TP") (pinfunction "TP_TP") (pintype "input"))
    )
    (net (code "139") (name "TX5") (class "Default")
      (node (ref "MCU") (pin "22") (pinfunction "P76/TA3OUT/TX5_22") (pintype "bidirectional"))
      (node (ref "PANDA") (pin "3") (pinfunction "3_3") (pintype "passive"))
    )
    (net (code "140") (name "TX6") (class "Default")
      (node (ref "MCU") (pin "45") (pinfunction "P47/CS0/A23/TX6_45") (pintype "bidirectional"))
      (node (ref "TP39") (pin "TP") (pinfunction "TP_TP") (pintype "input"))
      (node (ref "U2") (pin "3") (pinfunction "SDA/SDI_3") (pintype "bidirectional"))
    )
    (net (code "141") (name "TX7") (class "Default")
      (node (ref "MCU") (pin "40") (pinfunction "P54/HLDA/TX7_40") (pintype "bidirectional"))
      (node (ref "Q5") (pin "1") (pinfunction "G_1") (pintype "passive"))
      (node (ref "TP63") (pin "TP") (pinfunction "TP_TP") (pintype "input"))
    )
    (net (code "142") (name "USBH3_DM") (class "Default")
      (node (ref "J6") (pin "3") (pinfunction "3_3") (pintype "passive"))
      (node (ref "X4") (pin "D-") (pinfunction "D-_D-") (pintype "bidirectional"))
    )
    (net (code "143") (name "USBH3_DP") (class "Default")
      (node (ref "J6") (pin "5") (pinfunction "5_5") (pintype "passive"))
      (node (ref "X4") (pin "D+") (pinfunction "D+_D+") (pintype "bidirectional"))
    )
    (net (code "144") (name "USBH4_DM") (class "Default")
      (node (ref "J6") (pin "4") (pinfunction "4_4") (pintype "passive"))
    )
    (net (code "145") (name "USBH4_DP") (class "Default")
      (node (ref "J6") (pin "6") (pinfunction "6_6") (pintype "passive"))
    )
    (net (code "146") (name "VBAT") (class "Default")
      (node (ref "10UF/16V") (pin "+") (pinfunction "+_+") (pintype "passive"))
      (node (ref "C1") (pin "+") (pinfunction "+_+") (pintype "passive"))
      (node (ref "C12") (pin "+") (pinfunction "+_+") (pintype "passive"))
      (node (ref "C13") (pin "+") (pinfunction "+_+") (pintype "passive"))
      (node (ref "C14") (pin "+") (pinfunction "+_+") (pintype "passive"))
      (node (ref "C18") (pin "1") (pinfunction "1_1") (pintype "passive"))
      (node (ref "C19") (pin "1") (pinfunction "1_1") (pintype "passive"))
      (node (ref "C2") (pin "+") (pinfunction "+_+") (pintype "passive"))
      (node (ref "C31") (pin "1") (pinfunction "1_1") (pintype "passive"))
      (node (ref "C41") (pin "1") (pinfunction "1_1") (pintype "passive"))
      (node (ref "C45") (pin "1") (pinfunction "1_1") (pintype "passive"))
      (node (ref "C46") (pin "1") (pinfunction "1_1") (pintype "passive"))
      (node (ref "COILGUN") (pin "4") (pinfunction "4_4") (pintype "passive"))
      (node (ref "IC1") (pin "5") (pinfunction "IN_5") (pintype "input"))
      (node (ref "IC1") (pin "6") (pinfunction "IN_6") (pintype "input"))
      (node (ref "IC2") (pin "13") (pinfunction "VCC_13") (pintype "power_in"))
      (node (ref "IC2") (pin "23") (pinfunction "VCC_23") (pintype "power_in"))
      (node (ref "IC2") (pin "3") (pinfunction "VCC_3") (pintype "power_in"))
      (node (ref "IC2") (pin "VCC") (pinfunction "VCC_VCC") (pintype "power_in"))
      (node (ref "IC2") (pin "VCC@1") (pinfunction "VCC_VCC@1") (pintype "power_in"))
      (node (ref "IC6") (pin "13") (pinfunction "VCC_13") (pintype "power_in"))
      (node (ref "IC6") (pin "23") (pinfunction "VCC_23") (pintype "power_in"))
      (node (ref "IC6") (pin "3") (pinfunction "VCC_3") (pintype "power_in"))
      (node (ref "IC6") (pin "VCC") (pinfunction "VCC_VCC") (pintype "power_in"))
      (node (ref "IC6") (pin "VCC@1") (pinfunction "VCC_VCC@1") (pintype "power_in"))
      (node (ref "IC8") (pin "1") (pinfunction "VIN_1") (pintype "input"))
      (node (ref "LT3750") (pin "1") (pinfunction "VT_1") (pintype "bidirectional"))
      (node (ref "LT3750") (pin "4") (pinfunction "VCC_4") (pintype "bidirectional"))
      (node (ref "PAD26") (pin "1") (pinfunction "P_1") (pintype "passive"))
      (node (ref "PAD27") (pin "1") (pinfunction "P_1") (pintype "passive"))
      (node (ref "PAD28") (pin "1") (pinfunction "P_1") (pintype "passive"))
      (node (ref "PAD29") (pin "1") (pinfunction "P_1") (pintype "passive"))
      (node (ref "PAD30") (pin "1") (pinfunction "P_1") (pintype "passive"))
      (node (ref "PAD31") (pin "1") (pinfunction "P_1") (pintype "passive"))
      (node (ref "PAD32") (pin "1") (pinfunction "P_1") (pintype "passive"))
      (node (ref "PAD33") (pin "1") (pinfunction "P_1") (pintype "passive"))
      (node (ref "PAD34") (pin "1") (pinfunction "P_1") (pintype "passive"))
      (node (ref "PAD35") (pin "1") (pinfunction "P_1") (pintype "passive"))
      (node (ref "PAD36") (pin "1") (pinfunction "P_1") (pintype "passive"))
      (node (ref "PAD37") (pin "1") (pinfunction "P_1") (pintype "passive"))
      (node (ref "PAD38") (pin "1") (pinfunction "P_1") (pintype "passive"))
      (node (ref "PAD39") (pin "1") (pinfunction "P_1") (pintype "passive"))
      (node (ref "PAD40") (pin "1") (pinfunction "P_1") (pintype "passive"))
      (node (ref "PAD41") (pin "1") (pinfunction "P_1") (pintype "passive"))
      (node (ref "PAD42") (pin "1") (pinfunction "P_1") (pintype "passive"))
      (node (ref "PAD43") (pin "1") (pinfunction "P_1") (pintype "passive"))
      (node (ref "PAD44") (pin "1") (pinfunction "P_1") (pintype "passive"))
      (node (ref "PAD45") (pin "1") (pinfunction "P_1") (pintype "passive"))
      (node (ref "PAD46") (pin "1") (pinfunction "P_1") (pintype "passive"))
      (node (ref "PAD47") (pin "1") (pinfunction "P_1") (pintype "passive"))
      (node (ref "PAD48") (pin "1") (pinfunction "P_1") (pintype "passive"))
      (node (ref "PAD49") (pin "1") (pinfunction "P_1") (pintype "passive"))
      (node (ref "PAD50") (pin "1") (pinfunction "P_1") (pintype "passive"))
      (node (ref "PAD51") (pin "1") (pinfunction "P_1") (pintype "passive"))
      (node (ref "PAD52") (pin "1") (pinfunction "P_1") (pintype "passive"))
      (node (ref "PAD53") (pin "1") (pinfunction "P_1") (pintype "passive"))
      (node (ref "PAD54") (pin "1") (pinfunction "P_1") (pintype "passive"))
      (node (ref "PAD55") (pin "1") (pinfunction "P_1") (pintype "passive"))
      (node (ref "Q2") (pin "2") (pinfunction "S_2") (pintype "passive"))
      (node (ref "R16") (pin "2") (pinfunction "2_2") (pintype "passive"))
      (node (ref "R50") (pin "1") (pinfunction "1_1") (pintype "passive"))
      (node (ref "U$1") (pin "10") (pinfunction "10_10") (pintype "bidirectional"))
      (node (ref "U$1") (pin "7") (pinfunction "7_7") (pintype "bidirectional"))
      (node (ref "U$1") (pin "8") (pinfunction "8_8") (pintype "bidirectional"))
      (node (ref "U$1") (pin "9") (pinfunction "9_9") (pintype "bidirectional"))
      (node (ref "U$3") (pin "2") (pinfunction "VIN_2") (pintype "bidirectional"))
      (node (ref "VBAT") (pin "1") (pinfunction "P_1") (pintype "passive"))
    )
    (net (code "147") (name "VBUS_3") (class "Default")
      (node (ref "J6") (pin "1") (pinfunction "1_1") (pintype "passive"))
      (node (ref "X4") (pin "VBUS") (pinfunction "VBUS_VBUS") (pintype "bidirectional"))
    )
    (net (code "148") (name "VBUS_4") (class "Default")
      (node (ref "J6") (pin "2") (pinfunction "2_2") (pintype "passive"))
    )
    (net (code "149") (name "VCORE") (class "Default")
      (node (ref "C60") (pin "1") (pinfunction "1_1") (pintype "passive"))
      (node (ref "C63") (pin "1") (pinfunction "1_1") (pintype "passive"))
      (node (ref "J1") (pin "25") (pinfunction "MS_25") (pintype "passive"))
      (node (ref "TP6") (pin "TP") (pinfunction "TP_TP") (pintype "input"))
    )
    (net (code "150") (name "VDC0") (class "Default")
      (node (ref "C57") (pin "2") (pinfunction "2_2") (pintype "passive"))
      (node (ref "MCU") (pin "3") (pinfunction "VDC0_3") (pintype "power_in"))
    )
    (net (code "151") (name "VDC1") (class "Default")
      (node (ref "C57") (pin "1") (pinfunction "1_1") (pintype "passive"))
      (node (ref "MCU") (pin "5") (pinfunction "VDC1_5") (pintype "power_in"))
    )
    (net (code "152") (name "VIO_1V8") (class "Default")
      (node (ref "J3") (pin "1") (pinfunction "1_1") (pintype "passive"))
      (node (ref "R59") (pin "2") (pinfunction "2_2") (pintype "passive"))
      (node (ref "R60") (pin "2") (pinfunction "2_2") (pintype "passive"))
      (node (ref "U1") (pin "10") (pinfunction "OE_10") (pintype "bidirectional"))
      (node (ref "U1") (pin "2") (pinfunction "VCCA_2") (pintype "bidirectional"))
    )
    (net (code "153") (name "WR") (class "Default")
      (node (ref "JP1") (pin "7") (pinfunction "7_7") (pintype "passive"))
      (node (ref "MCU") (pin "44") (pinfunction "P50/WR0/WR_44") (pintype "bidirectional"))
      (node (ref "TP69") (pin "TP") (pinfunction "TP_TP") (pintype "input"))
    )
    (net (code "154") (name "unconnected-(D2-C1A2-Pad3)") (class "Default")
      (node (ref "D2") (pin "3") (pinfunction "C1A2_3") (pintype "passive"))
    )
    (net (code "155") (name "unconnected-(IC1-~{RESET}-Pad2)") (class "Default")
      (node (ref "IC1") (pin "2") (pinfunction "~{RESET}_2") (pintype "input"))
    )
    (net (code "156") (name "unconnected-(J1C-MS-Pad11)") (class "Default")
      (node (ref "J1") (pin "11") (pinfunction "MS_11") (pintype "passive"))
    )
    (net (code "157") (name "unconnected-(J1N-MS-Pad21)") (class "Default")
      (node (ref "J1") (pin "21") (pinfunction "MS_21") (pintype "passive"))
    )
    (net (code "158") (name "unconnected-(J1P-MS-Pad23)") (class "Default")
      (node (ref "J1") (pin "23") (pinfunction "MS_23") (pintype "passive"))
    )
    (net (code "159") (name "unconnected-(J3-Pad2)") (class "Default")
      (node (ref "J3") (pin "2") (pinfunction "2_2") (pintype "passive"))
    )
    (net (code "160") (name "unconnected-(J3-Pad3)") (class "Default")
      (node (ref "J3") (pin "3") (pinfunction "3_3") (pintype "passive"))
    )
    (net (code "161") (name "unconnected-(J3-Pad4)") (class "Default")
      (node (ref "J3") (pin "4") (pinfunction "4_4") (pintype "passive"))
    )
    (net (code "162") (name "unconnected-(J3-Pad5)") (class "Default")
      (node (ref "J3") (pin "5") (pinfunction "5_5") (pintype "passive"))
    )
    (net (code "163") (name "unconnected-(J3-Pad6)") (class "Default")
      (node (ref "J3") (pin "6") (pinfunction "6_6") (pintype "passive"))
    )
    (net (code "164") (name "unconnected-(J3-Pad7)") (class "Default")
      (node (ref "J3") (pin "7") (pinfunction "7_7") (pintype "passive"))
    )
    (net (code "165") (name "unconnected-(J3-Pad8)") (class "Default")
      (node (ref "J3") (pin "8") (pinfunction "8_8") (pintype "passive"))
    )
    (net (code "166") (name "unconnected-(J3-Pad9)") (class "Default")
      (node (ref "J3") (pin "9") (pinfunction "9_9") (pintype "passive"))
    )
    (net (code "167") (name "unconnected-(J3-Pad10)") (class "Default")
      (node (ref "J3") (pin "10") (pinfunction "10_10") (pintype "passive"))
    )
    (net (code "168") (name "unconnected-(J3-Pad12)") (class "Default")
      (node (ref "J3") (pin "12") (pinfunction "12_12") (pintype "passive"))
    )
    (net (code "169") (name "unconnected-(J3-Pad14)") (class "Default")
      (node (ref "J3") (pin "14") (pinfunction "14_14") (pintype "passive"))
    )
    (net (code "170") (name "unconnected-(J3-Pad16)") (class "Default")
      (node (ref "J3") (pin "16") (pinfunction "16_16") (pintype "passive"))
    )
    (net (code "171") (name "unconnected-(J3-Pad18)") (class "Default")
      (node (ref "J3") (pin "18") (pinfunction "18_18") (pintype "passive"))
    )
    (net (code "172") (name "unconnected-(J3-Pad20)") (class "Default")
      (node (ref "J3") (pin "20") (pinfunction "20_20") (pintype "passive"))
    )
    (net (code "173") (name "unconnected-(J3-Pad22)") (class "Default")
      (node (ref "J3") (pin "22") (pinfunction "22_22") (pintype "passive"))
    )
    (net (code "174") (name "unconnected-(J3-Pad23)") (class "Default")
      (node (ref "J3") (pin "23") (pinfunction "23_23") (pintype "passive"))
    )
    (net (code "175") (name "unconnected-(J3-Pad24)") (class "Default")
      (node (ref "J3") (pin "24") (pinfunction "24_24") (pintype "passive"))
    )
    (net (code "176") (name "unconnected-(J3-Pad25)") (class "Default")
      (node (ref "J3") (pin "25") (pinfunction "25_25") (pintype "passive"))
    )
    (net (code "177") (name "unconnected-(J3-Pad26)") (class "Default")
      (node (ref "J3") (pin "26") (pinfunction "26_26") (pintype "passive"))
    )
    (net (code "178") (name "unconnected-(J6-Pad9)") (class "Default")
      (node (ref "J6") (pin "9") (pinfunction "9_9") (pintype "passive"))
    )
    (net (code "179") (name "unconnected-(J6-Pad10)") (class "Default")
      (node (ref "J6") (pin "10") (pinfunction "10_10") (pintype "passive"))
    )
    (net (code "180") (name "unconnected-(J6-Pad11)") (class "Default")
      (node (ref "J6") (pin "11") (pinfunction "11_11") (pintype "passive"))
    )
    (net (code "181") (name "unconnected-(J6-Pad12)") (class "Default")
      (node (ref "J6") (pin "12") (pinfunction "12_12") (pintype "passive"))
    )
    (net (code "182") (name "unconnected-(J6-Pad13)") (class "Default")
      (node (ref "J6") (pin "13") (pinfunction "13_13") (pintype "passive"))
    )
    (net (code "183") (name "unconnected-(J6-Pad14)") (class "Default")
      (node (ref "J6") (pin "14") (pinfunction "14_14") (pintype "passive"))
    )
    (net (code "184") (name "unconnected-(J6-Pad15)") (class "Default")
      (node (ref "J6") (pin "15") (pinfunction "15_15") (pintype "passive"))
    )
    (net (code "185") (name "unconnected-(J6-Pad16)") (class "Default")
      (node (ref "J6") (pin "16") (pinfunction "16_16") (pintype "passive"))
    )
    (net (code "186") (name "unconnected-(J6-Pad17)") (class "Default")
      (node (ref "J6") (pin "17") (pinfunction "17_17") (pintype "passive"))
    )
    (net (code "187") (name "unconnected-(J6-Pad18)") (class "Default")
      (node (ref "J6") (pin "18") (pinfunction "18_18") (pintype "passive"))
    )
    (net (code "188") (name "unconnected-(J6-Pad19)") (class "Default")
      (node (ref "J6") (pin "19") (pinfunction "19_19") (pintype "passive"))
    )
    (net (code "189") (name "unconnected-(J6-Pad20)") (class "Default")
      (node (ref "J6") (pin "20") (pinfunction "20_20") (pintype "passive"))
    )
    (net (code "190") (name "unconnected-(J6-Pad22)") (class "Default")
      (node (ref "J6") (pin "22") (pinfunction "22_22") (pintype "passive"))
    )
    (net (code "191") (name "unconnected-(J6-Pad24)") (class "Default")
      (node (ref "J6") (pin "24") (pinfunction "24_24") (pintype "passive"))
    )
    (net (code "192") (name "unconnected-(J6-Pad26)") (class "Default")
      (node (ref "J6") (pin "26") (pinfunction "26_26") (pintype "passive"))
    )
    (net (code "193") (name "unconnected-(J6-Pad28)") (class "Default")
      (node (ref "J6") (pin "28") (pinfunction "28_28") (pintype "passive"))
    )
    (net (code "194") (name "unconnected-(MCU-P00{slash}D0{slash}AN10-Pad86)") (class "Default")
      (node (ref "MCU") (pin "86") (pinfunction "P00/D0/AN10_86") (pintype "bidirectional"))
    )
    (net (code "195") (name "unconnected-(MCU-P01{slash}D1{slash}AN11-Pad85)") (class "Default")
      (node (ref "MCU") (pin "85") (pinfunction "P01/D1/AN11_85") (pintype "bidirectional"))
    )
    (net (code "196") (name "unconnected-(MCU-P02{slash}D2{slash}AN12-Pad84)") (class "Default")
      (node (ref "MCU") (pin "84") (pinfunction "P02/D2/AN12_84") (pintype "bidirectional"))
    )
    (net (code "197") (name "unconnected-(MCU-P03{slash}D3{slash}AN13-Pad83)") (class "Default")
      (node (ref "MCU") (pin "83") (pinfunction "P03/D3/AN13_83") (pintype "bidirectional"))
    )
    (net (code "198") (name "unconnected-(MCU-P04{slash}D4{slash}AN14-Pad82)") (class "Default")
      (node (ref "MCU") (pin "82") (pinfunction "P04/D4/AN14_82") (pintype "bidirectional"))
    )
    (net (code "199") (name "unconnected-(MCU-P05{slash}D5{slash}AN15-Pad81)") (class "Default")
      (node (ref "MCU") (pin "81") (pinfunction "P05/D5/AN15_81") (pintype "bidirectional"))
    )
    (net (code "200") (name "unconnected-(MCU-P06{slash}D6{slash}AN16-Pad80)") (class "Default")
      (node (ref "MCU") (pin "80") (pinfunction "P06/D6/AN16_80") (pintype "bidirectional"))
    )
    (net (code "201") (name "unconnected-(MCU-P07{slash}D7{slash}AN17-Pad79)") (class "Default")
      (node (ref "MCU") (pin "79") (pinfunction "P07/D7/AN17_79") (pintype "bidirectional"))
    )
    (net (code "202") (name "unconnected-(MCU-P10{slash}D8{slash}IIO00(10)-Pad78)") (class "Default")
      (node (ref "MCU") (pin "78") (pinfunction "P10/D8/IIO00(10)_78") (pintype "bidirectional"))
    )
    (net (code "203") (name "unconnected-(MCU-P11{slash}D9{slash}IIO01(11)-Pad77)") (class "Default")
      (node (ref "MCU") (pin "77") (pinfunction "P11/D9/IIO01(11)_77") (pintype "bidirectional"))
    )
    (net (code "204") (name "unconnected-(MCU-P31{slash}A9{slash}[A9{slash}D9]-Pad59)") (class "Default")
      (node (ref "MCU") (pin "59") (pinfunction "P31/A9/[A9/D9]_59") (pintype "bidirectional"))
    )
    (net (code "205") (name "unconnected-(MCU-P52{slash}RD-Pad42)") (class "Default")
      (node (ref "MCU") (pin "42") (pinfunction "P52/RD_42") (pintype "bidirectional"))
    )
    (net (code "206") (name "unconnected-(MCU-P74{slash}TA2OUT{slash}W{slash}CLK8-Pad24)") (class "Default")
      (node (ref "MCU") (pin "24") (pinfunction "P74/TA2OUT/W/CLK8_24") (pintype "bidirectional"))
    )
    (net (code "207") (name "unconnected-(MCU-P81{slash}TA4IN{slash}U{slash}CTS5-Pad19)") (class "Default")
      (node (ref "MCU") (pin "19") (pinfunction "P81/TA4IN/U/CTS5_19") (pintype "bidirectional"))
    )
    (net (code "208") (name "unconnected-(MCU-P91-Pad4)") (class "Default")
      (node (ref "MCU") (pin "4") (pinfunction "P91_4") (pintype "bidirectional"))
    )
    (net (code "209") (name "unconnected-(MCU-P93{slash}DA0{slash}TB3IN-Pad2)") (class "Default")
      (node (ref "MCU") (pin "2") (pinfunction "P93/DA0/TB3IN_2") (pintype "bidirectional"))
    )
    (net (code "210") (name "unconnected-(MCU-P104{slash}AN04{slash}KL0-Pad90)") (class "Default")
      (node (ref "MCU") (pin "90") (pinfunction "P104/AN04/KL0_90") (pintype "bidirectional"))
    )
    (net (code "211") (name "unconnected-(MCU-P105{slash}AN05{slash}KL1-Pad89)") (class "Default")
      (node (ref "MCU") (pin "89") (pinfunction "P105/AN05/KL1_89") (pintype "bidirectional"))
    )
    (net (code "212") (name "unconnected-(MCU-P106{slash}AN06{slash}KL2-Pad88)") (class "Default")
      (node (ref "MCU") (pin "88") (pinfunction "P106/AN06/KL2_88") (pintype "bidirectional"))
    )
    (net (code "213") (name "unconnected-(MCU-P107{slash}AN07{slash}KL3-Pad87)") (class "Default")
      (node (ref "MCU") (pin "87") (pinfunction "P107/AN07/KL3_87") (pintype "bidirectional"))
    )
    (net (code "214") (name "unconnected-(U$5-INT2-Pad9)") (class "Default")
      (node (ref "U$5") (pin "9") (pinfunction "INT2_9") (pintype "bidirectional"))
    )
    (net (code "215") (name "unconnected-(U$6-INT2-Pad9)") (class "Default")
      (node (ref "U$6") (pin "9") (pinfunction "INT2_9") (pintype "bidirectional"))
    )
    (net (code "216") (name "unconnected-(U1-A7-Pad8)") (class "Default")
      (node (ref "U1") (pin "8") (pinfunction "A7_8") (pintype "bidirectional"))
    )
    (net (code "217") (name "unconnected-(U1-A8-Pad9)") (class "Default")
      (node (ref "U1") (pin "9") (pinfunction "A8_9") (pintype "bidirectional"))
    )
    (net (code "218") (name "unconnected-(U1-B7-Pad13)") (class "Default")
      (node (ref "U1") (pin "13") (pinfunction "B7_13") (pintype "bidirectional"))
    )
    (net (code "219") (name "unconnected-(U1-B8-Pad12)") (class "Default")
      (node (ref "U1") (pin "12") (pinfunction "B8_12") (pintype "bidirectional"))
    )
  )
)
